# ENERGIS_Rack-PDU_1_0_0.net
KiCad netlist of a schematic drawn in EAGLE
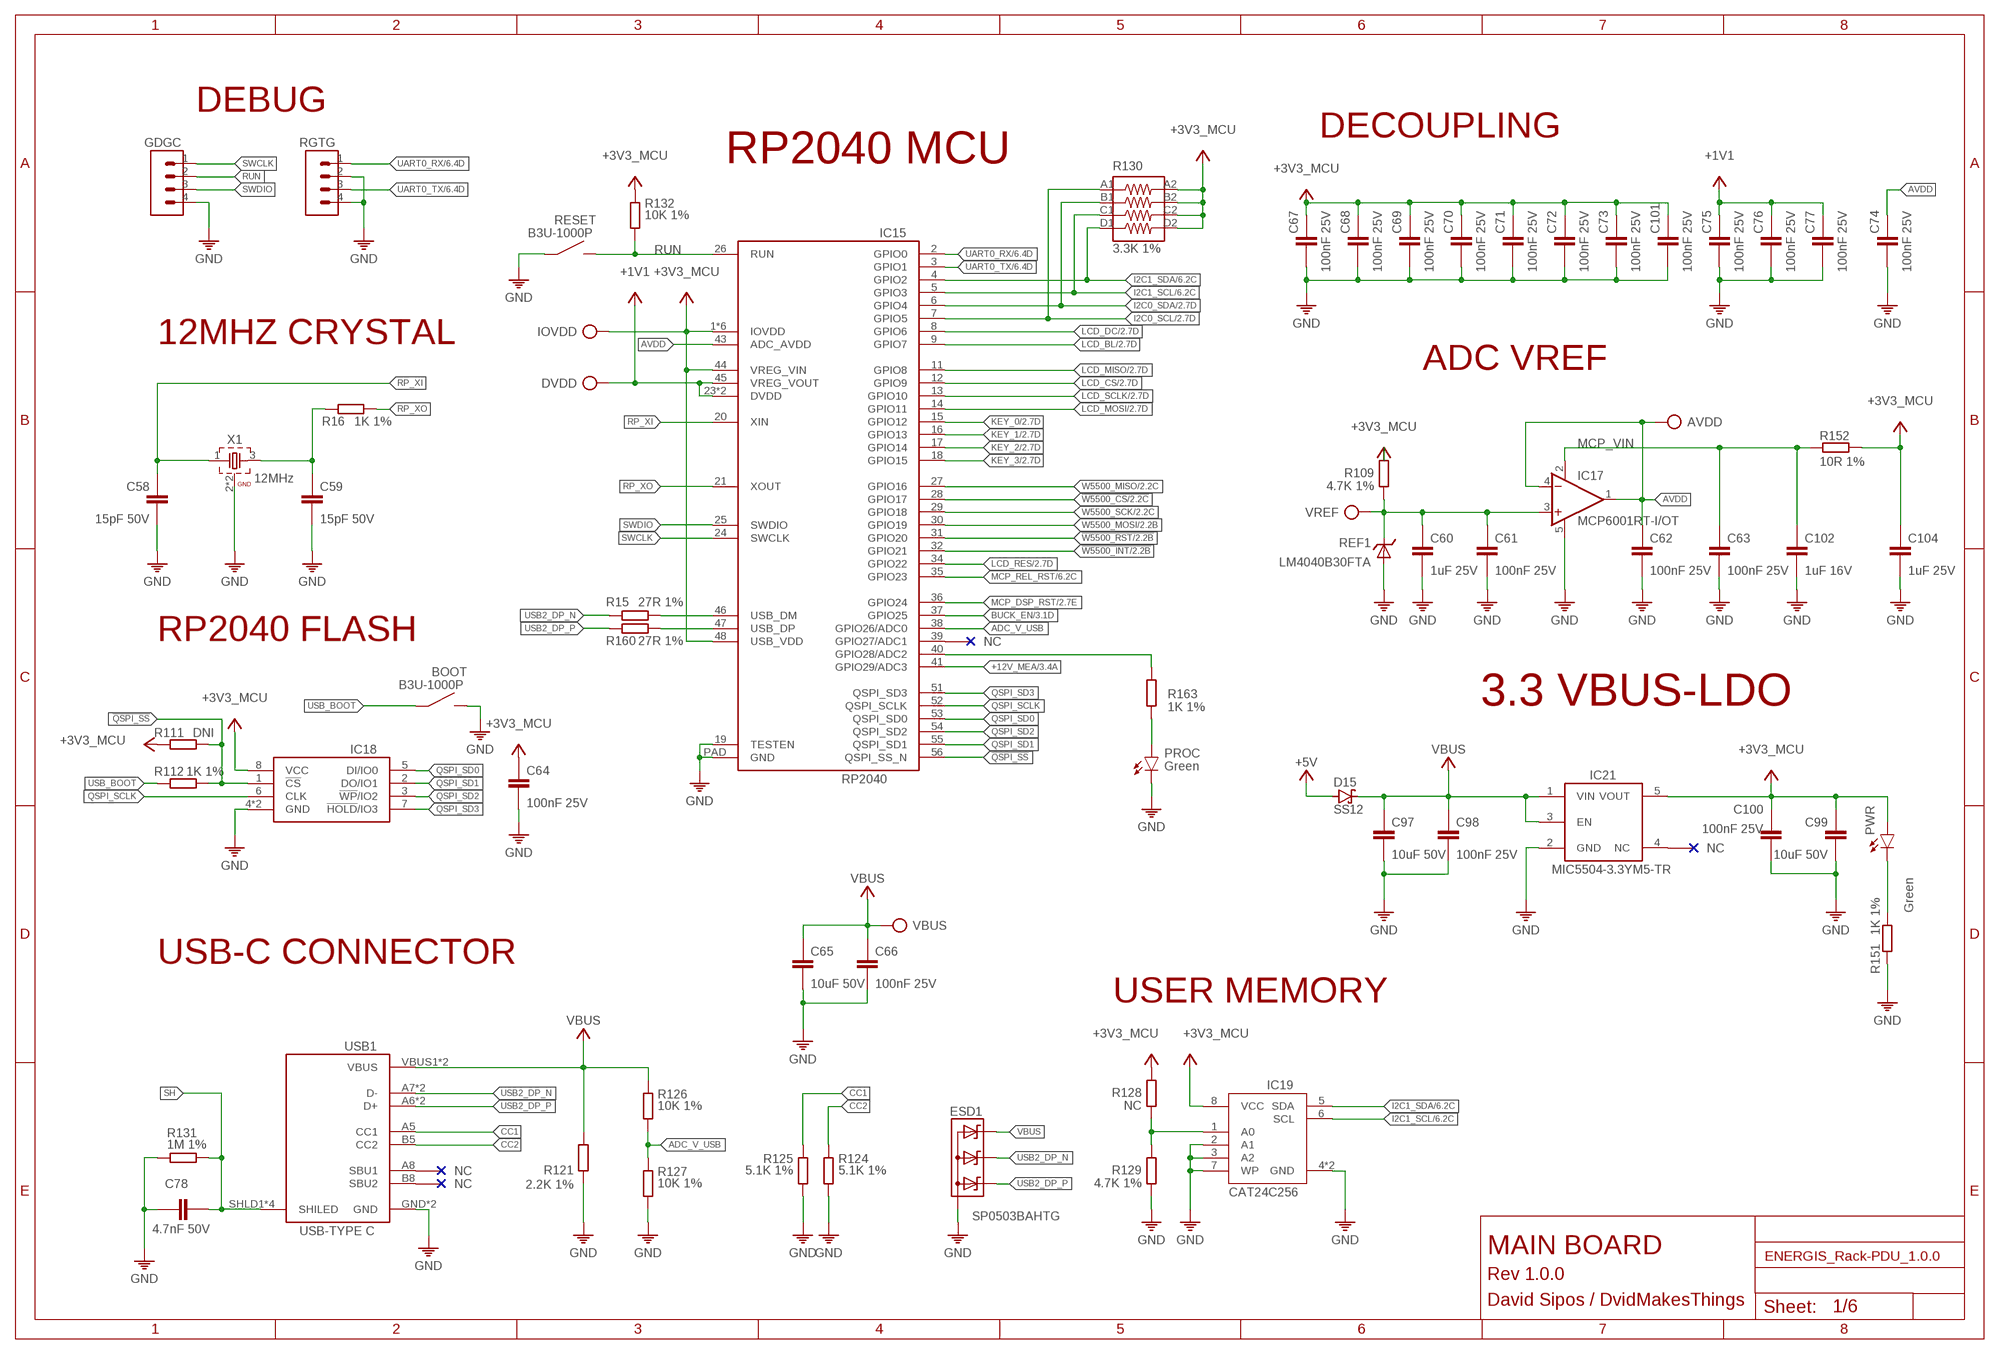
[diagram p0: schematic, sheet 1]
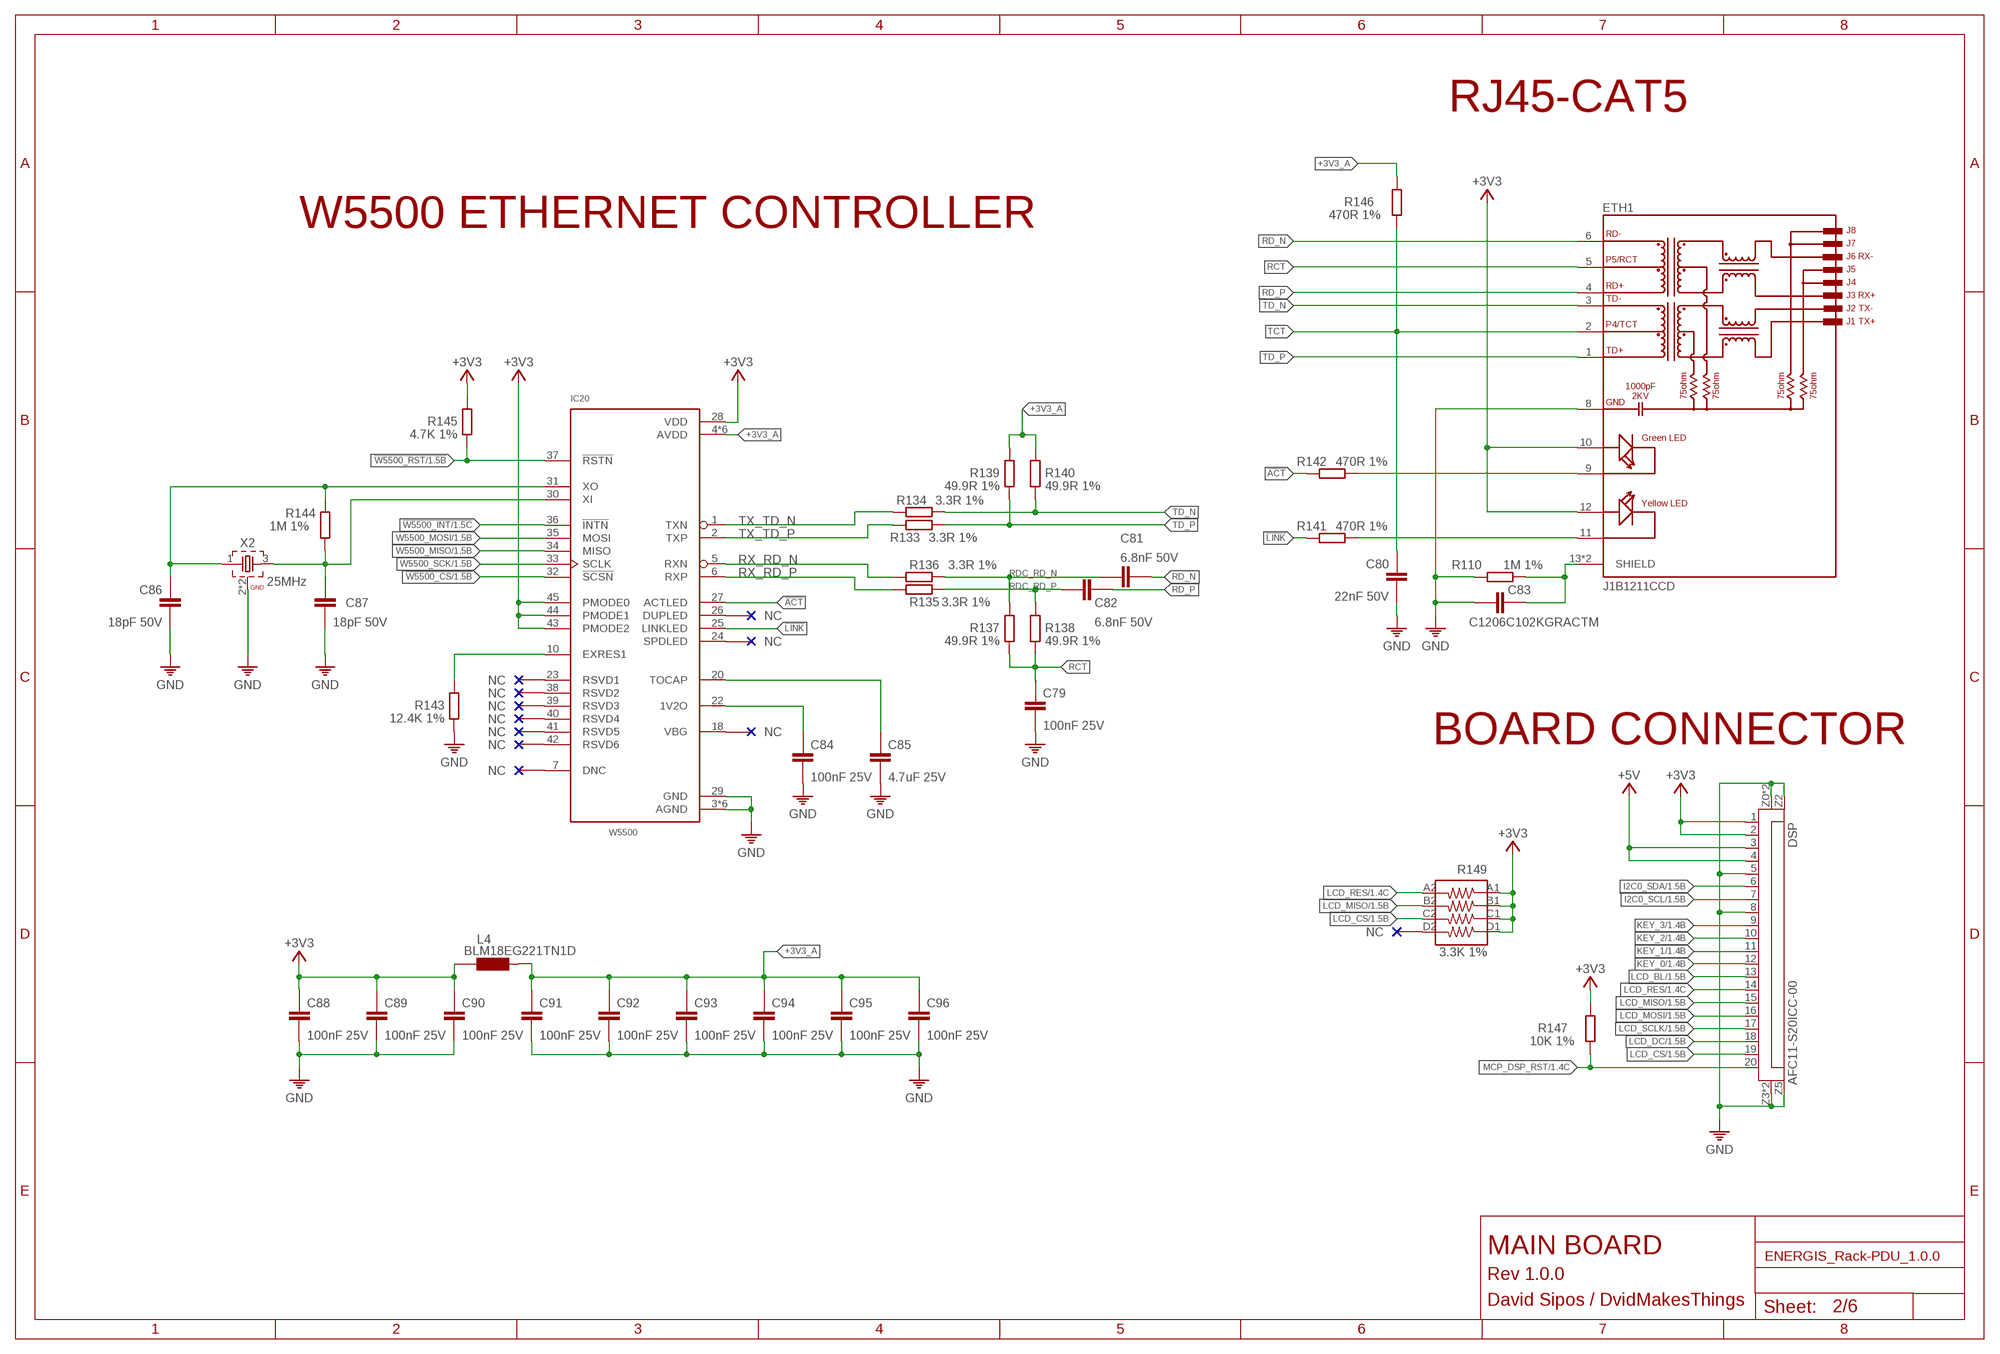
[diagram p1: schematic, sheet 2]
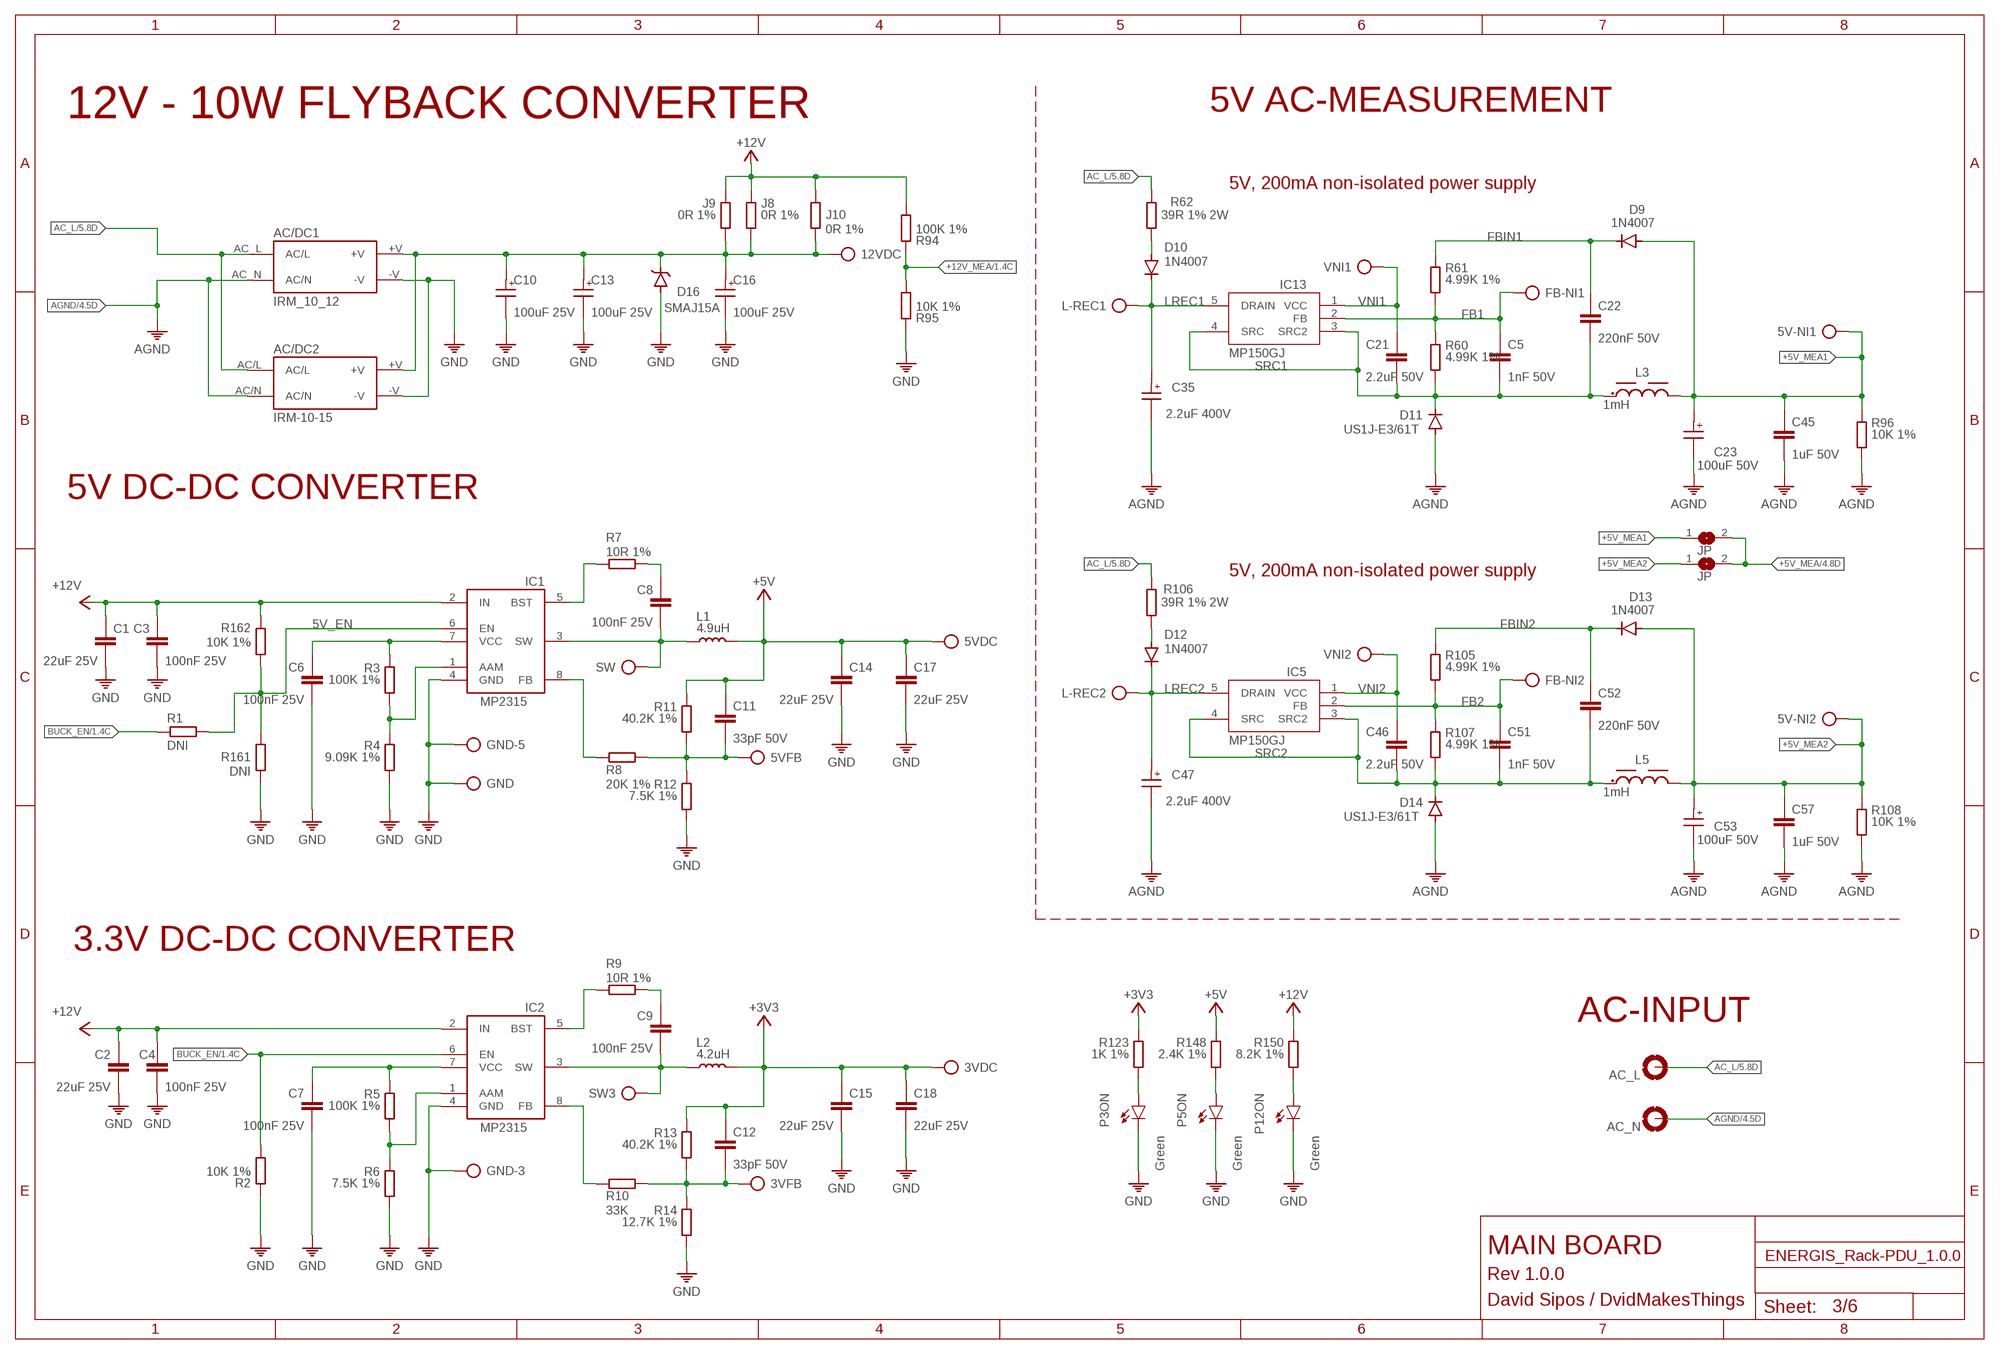
[diagram p2: schematic, sheet 3]
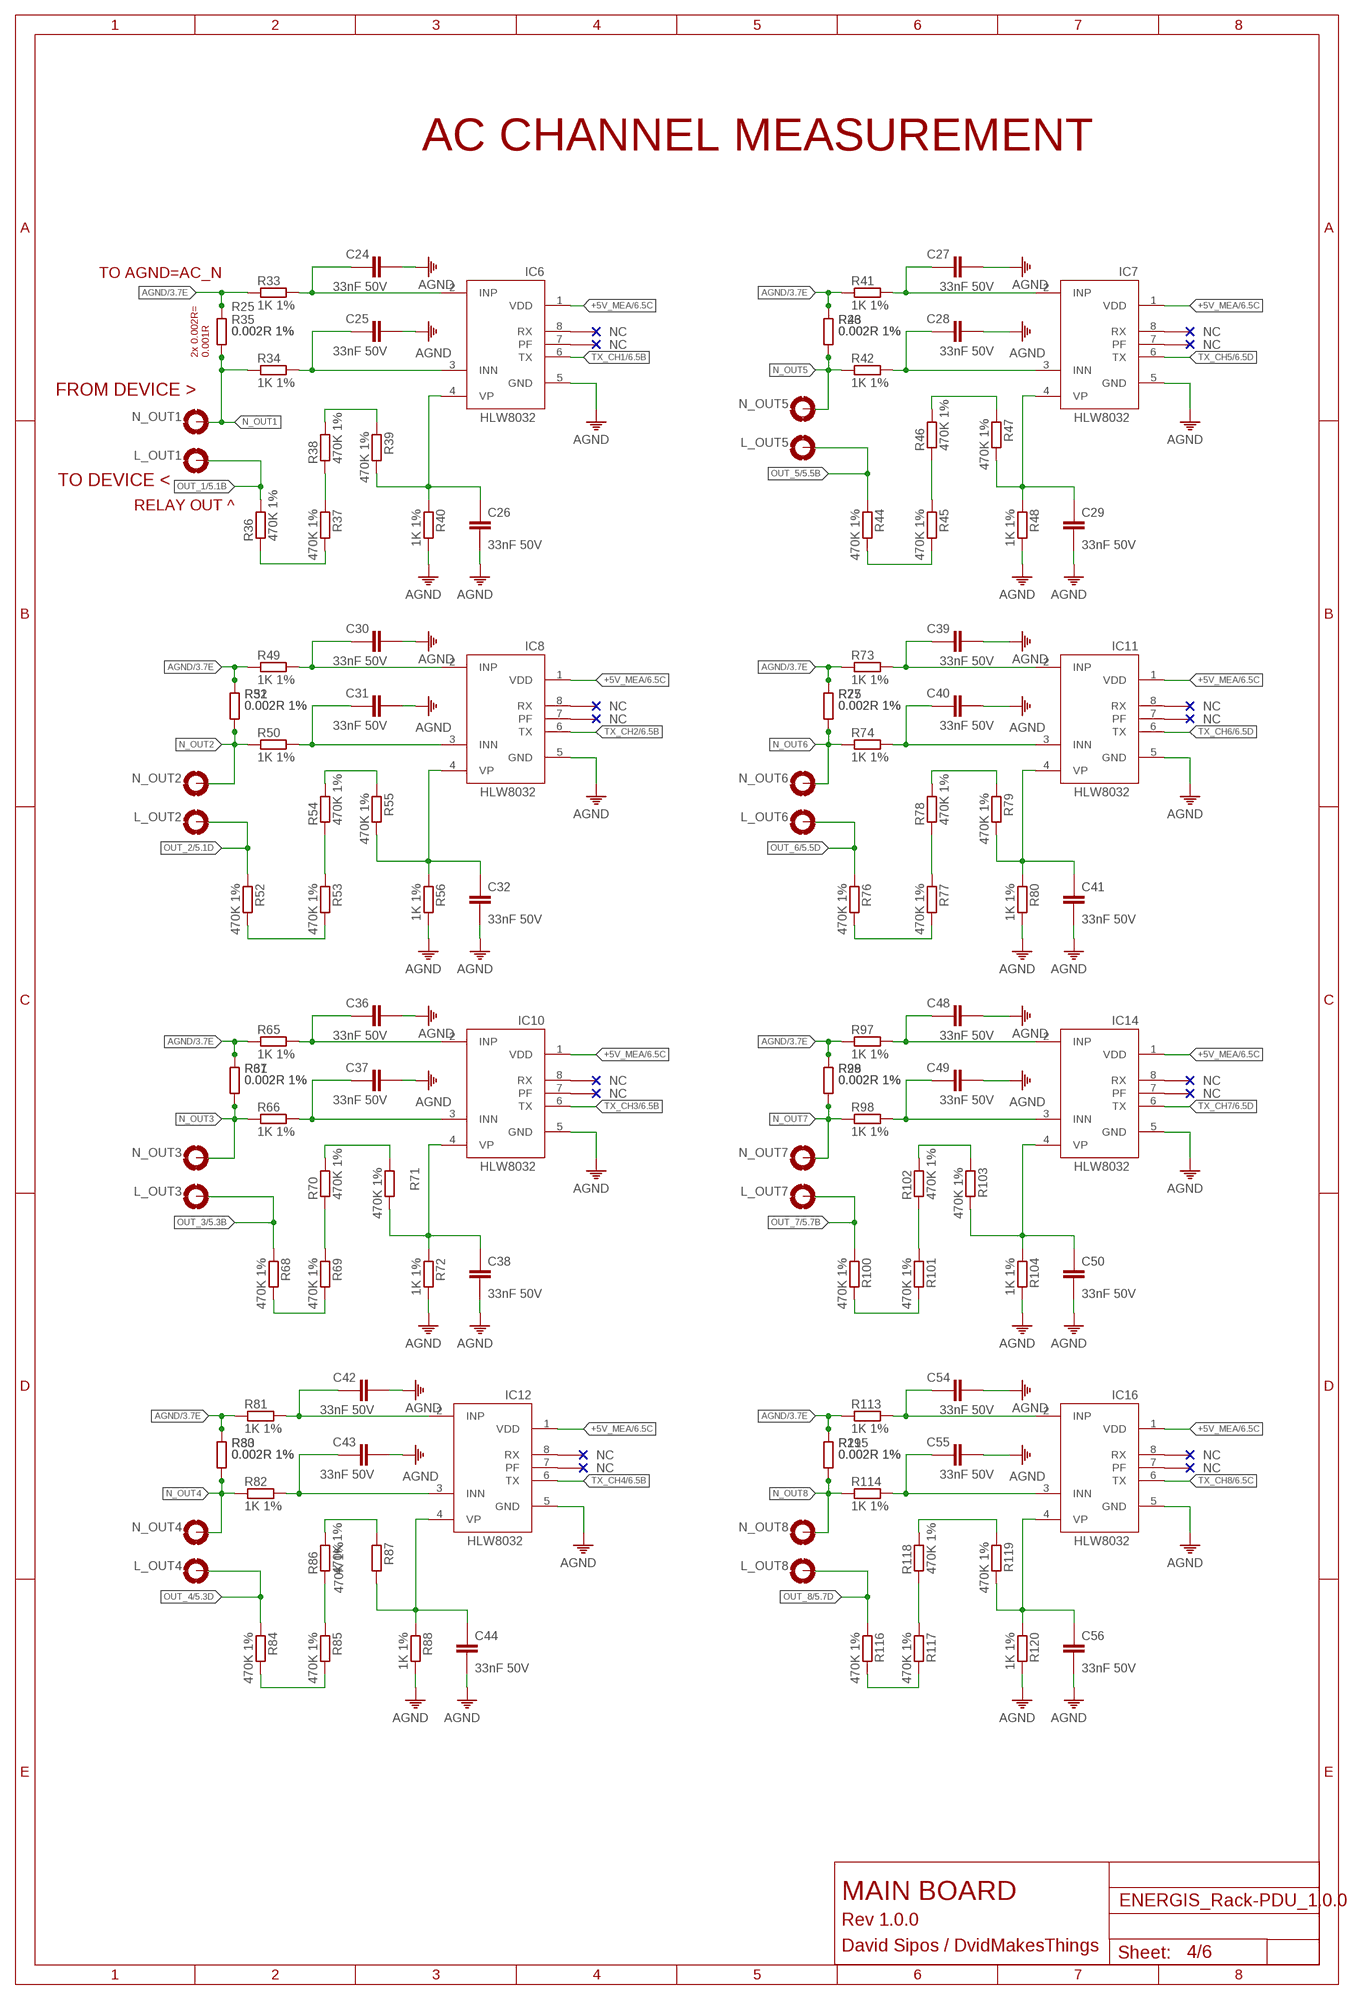
[diagram p3: schematic, sheet 4]
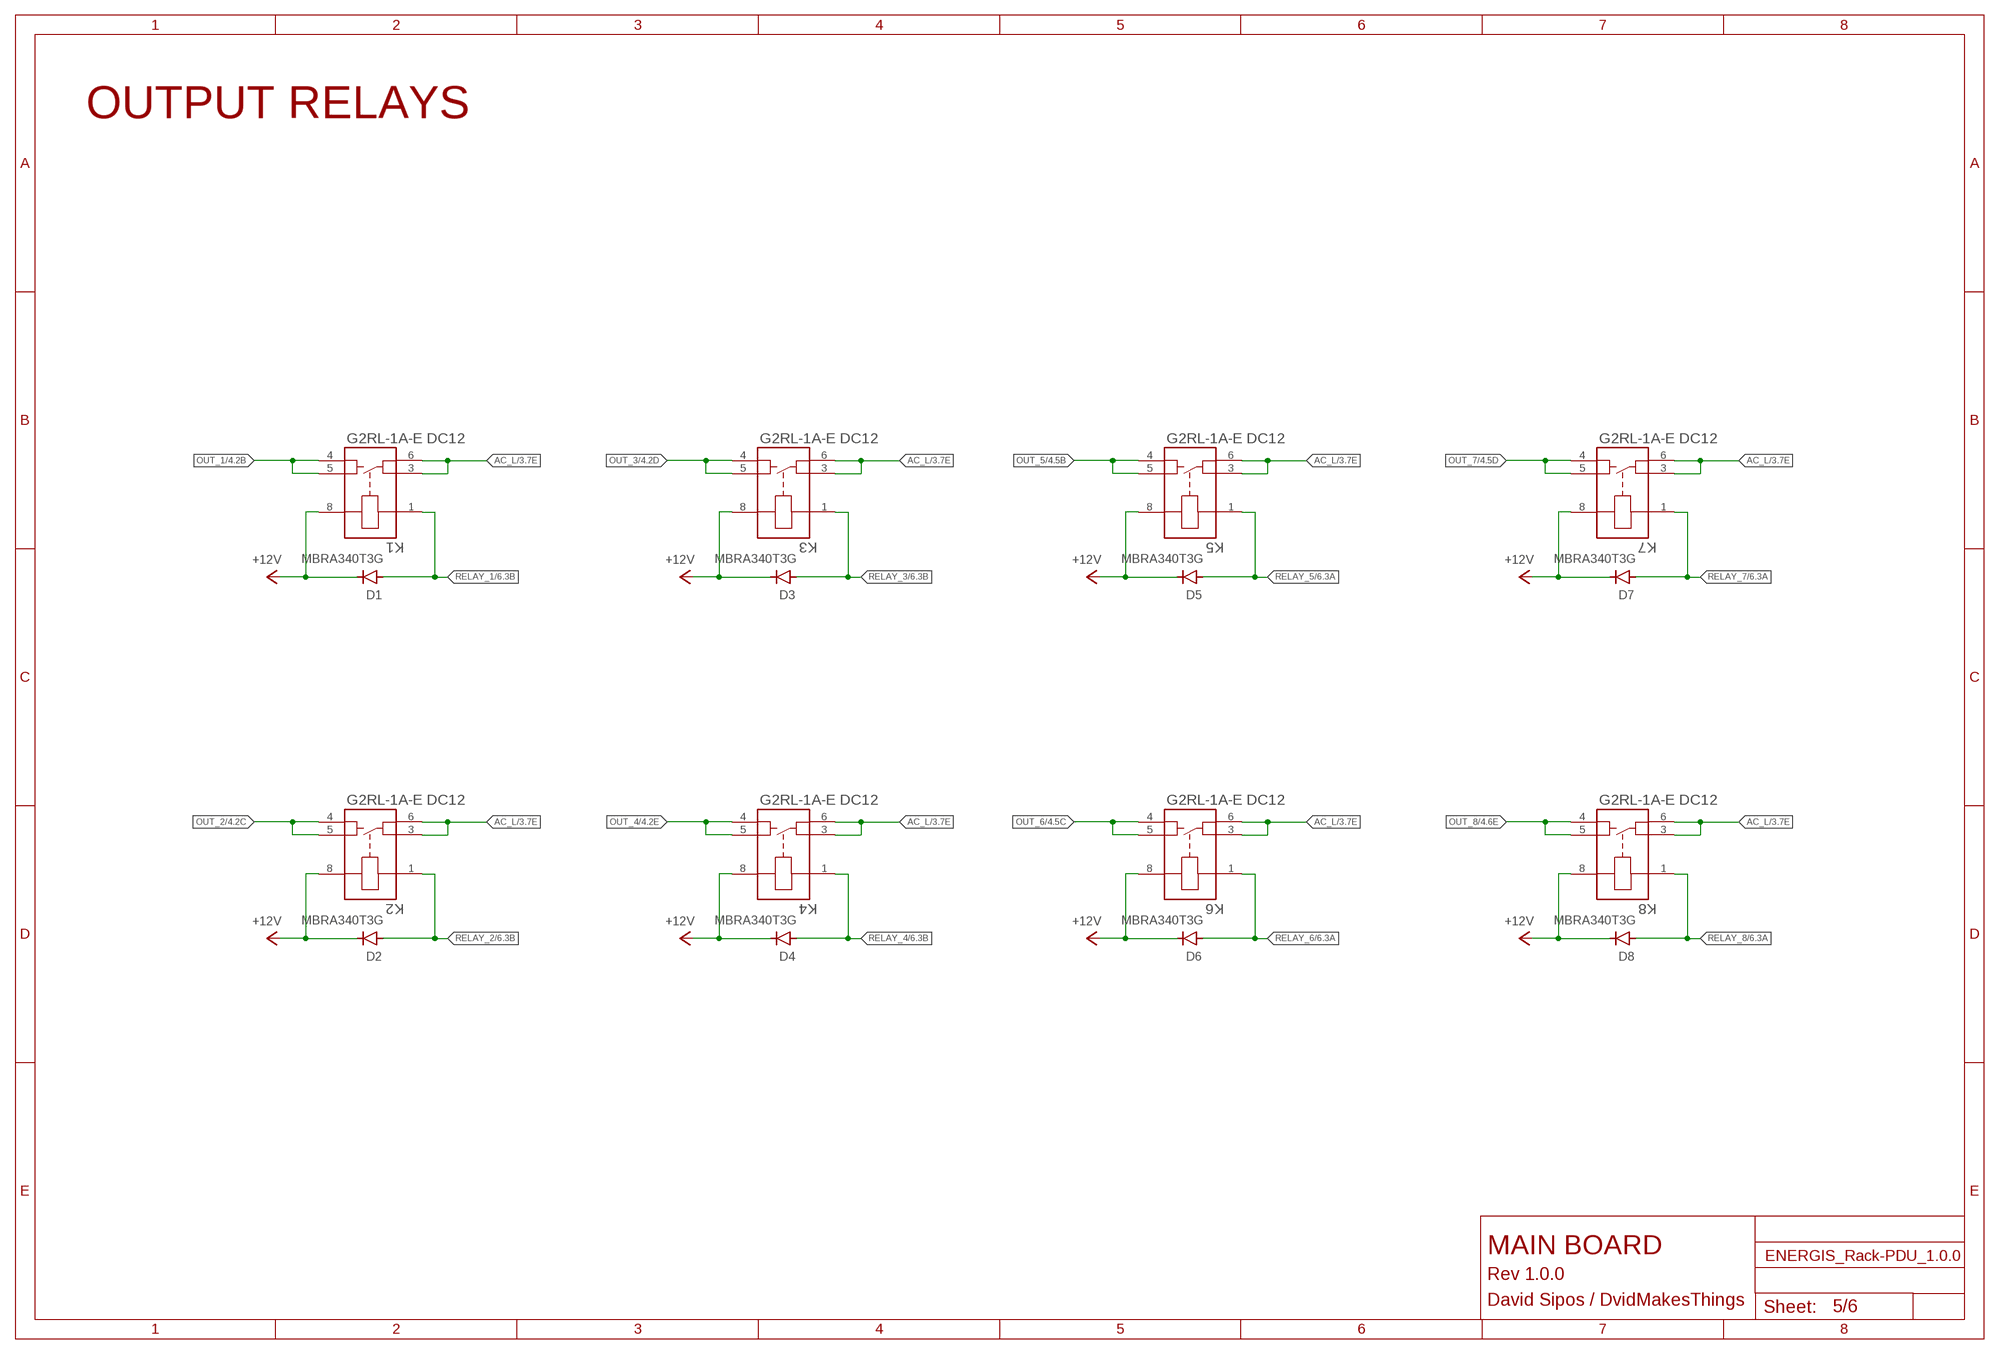
[diagram p4: schematic, sheet 5]
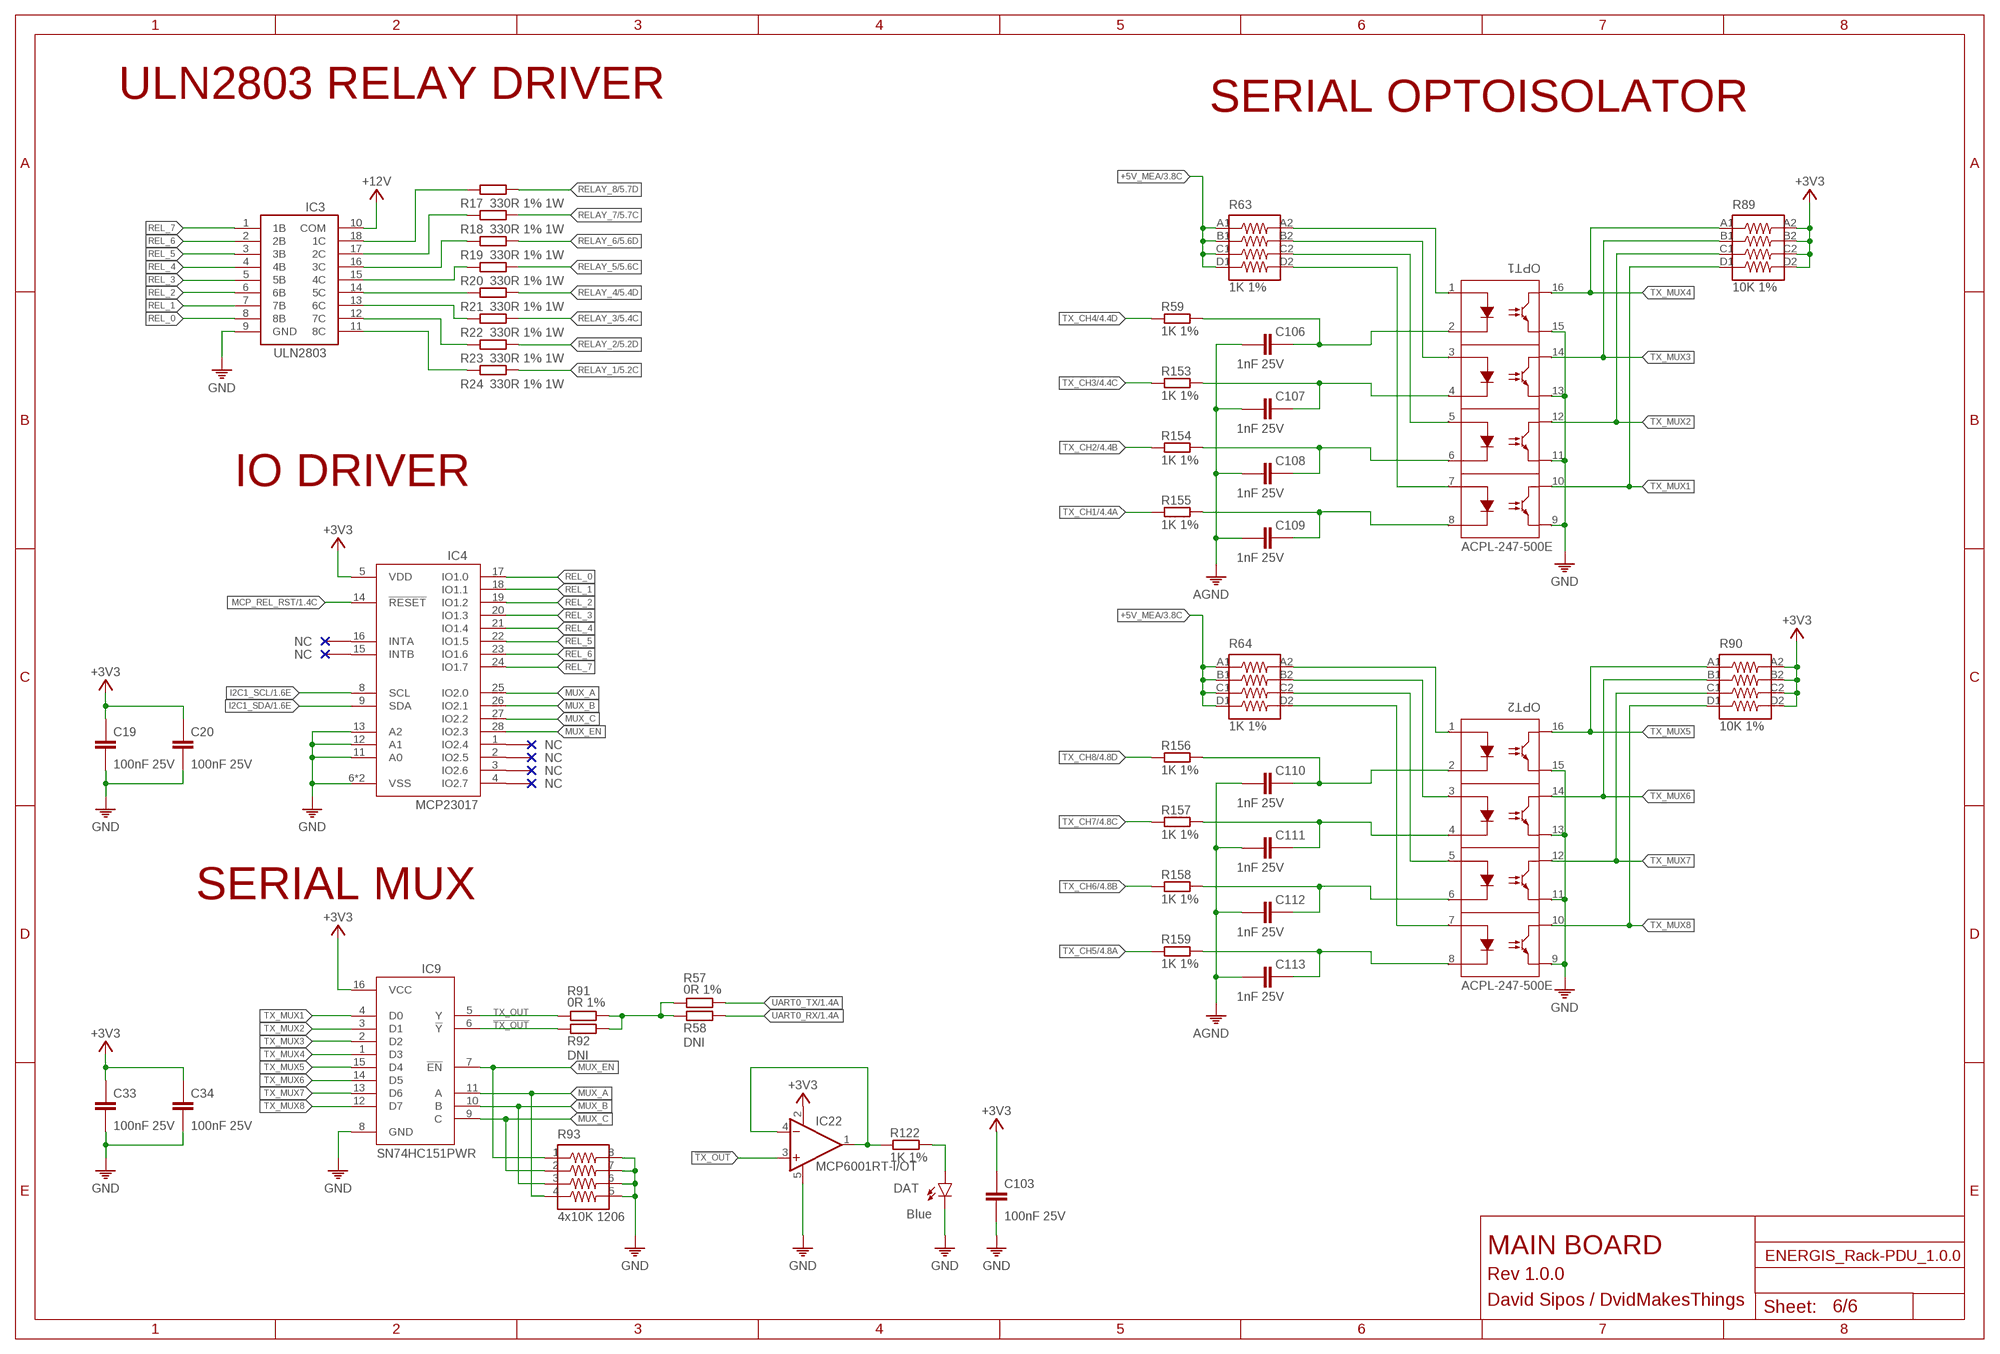
[diagram p5: schematic, sheet 6]

(export (version "E")
  (design (tool "Eeschema 10.0.6"))
  (components
    (comp (ref "D1")
      (value "MBRA340T3G")
      (footprint "eagle-import:SMA_DO-214AC")
      (fields (field (name "LCSC_PART") "C26178"))
      (libsource (lib "eagle-import") (part "MBRA340T3G"))
    )
    (comp (ref "D2")
      (value "MBRA340T3G")
      (footprint "eagle-import:SMA_DO-214AC")
      (fields (field (name "LCSC_PART") "C26178"))
      (libsource (lib "eagle-import") (part "MBRA340T3G"))
    )
    (comp (ref "D3")
      (value "MBRA340T3G")
      (footprint "eagle-import:SMA_DO-214AC")
      (fields (field (name "LCSC_PART") "C26178"))
      (libsource (lib "eagle-import") (part "MBRA340T3G"))
    )
    (comp (ref "D4")
      (value "MBRA340T3G")
      (footprint "eagle-import:SMA_DO-214AC")
      (fields (field (name "LCSC_PART") "C26178"))
      (libsource (lib "eagle-import") (part "MBRA340T3G"))
    )
    (comp (ref "D5")
      (value "MBRA340T3G")
      (footprint "eagle-import:SMA_DO-214AC")
      (fields (field (name "LCSC_PART") "C26178"))
      (libsource (lib "eagle-import") (part "MBRA340T3G"))
    )
    (comp (ref "D6")
      (value "MBRA340T3G")
      (footprint "eagle-import:SMA_DO-214AC")
      (fields (field (name "LCSC_PART") "C26178"))
      (libsource (lib "eagle-import") (part "MBRA340T3G"))
    )
    (comp (ref "D7")
      (value "MBRA340T3G")
      (footprint "eagle-import:SMA_DO-214AC")
      (fields (field (name "LCSC_PART") "C26178"))
      (libsource (lib "eagle-import") (part "MBRA340T3G"))
    )
    (comp (ref "D8")
      (value "MBRA340T3G")
      (footprint "eagle-import:SMA_DO-214AC")
      (fields (field (name "LCSC_PART") "C26178"))
      (libsource (lib "eagle-import") (part "MBRA340T3G"))
    )
    (comp (ref "K1")
      (value "G2RL-1A-E DC12")
      (footprint "eagle-import:RELAY_G2RL-1A-E_DC5_OMR")
      (fields (field (name "LCSC_PART") "C1564126"))
      (libsource (lib "eagle-import") (part "G2RL-1A-E_DC12"))
    )
    (comp (ref "K2")
      (value "G2RL-1A-E DC12")
      (footprint "eagle-import:RELAY_G2RL-1A-E_DC5_OMR")
      (fields (field (name "LCSC_PART") "C1564126"))
      (libsource (lib "eagle-import") (part "G2RL-1A-E_DC12"))
    )
    (comp (ref "K3")
      (value "G2RL-1A-E DC12")
      (footprint "eagle-import:RELAY_G2RL-1A-E_DC5_OMR")
      (fields (field (name "LCSC_PART") "C1564126"))
      (libsource (lib "eagle-import") (part "G2RL-1A-E_DC12"))
    )
    (comp (ref "K4")
      (value "G2RL-1A-E DC12")
      (footprint "eagle-import:RELAY_G2RL-1A-E_DC5_OMR")
      (fields (field (name "LCSC_PART") "C1564126"))
      (libsource (lib "eagle-import") (part "G2RL-1A-E_DC12"))
    )
    (comp (ref "K5")
      (value "G2RL-1A-E DC12")
      (footprint "eagle-import:RELAY_G2RL-1A-E_DC5_OMR")
      (fields (field (name "LCSC_PART") "C1564126"))
      (libsource (lib "eagle-import") (part "G2RL-1A-E_DC12"))
    )
    (comp (ref "K6")
      (value "G2RL-1A-E DC12")
      (footprint "eagle-import:RELAY_G2RL-1A-E_DC5_OMR")
      (fields (field (name "LCSC_PART") "C1564126"))
      (libsource (lib "eagle-import") (part "G2RL-1A-E_DC12"))
    )
    (comp (ref "K7")
      (value "G2RL-1A-E DC12")
      (footprint "eagle-import:RELAY_G2RL-1A-E_DC5_OMR")
      (fields (field (name "LCSC_PART") "C1564126"))
      (libsource (lib "eagle-import") (part "G2RL-1A-E_DC12"))
    )
    (comp (ref "K8")
      (value "G2RL-1A-E DC12")
      (footprint "eagle-import:RELAY_G2RL-1A-E_DC5_OMR")
      (fields (field (name "LCSC_PART") "C1564126"))
      (libsource (lib "eagle-import") (part "G2RL-1A-E_DC12"))
    )
    (comp (ref "AVDD")
      (value "TP")
      (footprint "eagle-import:TP")
      (libsource (lib "eagle-import") (part "TP"))
    )
    (comp (ref "BOOT")
      (value "B3U-1000P")
      (footprint "eagle-import:B3U-1000P")
      (fields (field (name "LCSC_PART") "C231329"))
      (libsource (lib "eagle-import") (part "B3U-1000P"))
    )
    (comp (ref "C58")
      (value "15pF 50V")
      (footprint "eagle-import:0201")
      (fields (field (name "LCSC_PART") "C22374851"))
      (libsource (lib "eagle-import") (part "15PF-50V0201"))
    )
    (comp (ref "C59")
      (value "15pF 50V")
      (footprint "eagle-import:0201")
      (fields (field (name "LCSC_PART") "C22374851"))
      (libsource (lib "eagle-import") (part "15PF-50V0201"))
    )
    (comp (ref "C60")
      (value "1uF 25V")
      (footprint "eagle-import:0402")
      (fields (field (name "LCSC_PART") "C52923"))
      (libsource (lib "eagle-import") (part "1UF-25V0402"))
    )
    (comp (ref "C61")
      (value "100nF 25V")
      (footprint "eagle-import:0201")
      (fields (field (name "LCSC_PART") "C76939"))
      (libsource (lib "eagle-import") (part "100NF-25V-0201"))
    )
    (comp (ref "C62")
      (value "100nF 25V")
      (footprint "eagle-import:0201")
      (fields (field (name "LCSC_PART") "C76939"))
      (libsource (lib "eagle-import") (part "100NF-25V-0201"))
    )
    (comp (ref "C63")
      (value "100nF 25V")
      (footprint "eagle-import:0201")
      (fields (field (name "LCSC_PART") "C76939"))
      (libsource (lib "eagle-import") (part "100NF-25V-0201"))
    )
    (comp (ref "C64")
      (value "100nF 25V")
      (footprint "eagle-import:0201")
      (fields (field (name "LCSC_PART") "C76939"))
      (libsource (lib "eagle-import") (part "100NF-25V-0201"))
    )
    (comp (ref "C65")
      (value "10uF 50V")
      (footprint "eagle-import:0805")
      (fields (field (name "LCSC_PART") "C440198"))
      (libsource (lib "eagle-import") (part "10UF-50V-0805"))
    )
    (comp (ref "C66")
      (value "100nF 25V")
      (footprint "eagle-import:0402")
      (fields (field (name "LCSC_PART") "C56392"))
      (libsource (lib "eagle-import") (part "100NF-25V-0402"))
    )
    (comp (ref "C67")
      (value "100nF 25V")
      (footprint "eagle-import:0201")
      (fields (field (name "LCSC_PART") "C76939"))
      (libsource (lib "eagle-import") (part "100NF-25V-0201"))
    )
    (comp (ref "C68")
      (value "100nF 25V")
      (footprint "eagle-import:0201")
      (fields (field (name "LCSC_PART") "C76939"))
      (libsource (lib "eagle-import") (part "100NF-25V-0201"))
    )
    (comp (ref "C69")
      (value "100nF 25V")
      (footprint "eagle-import:0201")
      (fields (field (name "LCSC_PART") "C76939"))
      (libsource (lib "eagle-import") (part "100NF-25V-0201"))
    )
    (comp (ref "C70")
      (value "100nF 25V")
      (footprint "eagle-import:0201")
      (fields (field (name "LCSC_PART") "C76939"))
      (libsource (lib "eagle-import") (part "100NF-25V-0201"))
    )
    (comp (ref "C71")
      (value "100nF 25V")
      (footprint "eagle-import:0201")
      (fields (field (name "LCSC_PART") "C76939"))
      (libsource (lib "eagle-import") (part "100NF-25V-0201"))
    )
    (comp (ref "C72")
      (value "100nF 25V")
      (footprint "eagle-import:0201")
      (fields (field (name "LCSC_PART") "C76939"))
      (libsource (lib "eagle-import") (part "100NF-25V-0201"))
    )
    (comp (ref "C73")
      (value "100nF 25V")
      (footprint "eagle-import:0201")
      (fields (field (name "LCSC_PART") "C76939"))
      (libsource (lib "eagle-import") (part "100NF-25V-0201"))
    )
    (comp (ref "C74")
      (value "100nF 25V")
      (footprint "eagle-import:0201")
      (fields (field (name "LCSC_PART") "C76939"))
      (libsource (lib "eagle-import") (part "100NF-25V-0201"))
    )
    (comp (ref "C75")
      (value "100nF 25V")
      (footprint "eagle-import:0201")
      (fields (field (name "LCSC_PART") "C76939"))
      (libsource (lib "eagle-import") (part "100NF-25V-0201"))
    )
    (comp (ref "C76")
      (value "100nF 25V")
      (footprint "eagle-import:0201")
      (fields (field (name "LCSC_PART") "C76939"))
      (libsource (lib "eagle-import") (part "100NF-25V-0201"))
    )
    (comp (ref "C77")
      (value "100nF 25V")
      (footprint "eagle-import:0201")
      (fields (field (name "LCSC_PART") "C76939"))
      (libsource (lib "eagle-import") (part "100NF-25V-0201"))
    )
    (comp (ref "C78")
      (value "4.7nF 50V")
      (footprint "eagle-import:0402")
      (fields (field (name "LCSC_PART") "C1538"))
      (libsource (lib "eagle-import") (part "4.7NF-50V0402"))
    )
    (comp (ref "C97")
      (value "10uF 50V")
      (footprint "eagle-import:0805")
      (fields (field (name "LCSC_PART") "C440198"))
      (libsource (lib "eagle-import") (part "10UF-50V-0805"))
    )
    (comp (ref "C98")
      (value "100nF 25V")
      (footprint "eagle-import:0201")
      (fields (field (name "LCSC_PART") "C76939"))
      (libsource (lib "eagle-import") (part "100NF-25V-0201"))
    )
    (comp (ref "C99")
      (value "10uF 50V")
      (footprint "eagle-import:0805")
      (fields (field (name "LCSC_PART") "C440198"))
      (libsource (lib "eagle-import") (part "10UF-50V-0805"))
    )
    (comp (ref "C100")
      (value "100nF 25V")
      (footprint "eagle-import:0201")
      (fields (field (name "LCSC_PART") "C76939"))
      (libsource (lib "eagle-import") (part "100NF-25V-0201"))
    )
    (comp (ref "C101")
      (value "100nF 25V")
      (footprint "eagle-import:0201")
      (fields (field (name "LCSC_PART") "C76939"))
      (libsource (lib "eagle-import") (part "100NF-25V-0201"))
    )
    (comp (ref "C102")
      (value "1uF 16V")
      (footprint "eagle-import:0201")
      (fields (field (name "LCSC_PART") "C307385"))
      (libsource (lib "eagle-import") (part "1UF-16V0201"))
    )
    (comp (ref "C104")
      (value "1uF 25V")
      (footprint "eagle-import:0402")
      (fields (field (name "LCSC_PART") "C52923"))
      (libsource (lib "eagle-import") (part "1UF-25V0402"))
    )
    (comp (ref "D15")
      (value "SS12")
      (footprint "eagle-import:SMA_DO-214AC")
      (fields (field (name "LCSC_PART") "C727049"))
      (libsource (lib "eagle-import") (part "SS12"))
    )
    (comp (ref "DVDD")
      (value "TP")
      (footprint "eagle-import:TP")
      (libsource (lib "eagle-import") (part "TP"))
    )
    (comp (ref "ESD1")
      (value "SP0503BAHTG")
      (footprint "eagle-import:SOT143")
      (fields (field (name "LCSC_PART") "C3040626"))
      (libsource (lib "eagle-import") (part "SP0503BAHT"))
    )
    (comp (ref "GDGC")
      (value "CON-1X4")
      (footprint "eagle-import:1X4")
      (libsource (lib "eagle-import") (part "CON-1X4"))
    )
    (comp (ref "IC15")
      (value "RP2040")
      (footprint "eagle-import:QFN56")
      (fields (field (name "LCSC_PART") "C2040"))
      (libsource (lib "eagle-import") (part "RP2040"))
    )
    (comp (ref "IC17")
      (value "MCP6001RT-I/OT")
      (footprint "eagle-import:SOT23-5")
      (fields (field (name "LCSC_PART") "C154973"))
      (libsource (lib "eagle-import") (part "MCP6001RT"))
    )
    (comp (ref "IC18")
      (value "W25Q128JVPIQ")
      (footprint "eagle-import:SON127P600X500X75-8N")
      (fields (field (name "LCSC_PART") "C190862"))
      (libsource (lib "eagle-import") (part "W25Q128JVP"))
    )
    (comp (ref "IC19")
      (value "CAT24C256HU4IGT3")
      (footprint "eagle-import:SON50P300X200X50-9T130X140N")
      (fields (field (name "LCSC_PART") "C233771"))
      (libsource (lib "eagle-import") (part "CAT24C256-HU4"))
    )
    (comp (ref "IC21")
      (value "MIC5504-3.3YM5")
      (footprint "eagle-import:SOT23-5")
      (fields (field (name "LCSC_PART") "C41348078"))
      (libsource (lib "eagle-import") (part "MIC5504-3.3YM5-TR"))
    )
    (comp (ref "IOVDD")
      (value "TP")
      (footprint "eagle-import:TP")
      (libsource (lib "eagle-import") (part "TP"))
    )
    (comp (ref "PROC")
      (value "Green")
      (footprint "eagle-import:LED-0603")
      (fields (field (name "LCSC_PART") "C965804"))
      (libsource (lib "eagle-import") (part "LED-GREENLED-0603"))
    )
    (comp (ref "PWR")
      (value "Green")
      (footprint "eagle-import:LED-0603")
      (fields (field (name "LCSC_PART") "C965804"))
      (libsource (lib "eagle-import") (part "LED-GREENLED-0603"))
    )
    (comp (ref "R15")
      (value "27R 1%")
      (footprint "eagle-import:0201")
      (fields (field (name "LCSC_PART") "C473051"))
      (libsource (lib "eagle-import") (part "27R-1%0201"))
    )
    (comp (ref "R16")
      (value "1K 1%")
      (footprint "eagle-import:0201")
      (fields (field (name "LCSC_PART") "C270365"))
      (libsource (lib "eagle-import") (part "1K-1%0201"))
    )
    (comp (ref "R109")
      (value "4.7K 1%")
      (footprint "eagle-import:0201")
      (fields (field (name "LCSC_PART") "C270346"))
      (libsource (lib "eagle-import") (part "4.7K-1%0201"))
    )
    (comp (ref "R111")
      (value "DNI")
      (footprint "eagle-import:R0201")
      (libsource (lib "eagle-import") (part "R0201"))
    )
    (comp (ref "R112")
      (value "1K 1%")
      (footprint "eagle-import:0402")
      (fields (field (name "LCSC_PART") "C11702"))
      (libsource (lib "eagle-import") (part "1K-1%0402"))
    )
    (comp (ref "R121")
      (value "2.2K 1%")
      (footprint "eagle-import:0201")
      (fields (field (name "LCSC_PART") "C473508"))
      (libsource (lib "eagle-import") (part "2.2K-1%0201"))
    )
    (comp (ref "R124")
      (value "5.1K 1%")
      (footprint "eagle-import:0201")
      (fields (field (name "LCSC_PART") "C274341"))
      (libsource (lib "eagle-import") (part "5.1K-1%0201"))
    )
    (comp (ref "R125")
      (value "5.1K 1%")
      (footprint "eagle-import:0201")
      (fields (field (name "LCSC_PART") "C274341"))
      (libsource (lib "eagle-import") (part "5.1K-1%0201"))
    )
    (comp (ref "R126")
      (value "10K 1%")
      (footprint "eagle-import:0201")
      (fields (field (name "LCSC_PART") "C473048"))
      (libsource (lib "eagle-import") (part "10K-1%0201"))
    )
    (comp (ref "R127")
      (value "10K 1%")
      (footprint "eagle-import:0201")
      (fields (field (name "LCSC_PART") "C473048"))
      (libsource (lib "eagle-import") (part "10K-1%0201"))
    )
    (comp (ref "R128")
      (value "NC")
      (footprint "eagle-import:R0201")
      (libsource (lib "eagle-import") (part "R0201"))
    )
    (comp (ref "R129")
      (value "4.7K 1%")
      (footprint "eagle-import:0201")
      (fields (field (name "LCSC_PART") "C270346"))
      (libsource (lib "eagle-import") (part "4.7K-1%0201"))
    )
    (comp (ref "R130")
      (value "3.3K 1%")
      (footprint "eagle-import:_0603X4-1206")
      (fields (field (name "LCSC_PART") "C1734380"))
      (libsource (lib "eagle-import") (part "3.3K-1%_ARRAY0603X4-1206"))
    )
    (comp (ref "R131")
      (value "1M 1%")
      (footprint "eagle-import:0402")
      (fields (field (name "LCSC_PART") "C26083"))
      (libsource (lib "eagle-import") (part "1M-1%0402"))
    )
    (comp (ref "R132")
      (value "10K 1%")
      (footprint "eagle-import:0402")
      (fields (field (name "LCSC_PART") "C25744"))
      (libsource (lib "eagle-import") (part "10K-1%0402"))
    )
    (comp (ref "R151")
      (value "1K 1%")
      (footprint "eagle-import:0402")
      (fields (field (name "LCSC_PART") "C11702"))
      (libsource (lib "eagle-import") (part "1K-1%0402"))
    )
    (comp (ref "R152")
      (value "10R 1%")
      (footprint "eagle-import:0201")
      (fields (field (name "LCSC_PART") "C270817"))
      (libsource (lib "eagle-import") (part "10R-1%0201"))
    )
    (comp (ref "R160")
      (value "27R 1%")
      (footprint "eagle-import:0201")
      (fields (field (name "LCSC_PART") "C473051"))
      (libsource (lib "eagle-import") (part "27R-1%0201"))
    )
    (comp (ref "R163")
      (value "1K 1%")
      (footprint "eagle-import:0402")
      (fields (field (name "LCSC_PART") "C11702"))
      (libsource (lib "eagle-import") (part "1K-1%0402"))
    )
    (comp (ref "REF1")
      (value "LM4040B30FTA")
      (footprint "eagle-import:SOT23")
      (fields (field (name "LCSC_PART") "C460604"))
      (libsource (lib "eagle-import") (part "LM4040BXX"))
    )
    (comp (ref "RESET")
      (value "B3U-1000P")
      (footprint "eagle-import:B3U-1000P")
      (fields (field (name "LCSC_PART") "C231329"))
      (libsource (lib "eagle-import") (part "B3U-1000P"))
    )
    (comp (ref "RGTG")
      (value "CON-1X4")
      (footprint "eagle-import:1X4")
      (libsource (lib "eagle-import") (part "CON-1X4"))
    )
    (comp (ref "USB1")
      (value "USB-TYPE-C-018")
      (footprint "eagle-import:USB-C")
      (fields (field (name "LCSC_PART") "C2927038"))
      (libsource (lib "eagle-import") (part "USB_C-THT"))
    )
    (comp (ref "VBUS")
      (value "TP")
      (footprint "eagle-import:TP")
      (libsource (lib "eagle-import") (part "TP"))
    )
    (comp (ref "VREF")
      (value "TP")
      (footprint "eagle-import:TP")
      (libsource (lib "eagle-import") (part "TP"))
    )
    (comp (ref "X1")
      (value "12MHz")
      (footprint "eagle-import:WE-XTAL_CFPX-180")
      (fields (field (name "LCSC_PART") "C9002"))
      (libsource (lib "eagle-import") (part "CRYSTAL-3225X322512MSB4SI"))
    )
    (comp (ref "C79")
      (value "100nF 25V")
      (footprint "eagle-import:0402")
      (fields (field (name "LCSC_PART") "C56392"))
      (libsource (lib "eagle-import") (part "100NF-25V-0402"))
    )
    (comp (ref "C80")
      (value "22nF 50V")
      (footprint "eagle-import:0402")
      (fields (field (name "LCSC_PART") "C1532"))
      (libsource (lib "eagle-import") (part "22NF-50V0402"))
    )
    (comp (ref "C81")
      (value "6.8nF 50V")
      (footprint "eagle-import:0201")
      (fields (field (name "LCSC_PART") "C285015"))
      (libsource (lib "eagle-import") (part "6.8NF-50V0201"))
    )
    (comp (ref "C82")
      (value "6.8nF 50V")
      (footprint "eagle-import:0201")
      (fields (field (name "LCSC_PART") "C285015"))
      (libsource (lib "eagle-import") (part "6.8NF-50V0201"))
    )
    (comp (ref "C83")
      (value "C1206C102KGRACTM")
      (footprint "eagle-import:C1206")
      (libsource (lib "eagle-import") (part "C-1206"))
    )
    (comp (ref "C84")
      (value "100nF 25V")
      (footprint "eagle-import:0201")
      (fields (field (name "LCSC_PART") "C76939"))
      (libsource (lib "eagle-import") (part "100NF-25V-0201"))
    )
    (comp (ref "C85")
      (value "4.7uF 25V")
      (footprint "eagle-import:0402")
      (fields (field (name "LCSC_PART") "C22367824"))
      (libsource (lib "eagle-import") (part "4.7UF-25V0402"))
    )
    (comp (ref "C86")
      (value "18pF 50V")
      (footprint "eagle-import:0201")
      (fields (field (name "LCSC_PART") "C62164"))
      (libsource (lib "eagle-import") (part "18PF-50V-0201"))
    )
    (comp (ref "C87")
      (value "18pF 50V")
      (footprint "eagle-import:0201")
      (fields (field (name "LCSC_PART") "C62164"))
      (libsource (lib "eagle-import") (part "18PF-50V-0201"))
    )
    (comp (ref "C88")
      (value "100nF 25V")
      (footprint "eagle-import:0201")
      (fields (field (name "LCSC_PART") "C76939"))
      (libsource (lib "eagle-import") (part "100NF-25V-0201"))
    )
    (comp (ref "C89")
      (value "100nF 25V")
      (footprint "eagle-import:0201")
      (fields (field (name "LCSC_PART") "C76939"))
      (libsource (lib "eagle-import") (part "100NF-25V-0201"))
    )
    (comp (ref "C90")
      (value "100nF 25V")
      (footprint "eagle-import:0201")
      (fields (field (name "LCSC_PART") "C76939"))
      (libsource (lib "eagle-import") (part "100NF-25V-0201"))
    )
    (comp (ref "C91")
      (value "100nF 25V")
      (footprint "eagle-import:0201")
      (fields (field (name "LCSC_PART") "C76939"))
      (libsource (lib "eagle-import") (part "100NF-25V-0201"))
    )
    (comp (ref "C92")
      (value "100nF 25V")
      (footprint "eagle-import:0201")
      (fields (field (name "LCSC_PART") "C76939"))
      (libsource (lib "eagle-import") (part "100NF-25V-0201"))
    )
    (comp (ref "C93")
      (value "100nF 25V")
      (footprint "eagle-import:0201")
      (fields (field (name "LCSC_PART") "C76939"))
      (libsource (lib "eagle-import") (part "100NF-25V-0201"))
    )
    (comp (ref "C94")
      (value "100nF 25V")
      (footprint "eagle-import:0201")
      (fields (field (name "LCSC_PART") "C76939"))
      (libsource (lib "eagle-import") (part "100NF-25V-0201"))
    )
    (comp (ref "C95")
      (value "100nF 25V")
      (footprint "eagle-import:0201")
      (fields (field (name "LCSC_PART") "C76939"))
      (libsource (lib "eagle-import") (part "100NF-25V-0201"))
    )
    (comp (ref "C96")
      (value "100nF 25V")
      (footprint "eagle-import:0201")
      (fields (field (name "LCSC_PART") "C76939"))
      (libsource (lib "eagle-import") (part "100NF-25V-0201"))
    )
    (comp (ref "DSP")
      (value "AFC11-S20ICC-00")
      (footprint "eagle-import:FPC20")
      (fields (field (name "LCSC_PART") "C11073"))
      (libsource (lib "eagle-import") (part "AFC11-S20ICC-00"))
    )
    (comp (ref "ETH1")
      (value "J1B1211CCD")
      (footprint "eagle-import:J1B1211CCD")
      (fields (field (name "LCSC_PART") "C910371"))
      (libsource (lib "eagle-import") (part "J1B1211CCD"))
    )
    (comp (ref "IC20")
      (value "W5500")
      (footprint "eagle-import:LQFP48")
      (fields (field (name "LCSC_PART") "C32843"))
      (libsource (lib "eagle-import") (part "W5500"))
    )
    (comp (ref "L4")
      (value "BLM18EG221TN1D")
      (footprint "eagle-import:0603")
      (fields (field (name "LCSC_PART") "C113025"))
      (libsource (lib "eagle-import") (part "BLM18EG221TN1D"))
    )
    (comp (ref "R110")
      (value "1M 1%")
      (footprint "eagle-import:1206")
      (fields (field (name "LCSC_PART") "C17927"))
      (libsource (lib "eagle-import") (part "1M-1%1206"))
    )
    (comp (ref "R133")
      (value "3.3R 1%")
      (footprint "eagle-import:0201")
      (fields (field (name "LCSC_PART") "C158547"))
      (libsource (lib "eagle-import") (part "3.3R-1%0201"))
    )
    (comp (ref "R134")
      (value "3.3R 1%")
      (footprint "eagle-import:0201")
      (fields (field (name "LCSC_PART") "C158547"))
      (libsource (lib "eagle-import") (part "3.3R-1%0201"))
    )
    (comp (ref "R135")
      (value "3.3R 1%")
      (footprint "eagle-import:0201")
      (fields (field (name "LCSC_PART") "C158547"))
      (libsource (lib "eagle-import") (part "3.3R-1%0201"))
    )
    (comp (ref "R136")
      (value "3.3R 1%")
      (footprint "eagle-import:0201")
      (fields (field (name "LCSC_PART") "C158547"))
      (libsource (lib "eagle-import") (part "3.3R-1%0201"))
    )
    (comp (ref "R137")
      (value "49.9R 1%")
      (footprint "eagle-import:0201")
      (fields (field (name "LCSC_PART") "C155744"))
      (libsource (lib "eagle-import") (part "49.9R-1%0201"))
    )
    (comp (ref "R138")
      (value "49.9R 1%")
      (footprint "eagle-import:0201")
      (fields (field (name "LCSC_PART") "C155744"))
      (libsource (lib "eagle-import") (part "49.9R-1%0201"))
    )
    (comp (ref "R139")
      (value "49.9R 1%")
      (footprint "eagle-import:0201")
      (fields (field (name "LCSC_PART") "C155744"))
      (libsource (lib "eagle-import") (part "49.9R-1%0201"))
    )
    (comp (ref "R140")
      (value "49.9R 1%")
      (footprint "eagle-import:0201")
      (fields (field (name "LCSC_PART") "C155744"))
      (libsource (lib "eagle-import") (part "49.9R-1%0201"))
    )
    (comp (ref "R141")
      (value "470R 1%")
      (footprint "eagle-import:0402")
      (fields (field (name "LCSC_PART") "C25117"))
      (libsource (lib "eagle-import") (part "470R-1%0402"))
    )
    (comp (ref "R142")
      (value "470R 1%")
      (footprint "eagle-import:0402")
      (fields (field (name "LCSC_PART") "C25117"))
      (libsource (lib "eagle-import") (part "470R-1%0402"))
    )
    (comp (ref "R143")
      (value "12.4K 1%")
      (footprint "eagle-import:R0201")
      (libsource (lib "eagle-import") (part "R0201"))
    )
    (comp (ref "R144")
      (value "1M 1%")
      (footprint "eagle-import:0201")
      (fields (field (name "LCSC_PART") "C295786"))
      (libsource (lib "eagle-import") (part "1M-1%0201"))
    )
    (comp (ref "R145")
      (value "4.7K 1%")
      (footprint "eagle-import:0201")
      (fields (field (name "LCSC_PART") "C270346"))
      (libsource (lib "eagle-import") (part "4.7K-1%0201"))
    )
    (comp (ref "R146")
      (value "470R 1%")
      (footprint "eagle-import:0402")
      (fields (field (name "LCSC_PART") "C25117"))
      (libsource (lib "eagle-import") (part "470R-1%0402"))
    )
    (comp (ref "R147")
      (value "10K 1%")
      (footprint "eagle-import:0402")
      (fields (field (name "LCSC_PART") "C25744"))
      (libsource (lib "eagle-import") (part "10K-1%0402"))
    )
    (comp (ref "R149")
      (value "3.3K 1%")
      (footprint "eagle-import:_0603X4-1206")
      (fields (field (name "LCSC_PART") "C1734380"))
      (libsource (lib "eagle-import") (part "3.3K-1%_ARRAY0603X4-1206"))
    )
    (comp (ref "X2")
      (value "25MHz")
      (footprint "eagle-import:WE-XTAL_CFPX-180")
      (fields (field (name "LCSC_PART") "C9006"))
      (libsource (lib "eagle-import") (part "CRYSTAL-3225X322525MOB4SI"))
    )
    (comp (ref "C19")
      (value "100nF 25V")
      (footprint "eagle-import:0402")
      (fields (field (name "LCSC_PART") "C56392"))
      (libsource (lib "eagle-import") (part "100NF-25V-0402"))
    )
    (comp (ref "C20")
      (value "100nF 25V")
      (footprint "eagle-import:0402")
      (fields (field (name "LCSC_PART") "C56392"))
      (libsource (lib "eagle-import") (part "100NF-25V-0402"))
    )
    (comp (ref "C33")
      (value "100nF 25V")
      (footprint "eagle-import:0402")
      (fields (field (name "LCSC_PART") "C56392"))
      (libsource (lib "eagle-import") (part "100NF-25V-0402"))
    )
    (comp (ref "C34")
      (value "100nF 25V")
      (footprint "eagle-import:0402")
      (fields (field (name "LCSC_PART") "C56392"))
      (libsource (lib "eagle-import") (part "100NF-25V-0402"))
    )
    (comp (ref "C103")
      (value "100nF 25V")
      (footprint "eagle-import:0201")
      (fields (field (name "LCSC_PART") "C76939"))
      (libsource (lib "eagle-import") (part "100NF-25V-0201"))
    )
    (comp (ref "C106")
      (value "1nF 25V")
      (footprint "eagle-import:0201")
      (fields (field (name "LCSC_PART") "C7694325V"))
      (libsource (lib "eagle-import") (part "1NF-25V-0201"))
    )
    (comp (ref "C107")
      (value "1nF 25V")
      (footprint "eagle-import:0201")
      (fields (field (name "LCSC_PART") "C7694325V"))
      (libsource (lib "eagle-import") (part "1NF-25V-0201"))
    )
    (comp (ref "C108")
      (value "1nF 25V")
      (footprint "eagle-import:0201")
      (fields (field (name "LCSC_PART") "C7694325V"))
      (libsource (lib "eagle-import") (part "1NF-25V-0201"))
    )
    (comp (ref "C109")
      (value "1nF 25V")
      (footprint "eagle-import:0201")
      (fields (field (name "LCSC_PART") "C7694325V"))
      (libsource (lib "eagle-import") (part "1NF-25V-0201"))
    )
    (comp (ref "C110")
      (value "1nF 25V")
      (footprint "eagle-import:0201")
      (fields (field (name "LCSC_PART") "C7694325V"))
      (libsource (lib "eagle-import") (part "1NF-25V-0201"))
    )
    (comp (ref "C111")
      (value "1nF 25V")
      (footprint "eagle-import:0201")
      (fields (field (name "LCSC_PART") "C7694325V"))
      (libsource (lib "eagle-import") (part "1NF-25V-0201"))
    )
    (comp (ref "C112")
      (value "1nF 25V")
      (footprint "eagle-import:0201")
      (fields (field (name "LCSC_PART") "C7694325V"))
      (libsource (lib "eagle-import") (part "1NF-25V-0201"))
    )
    (comp (ref "C113")
      (value "1nF 25V")
      (footprint "eagle-import:0201")
      (fields (field (name "LCSC_PART") "C7694325V"))
      (libsource (lib "eagle-import") (part "1NF-25V-0201"))
    )
    (comp (ref "DAT")
      (value "Blue")
      (footprint "eagle-import:LED-0603")
      (fields (field (name "LCSC_PART") "C965807"))
      (libsource (lib "eagle-import") (part "LED-BLUELED-0603"))
    )
    (comp (ref "IC3")
      (value "ULN2803AFWG")
      (footprint "eagle-import:SO18")
      (fields (field (name "LCSC_PART") "C845537"))
      (libsource (lib "eagle-import") (part "ULN2803"))
    )
    (comp (ref "IC4")
      (value "MCP23017T-E/ML")
      (footprint "eagle-import:QFN28[6X6]ML")
      (fields (field (name "LCSC_PART") "C629439"))
      (libsource (lib "eagle-import") (part "MCP23017-E/ML"))
    )
    (comp (ref "IC9")
      (value "SN74HC151PWR")
      (footprint "eagle-import:TSSOP16")
      (fields (field (name "LCSC_PART") "C2653837"))
      (libsource (lib "eagle-import") (part "SN74HC151PWR"))
    )
    (comp (ref "IC22")
      (value "MCP6001RT-I/OT")
      (footprint "eagle-import:SOT23-5")
      (fields (field (name "LCSC_PART") "C154973"))
      (libsource (lib "eagle-import") (part "MCP6001RT"))
    )
    (comp (ref "OPT1")
      (value "ACPL-247-500E")
      (footprint "eagle-import:SO16")
      (fields (field (name "LCSC_PART") "C188681"))
      (libsource (lib "eagle-import") (part "ACPL-2471"))
    )
    (comp (ref "OPT2")
      (value "ACPL-247-500E")
      (footprint "eagle-import:SO16")
      (fields (field (name "LCSC_PART") "C188681"))
      (libsource (lib "eagle-import") (part "ACPL-2471"))
    )
    (comp (ref "R17")
      (value "330R 1% 1W")
      (footprint "eagle-import:2512")
      (fields (field (name "LCSC_PART") "C620880"))
      (libsource (lib "eagle-import") (part "330R-1%-2512"))
    )
    (comp (ref "R18")
      (value "330R 1% 1W")
      (footprint "eagle-import:2512")
      (fields (field (name "LCSC_PART") "C620880"))
      (libsource (lib "eagle-import") (part "330R-1%-2512"))
    )
    (comp (ref "R19")
      (value "330R 1% 1W")
      (footprint "eagle-import:2512")
      (fields (field (name "LCSC_PART") "C620880"))
      (libsource (lib "eagle-import") (part "330R-1%-2512"))
    )
    (comp (ref "R20")
      (value "330R 1% 1W")
      (footprint "eagle-import:2512")
      (fields (field (name "LCSC_PART") "C620880"))
      (libsource (lib "eagle-import") (part "330R-1%-2512"))
    )
    (comp (ref "R21")
      (value "330R 1% 1W")
      (footprint "eagle-import:2512")
      (fields (field (name "LCSC_PART") "C620880"))
      (libsource (lib "eagle-import") (part "330R-1%-2512"))
    )
    (comp (ref "R22")
      (value "330R 1% 1W")
      (footprint "eagle-import:2512")
      (fields (field (name "LCSC_PART") "C620880"))
      (libsource (lib "eagle-import") (part "330R-1%-2512"))
    )
    (comp (ref "R23")
      (value "330R 1% 1W")
      (footprint "eagle-import:2512")
      (fields (field (name "LCSC_PART") "C620880"))
      (libsource (lib "eagle-import") (part "330R-1%-2512"))
    )
    (comp (ref "R24")
      (value "330R 1% 1W")
      (footprint "eagle-import:2512")
      (fields (field (name "LCSC_PART") "C620880"))
      (libsource (lib "eagle-import") (part "330R-1%-2512"))
    )
    (comp (ref "R57")
      (value "0R 1%")
      (footprint "eagle-import:0402")
      (fields (field (name "LCSC_PART") "C17168"))
      (libsource (lib "eagle-import") (part "0R0402"))
    )
    (comp (ref "R58")
      (value "DNI")
      (footprint "eagle-import:0402")
      (libsource (lib "eagle-import") (part "R0402"))
    )
    (comp (ref "R59")
      (value "1K 1%")
      (footprint "eagle-import:0201")
      (fields (field (name "LCSC_PART") "C270365"))
      (libsource (lib "eagle-import") (part "1K-1%0201"))
    )
    (comp (ref "R63")
      (value "1K 1%")
      (footprint "eagle-import:_0603X4-1206")
      (fields (field (name "LCSC_PART") "C110021"))
      (libsource (lib "eagle-import") (part "1K-1%_ARRAY0603X4-1206"))
    )
    (comp (ref "R64")
      (value "1K 1%")
      (footprint "eagle-import:_0603X4-1206")
      (fields (field (name "LCSC_PART") "C110021"))
      (libsource (lib "eagle-import") (part "1K-1%_ARRAY0603X4-1206"))
    )
    (comp (ref "R89")
      (value "10K 1%")
      (footprint "eagle-import:_0603X4-1206")
      (fields (field (name "LCSC_PART") "C110924"))
      (libsource (lib "eagle-import") (part "10K-1%_ARRAY0603X4-1206"))
    )
    (comp (ref "R90")
      (value "10K 1%")
      (footprint "eagle-import:_0603X4-1206")
      (fields (field (name "LCSC_PART") "C110924"))
      (libsource (lib "eagle-import") (part "10K-1%_ARRAY0603X4-1206"))
    )
    (comp (ref "R91")
      (value "0R 1%")
      (footprint "eagle-import:0402")
      (fields (field (name "LCSC_PART") "C17168"))
      (libsource (lib "eagle-import") (part "0R0402"))
    )
    (comp (ref "R92")
      (value "DNI")
      (footprint "eagle-import:0402")
      (libsource (lib "eagle-import") (part "R0402"))
    )
    (comp (ref "R93")
      (value "4x10K 1206")
      (footprint "eagle-import:742C083103JP")
      (fields
        (field (name "MANUFACTURER") "CTS Resistor Products")
        (field (name "MPN") "742C083103JP")
        (field (name "CREATED_BY") "PCBLayout.com")
      )
      (libsource (lib "eagle-import") (part "742C083103JP"))
    )
    (comp (ref "R122")
      (value "1K 1%")
      (footprint "eagle-import:0402")
      (fields (field (name "LCSC_PART") "C11702"))
      (libsource (lib "eagle-import") (part "1K-1%0402"))
    )
    (comp (ref "R153")
      (value "1K 1%")
      (footprint "eagle-import:0201")
      (fields (field (name "LCSC_PART") "C270365"))
      (libsource (lib "eagle-import") (part "1K-1%0201"))
    )
    (comp (ref "R154")
      (value "1K 1%")
      (footprint "eagle-import:0201")
      (fields (field (name "LCSC_PART") "C270365"))
      (libsource (lib "eagle-import") (part "1K-1%0201"))
    )
    (comp (ref "R155")
      (value "1K 1%")
      (footprint "eagle-import:0201")
      (fields (field (name "LCSC_PART") "C270365"))
      (libsource (lib "eagle-import") (part "1K-1%0201"))
    )
    (comp (ref "R156")
      (value "1K 1%")
      (footprint "eagle-import:0201")
      (fields (field (name "LCSC_PART") "C270365"))
      (libsource (lib "eagle-import") (part "1K-1%0201"))
    )
    (comp (ref "R157")
      (value "1K 1%")
      (footprint "eagle-import:0201")
      (fields (field (name "LCSC_PART") "C270365"))
      (libsource (lib "eagle-import") (part "1K-1%0201"))
    )
    (comp (ref "R158")
      (value "1K 1%")
      (footprint "eagle-import:0201")
      (fields (field (name "LCSC_PART") "C270365"))
      (libsource (lib "eagle-import") (part "1K-1%0201"))
    )
    (comp (ref "R159")
      (value "1K 1%")
      (footprint "eagle-import:0201")
      (fields (field (name "LCSC_PART") "C270365"))
      (libsource (lib "eagle-import") (part "1K-1%0201"))
    )
    (comp (ref "3VDC")
      (value "TP")
      (footprint "eagle-import:TP")
      (libsource (lib "eagle-import") (part "TP"))
    )
    (comp (ref "3VFB")
      (value "TP")
      (footprint "eagle-import:TP")
      (libsource (lib "eagle-import") (part "TP"))
    )
    (comp (ref "5V-NI1")
      (value "TP")
      (footprint "eagle-import:TP")
      (libsource (lib "eagle-import") (part "TP"))
    )
    (comp (ref "5V-NI2")
      (value "TP")
      (footprint "eagle-import:TP")
      (libsource (lib "eagle-import") (part "TP"))
    )
    (comp (ref "5VDC")
      (value "TP")
      (footprint "eagle-import:TP")
      (libsource (lib "eagle-import") (part "TP"))
    )
    (comp (ref "5VFB")
      (value "TP")
      (footprint "eagle-import:TP")
      (libsource (lib "eagle-import") (part "TP"))
    )
    (comp (ref "12VDC")
      (value "TP")
      (footprint "eagle-import:TP")
      (libsource (lib "eagle-import") (part "TP"))
    )
    (comp (ref "AC/DC1")
      (value "IRM_10_12")
      (footprint "eagle-import:IRM_10_12")
      (fields (field (name "LCSC_PART") "C20618065"))
      (libsource (lib "eagle-import") (part "IRM_10_12"))
    )
    (comp (ref "AC/DC2")
      (value "IRM-10-15")
      (footprint "eagle-import:IRM_15_12")
      (fields (field (name "LCSC_PART") "C5439799"))
      (libsource (lib "eagle-import") (part "IRM_10_12-2"))
    )
    (comp (ref "AC_L")
      (value "MOUNT-PAD-ROUND3.0")
      (footprint "eagle-import:3,0-PAD")
      (libsource (lib "eagle-import") (part "MOUNT-PAD-ROUND3.0"))
    )
    (comp (ref "AC_N")
      (value "MOUNT-PAD-ROUND3.0")
      (footprint "eagle-import:3,0-PAD")
      (libsource (lib "eagle-import") (part "MOUNT-PAD-ROUND3.0"))
    )
    (comp (ref "C1")
      (value "22uF 25V")
      (footprint "eagle-import:1206")
      (fields (field (name "LCSC_PART") "C12891"))
      (libsource (lib "eagle-import") (part "22UF-25V-1206"))
    )
    (comp (ref "C2")
      (value "22uF 25V")
      (footprint "eagle-import:1206")
      (fields (field (name "LCSC_PART") "C12891"))
      (libsource (lib "eagle-import") (part "22UF-25V-1206"))
    )
    (comp (ref "C3")
      (value "100nF 25V")
      (footprint "eagle-import:0402")
      (fields (field (name "LCSC_PART") "C56392"))
      (libsource (lib "eagle-import") (part "100NF-25V-0402"))
    )
    (comp (ref "C4")
      (value "100nF 25V")
      (footprint "eagle-import:0402")
      (fields (field (name "LCSC_PART") "C56392"))
      (libsource (lib "eagle-import") (part "100NF-25V-0402"))
    )
    (comp (ref "C5")
      (value "1nF 50V")
      (footprint "eagle-import:0603")
      (fields (field (name "LCSC_PART") "C1588"))
      (libsource (lib "eagle-import") (part "1NF-50V-0603"))
    )
    (comp (ref "C6")
      (value "100nF 25V")
      (footprint "eagle-import:0402")
      (fields (field (name "LCSC_PART") "C56392"))
      (libsource (lib "eagle-import") (part "100NF-25V-0402"))
    )
    (comp (ref "C7")
      (value "100nF 25V")
      (footprint "eagle-import:0402")
      (fields (field (name "LCSC_PART") "C56392"))
      (libsource (lib "eagle-import") (part "100NF-25V-0402"))
    )
    (comp (ref "C8")
      (value "100nF 25V")
      (footprint "eagle-import:0402")
      (fields (field (name "LCSC_PART") "C56392"))
      (libsource (lib "eagle-import") (part "100NF-25V-0402"))
    )
    (comp (ref "C9")
      (value "100nF 25V")
      (footprint "eagle-import:0402")
      (fields (field (name "LCSC_PART") "C56392"))
      (libsource (lib "eagle-import") (part "100NF-25V-0402"))
    )
    (comp (ref "C10")
      (value "100uF 25V")
      (footprint "eagle-import:6.3X7.7(DXL)")
      (fields (field (name "LCSC_PART") "C267469"))
      (libsource (lib "eagle-import") (part "100UF-25V6.3X7.7(DXL)"))
    )
    (comp (ref "C11")
      (value "33pF 50V")
      (footprint "eagle-import:0402")
      (fields (field (name "LCSC_PART") "C107005"))
      (libsource (lib "eagle-import") (part "33PF-50V0402"))
    )
    (comp (ref "C12")
      (value "33pF 50V")
      (footprint "eagle-import:0402")
      (fields (field (name "LCSC_PART") "C107005"))
      (libsource (lib "eagle-import") (part "33PF-50V0402"))
    )
    (comp (ref "C13")
      (value "100uF 25V")
      (footprint "eagle-import:6.3X7.7(DXL)")
      (fields (field (name "LCSC_PART") "C267469"))
      (libsource (lib "eagle-import") (part "100UF-25V6.3X7.7(DXL)"))
    )
    (comp (ref "C14")
      (value "22uF 25V")
      (footprint "eagle-import:1206")
      (fields (field (name "LCSC_PART") "C12891"))
      (libsource (lib "eagle-import") (part "22UF-25V-1206"))
    )
    (comp (ref "C15")
      (value "22uF 25V")
      (footprint "eagle-import:1206")
      (fields (field (name "LCSC_PART") "C12891"))
      (libsource (lib "eagle-import") (part "22UF-25V-1206"))
    )
    (comp (ref "C16")
      (value "100uF 25V")
      (footprint "eagle-import:6.3X7.7(DXL)")
      (fields (field (name "LCSC_PART") "C267469"))
      (libsource (lib "eagle-import") (part "100UF-25V6.3X7.7(DXL)"))
    )
    (comp (ref "C17")
      (value "22uF 25V")
      (footprint "eagle-import:1206")
      (fields (field (name "LCSC_PART") "C12891"))
      (libsource (lib "eagle-import") (part "22UF-25V-1206"))
    )
    (comp (ref "C18")
      (value "22uF 25V")
      (footprint "eagle-import:1206")
      (fields (field (name "LCSC_PART") "C12891"))
      (libsource (lib "eagle-import") (part "22UF-25V-1206"))
    )
    (comp (ref "C21")
      (value "2.2uF 50V")
      (footprint "eagle-import:0603")
      (fields (field (name "LCSC_PART") "C913904"))
      (libsource (lib "eagle-import") (part "2.2UF-50V0603"))
    )
    (comp (ref "C22")
      (value "220nF 50V")
      (footprint "eagle-import:0805")
      (fields (field (name "LCSC_PART") "C5378"))
      (libsource (lib "eagle-import") (part "220NF-50V0805"))
    )
    (comp (ref "C23")
      (value "100uF 50V")
      (footprint "eagle-import:6.3X7.7(DXL)")
      (fields (field (name "LCSC_PART") "C3151829"))
      (libsource (lib "eagle-import") (part "100UF-50V6.3X7.7(DXL)"))
    )
    (comp (ref "C35")
      (value "2.2uF 400V")
      (footprint "eagle-import:6.3X7.7(DXL)")
      (fields (field (name "LCSC_PART") "C3345109"))
      (libsource (lib "eagle-import") (part "2.2UF-400V6.3X7.7(DXL)"))
    )
    (comp (ref "C45")
      (value "1uF 50V")
      (footprint "eagle-import:0805")
      (fields (field (name "LCSC_PART") "C28323"))
      (libsource (lib "eagle-import") (part "1UF-50V0805"))
    )
    (comp (ref "C46")
      (value "2.2uF 50V")
      (footprint "eagle-import:0603")
      (fields (field (name "LCSC_PART") "C913904"))
      (libsource (lib "eagle-import") (part "2.2UF-50V0603"))
    )
    (comp (ref "C47")
      (value "2.2uF 400V")
      (footprint "eagle-import:6.3X7.7(DXL)")
      (fields (field (name "LCSC_PART") "C3345109"))
      (libsource (lib "eagle-import") (part "2.2UF-400V6.3X7.7(DXL)"))
    )
    (comp (ref "C51")
      (value "1nF 50V")
      (footprint "eagle-import:0603")
      (fields (field (name "LCSC_PART") "C1588"))
      (libsource (lib "eagle-import") (part "1NF-50V-0603"))
    )
    (comp (ref "C52")
      (value "220nF 50V")
      (footprint "eagle-import:0805")
      (fields (field (name "LCSC_PART") "C5378"))
      (libsource (lib "eagle-import") (part "220NF-50V0805"))
    )
    (comp (ref "C53")
      (value "100uF 50V")
      (footprint "eagle-import:6.3X7.7(DXL)")
      (fields (field (name "LCSC_PART") "C3151829"))
      (libsource (lib "eagle-import") (part "100UF-50V6.3X7.7(DXL)"))
    )
    (comp (ref "C57")
      (value "1uF 50V")
      (footprint "eagle-import:0805")
      (fields (field (name "LCSC_PART") "C28323"))
      (libsource (lib "eagle-import") (part "1UF-50V0805"))
    )
    (comp (ref "D9")
      (value "1N4007")
      (footprint "eagle-import:SMA_DO-214AC")
      (fields (field (name "LCSC_PART") "C727081"))
      (libsource (lib "eagle-import") (part "1N4007"))
    )
    (comp (ref "D10")
      (value "1N4007")
      (footprint "eagle-import:SMA_DO-214AC")
      (fields (field (name "LCSC_PART") "C727081"))
      (libsource (lib "eagle-import") (part "1N4007"))
    )
    (comp (ref "D11")
      (value "US1J-E3/61T")
      (footprint "eagle-import:SMA_DO-214AC")
      (fields (field (name "LCSC_PART") "C44763"))
      (libsource (lib "eagle-import") (part "US1J-E3/61T"))
    )
    (comp (ref "D12")
      (value "1N4007")
      (footprint "eagle-import:SMA_DO-214AC")
      (fields (field (name "LCSC_PART") "C727081"))
      (libsource (lib "eagle-import") (part "1N4007"))
    )
    (comp (ref "D13")
      (value "1N4007")
      (footprint "eagle-import:SMA_DO-214AC")
      (fields (field (name "LCSC_PART") "C727081"))
      (libsource (lib "eagle-import") (part "1N4007"))
    )
    (comp (ref "D14")
      (value "US1J-E3/61T")
      (footprint "eagle-import:SMA_DO-214AC")
      (fields (field (name "LCSC_PART") "C44763"))
      (libsource (lib "eagle-import") (part "US1J-E3/61T"))
    )
    (comp (ref "D16")
      (value "SMAJ15A")
      (footprint "eagle-import:SMA_DO-214AC")
      (fields (field (name "LCSC_PART") "C23424"))
      (libsource (lib "eagle-import") (part "SMAJ15A"))
    )
    (comp (ref "FB-NI1")
      (value "TP")
      (footprint "eagle-import:TP")
      (libsource (lib "eagle-import") (part "TP"))
    )
    (comp (ref "FB-NI2")
      (value "TP")
      (footprint "eagle-import:TP")
      (libsource (lib "eagle-import") (part "TP"))
    )
    (comp (ref "GND") (value "TP") (footprint "eagle-import:TP") (libsource (lib "eagle-import") (part "TP")))
    (comp (ref "GND-3")
      (value "TP")
      (footprint "eagle-import:TP")
      (libsource (lib "eagle-import") (part "TP"))
    )
    (comp (ref "GND-5")
      (value "TP")
      (footprint "eagle-import:TP")
      (libsource (lib "eagle-import") (part "TP"))
    )
    (comp (ref "IC1")
      (value "MP2315GJ-Z")
      (footprint "eagle-import:SOT65P280X110-8N")
      (fields (field (name "LCSC_PART") "C45889"))
      (libsource (lib "eagle-import") (part "MP2315TSOT23-8"))
    )
    (comp (ref "IC2")
      (value "MP2315GJ-Z")
      (footprint "eagle-import:SOT65P280X110-8N")
      (fields (field (name "LCSC_PART") "C45889"))
      (libsource (lib "eagle-import") (part "MP2315TSOT23-8"))
    )
    (comp (ref "IC5")
      (value "MP150GJ")
      (footprint "eagle-import:SOT23-5")
      (libsource (lib "eagle-import") (part "MP150GJ"))
    )
    (comp (ref "IC13")
      (value "MP150GJ")
      (footprint "eagle-import:SOT23-5")
      (libsource (lib "eagle-import") (part "MP150GJ"))
    )
    (comp (ref "J2") (value "JP") (footprint "eagle-import:SJ") (libsource (lib "eagle-import") (part "SJ")))
    (comp (ref "J7") (value "JP") (footprint "eagle-import:SJ") (libsource (lib "eagle-import") (part "SJ")))
    (comp (ref "J8")
      (value "0R 1%")
      (footprint "eagle-import:0805")
      (fields (field (name "LCSC_PART") "C17477"))
      (libsource (lib "eagle-import") (part "0R0805"))
    )
    (comp (ref "J9")
      (value "0R 1%")
      (footprint "eagle-import:0805")
      (fields (field (name "LCSC_PART") "C17477"))
      (libsource (lib "eagle-import") (part "0R0805"))
    )
    (comp (ref "J10")
      (value "0R 1%")
      (footprint "eagle-import:0805")
      (fields (field (name "LCSC_PART") "C17477"))
      (libsource (lib "eagle-import") (part "0R0805"))
    )
    (comp (ref "L-REC1")
      (value "TP")
      (footprint "eagle-import:TP")
      (libsource (lib "eagle-import") (part "TP"))
    )
    (comp (ref "L-REC2")
      (value "TP")
      (footprint "eagle-import:TP")
      (libsource (lib "eagle-import") (part "TP"))
    )
    (comp (ref "L1")
      (value "4.9uH")
      (footprint "eagle-import:SRR5228A")
      (libsource (lib "eagle-import") (part "L"))
    )
    (comp (ref "L2")
      (value "4.2uH")
      (footprint "eagle-import:SRR5228A")
      (libsource (lib "eagle-import") (part "L"))
    )
    (comp (ref "L3")
      (value "1mH")
      (footprint "eagle-import:L-6.6X6.6")
      (fields (field (name "LCSC_PART") "C168049"))
      (libsource (lib "eagle-import") (part "1MHL-6.6X6.6"))
    )
    (comp (ref "L5")
      (value "1mH")
      (footprint "eagle-import:L-6.6X6.6")
      (fields (field (name "LCSC_PART") "C168049"))
      (libsource (lib "eagle-import") (part "1MHL-6.6X6.6"))
    )
    (comp (ref "P3ON")
      (value "Green")
      (footprint "eagle-import:LED-0603")
      (fields (field (name "LCSC_PART") "C965804"))
      (libsource (lib "eagle-import") (part "LED-GREENLED-0603"))
    )
    (comp (ref "P5ON")
      (value "Green")
      (footprint "eagle-import:LED-0603")
      (fields (field (name "LCSC_PART") "C965804"))
      (libsource (lib "eagle-import") (part "LED-GREENLED-0603"))
    )
    (comp (ref "P12ON")
      (value "Green")
      (footprint "eagle-import:LED-0603")
      (fields (field (name "LCSC_PART") "C965804"))
      (libsource (lib "eagle-import") (part "LED-GREENLED-0603"))
    )
    (comp (ref "R1")
      (value "DNI")
      (footprint "eagle-import:0402")
      (libsource (lib "eagle-import") (part "R0402"))
    )
    (comp (ref "R2")
      (value "10K 1%")
      (footprint "eagle-import:0402")
      (fields (field (name "LCSC_PART") "C25744"))
      (libsource (lib "eagle-import") (part "10K-1%0402"))
    )
    (comp (ref "R3")
      (value "100K 1%")
      (footprint "eagle-import:0402")
      (fields (field (name "LCSC_PART") "C25741"))
      (libsource (lib "eagle-import") (part "100K-1%0402"))
    )
    (comp (ref "R4")
      (value "9.09K 1%")
      (footprint "eagle-import:0402")
      (fields (field (name "LCSC_PART") "C11549"))
      (libsource (lib "eagle-import") (part "9.09K-1%0402"))
    )
    (comp (ref "R5")
      (value "100K 1%")
      (footprint "eagle-import:0402")
      (fields (field (name "LCSC_PART") "C25741"))
      (libsource (lib "eagle-import") (part "100K-1%0402"))
    )
    (comp (ref "R6")
      (value "7.5K 1%")
      (footprint "eagle-import:0402")
      (fields (field (name "LCSC_PART") "C25918"))
      (libsource (lib "eagle-import") (part "7.5K-1%0402"))
    )
    (comp (ref "R7")
      (value "10R 1%")
      (footprint "eagle-import:0402")
      (fields (field (name "LCSC_PART") "C25077"))
      (libsource (lib "eagle-import") (part "10R-1%0402"))
    )
    (comp (ref "R8")
      (value "20K 1%")
      (footprint "eagle-import:0402")
      (fields (field (name "LCSC_PART") "C25765"))
      (libsource (lib "eagle-import") (part "20K-1%0402"))
    )
    (comp (ref "R9")
      (value "10R 1%")
      (footprint "eagle-import:0402")
      (fields (field (name "LCSC_PART") "C25077"))
      (libsource (lib "eagle-import") (part "10R-1%0402"))
    )
    (comp (ref "R10")
      (value "33K")
      (footprint "eagle-import:0402")
      (libsource (lib "eagle-import") (part "R0402"))
    )
    (comp (ref "R11")
      (value "40.2K 1%")
      (footprint "eagle-import:0402")
      (fields (field (name "LCSC_PART") "C25893"))
      (libsource (lib "eagle-import") (part "40.2K-1%0402"))
    )
    (comp (ref "R12")
      (value "7.5K 1%")
      (footprint "eagle-import:0402")
      (fields (field (name "LCSC_PART") "C25918"))
      (libsource (lib "eagle-import") (part "7.5K-1%0402"))
    )
    (comp (ref "R13")
      (value "40.2K 1%")
      (footprint "eagle-import:0402")
      (fields (field (name "LCSC_PART") "C25893"))
      (libsource (lib "eagle-import") (part "40.2K-1%0402"))
    )
    (comp (ref "R14")
      (value "12.7K 1%")
      (footprint "eagle-import:0402")
      (fields (field (name "LCSC_PART") "C25853"))
      (libsource (lib "eagle-import") (part "12.7K-1%0402"))
    )
    (comp (ref "R60")
      (value "4.99K 1%")
      (footprint "eagle-import:0603")
      (fields (field (name "LCSC_PART") "C23046"))
      (libsource (lib "eagle-import") (part "4.99K-1%0603"))
    )
    (comp (ref "R61")
      (value "4.99K 1%")
      (footprint "eagle-import:0603")
      (fields (field (name "LCSC_PART") "C23046"))
      (libsource (lib "eagle-import") (part "4.99K-1%0603"))
    )
    (comp (ref "R62")
      (value "39R 1% 2W")
      (footprint "eagle-import:2512")
      (fields (field (name "LCSC_PART") "C175263"))
      (libsource (lib "eagle-import") (part "39R-1%2512"))
    )
    (comp (ref "R94")
      (value "100K 1%")
      (footprint "eagle-import:0402")
      (fields (field (name "LCSC_PART") "C25741"))
      (libsource (lib "eagle-import") (part "100K-1%0402"))
    )
    (comp (ref "R95")
      (value "10K 1%")
      (footprint "eagle-import:0402")
      (fields (field (name "LCSC_PART") "C25744"))
      (libsource (lib "eagle-import") (part "10K-1%0402"))
    )
    (comp (ref "R96")
      (value "10K 1%")
      (footprint "eagle-import:0805")
      (fields (field (name "LCSC_PART") "C17414"))
      (libsource (lib "eagle-import") (part "10K-1%0805"))
    )
    (comp (ref "R105")
      (value "4.99K 1%")
      (footprint "eagle-import:0603")
      (fields (field (name "LCSC_PART") "C23046"))
      (libsource (lib "eagle-import") (part "4.99K-1%0603"))
    )
    (comp (ref "R106")
      (value "39R 1% 2W")
      (footprint "eagle-import:2512")
      (fields (field (name "LCSC_PART") "C175263"))
      (libsource (lib "eagle-import") (part "39R-1%2512"))
    )
    (comp (ref "R107")
      (value "4.99K 1%")
      (footprint "eagle-import:0603")
      (fields (field (name "LCSC_PART") "C23046"))
      (libsource (lib "eagle-import") (part "4.99K-1%0603"))
    )
    (comp (ref "R108")
      (value "10K 1%")
      (footprint "eagle-import:0805")
      (fields (field (name "LCSC_PART") "C17414"))
      (libsource (lib "eagle-import") (part "10K-1%0805"))
    )
    (comp (ref "R123")
      (value "1K 1%")
      (footprint "eagle-import:0402")
      (fields (field (name "LCSC_PART") "C11702"))
      (libsource (lib "eagle-import") (part "1K-1%0402"))
    )
    (comp (ref "R148")
      (value "2.4K 1%")
      (footprint "eagle-import:0402")
      (fields (field (name "LCSC_PART") "C25882"))
      (libsource (lib "eagle-import") (part "2.4K-1%0402"))
    )
    (comp (ref "R150")
      (value "8.2K 1%")
      (footprint "eagle-import:0402")
      (fields (field (name "LCSC_PART") "C25924"))
      (libsource (lib "eagle-import") (part "8.2K-1%0402"))
    )
    (comp (ref "R161")
      (value "DNI")
      (footprint "eagle-import:0402")
      (libsource (lib "eagle-import") (part "R0402"))
    )
    (comp (ref "R162")
      (value "10K 1%")
      (footprint "eagle-import:0402")
      (fields (field (name "LCSC_PART") "C25744"))
      (libsource (lib "eagle-import") (part "10K-1%0402"))
    )
    (comp (ref "SW") (value "TP") (footprint "eagle-import:TP") (libsource (lib "eagle-import") (part "TP")))
    (comp (ref "SW3") (value "TP") (footprint "eagle-import:TP") (libsource (lib "eagle-import") (part "TP")))
    (comp (ref "VNI1")
      (value "TP")
      (footprint "eagle-import:TP")
      (libsource (lib "eagle-import") (part "TP"))
    )
    (comp (ref "VNI2")
      (value "TP")
      (footprint "eagle-import:TP")
      (libsource (lib "eagle-import") (part "TP"))
    )
    (comp (ref "C24")
      (value "33nF 50V")
      (footprint "eagle-import:0805")
      (fields (field (name "LCSC_PART") "C107150"))
      (libsource (lib "eagle-import") (part "33NF-50V0805"))
    )
    (comp (ref "C25")
      (value "33nF 50V")
      (footprint "eagle-import:0805")
      (fields (field (name "LCSC_PART") "C107150"))
      (libsource (lib "eagle-import") (part "33NF-50V0805"))
    )
    (comp (ref "C26")
      (value "33nF 50V")
      (footprint "eagle-import:0805")
      (fields (field (name "LCSC_PART") "C107150"))
      (libsource (lib "eagle-import") (part "33NF-50V0805"))
    )
    (comp (ref "C27")
      (value "33nF 50V")
      (footprint "eagle-import:0805")
      (fields (field (name "LCSC_PART") "C107150"))
      (libsource (lib "eagle-import") (part "33NF-50V0805"))
    )
    (comp (ref "C28")
      (value "33nF 50V")
      (footprint "eagle-import:0805")
      (fields (field (name "LCSC_PART") "C107150"))
      (libsource (lib "eagle-import") (part "33NF-50V0805"))
    )
    (comp (ref "C29")
      (value "33nF 50V")
      (footprint "eagle-import:0805")
      (fields (field (name "LCSC_PART") "C107150"))
      (libsource (lib "eagle-import") (part "33NF-50V0805"))
    )
    (comp (ref "C30")
      (value "33nF 50V")
      (footprint "eagle-import:0805")
      (fields (field (name "LCSC_PART") "C107150"))
      (libsource (lib "eagle-import") (part "33NF-50V0805"))
    )
    (comp (ref "C31")
      (value "33nF 50V")
      (footprint "eagle-import:0805")
      (fields (field (name "LCSC_PART") "C107150"))
      (libsource (lib "eagle-import") (part "33NF-50V0805"))
    )
    (comp (ref "C32")
      (value "33nF 50V")
      (footprint "eagle-import:0805")
      (fields (field (name "LCSC_PART") "C107150"))
      (libsource (lib "eagle-import") (part "33NF-50V0805"))
    )
    (comp (ref "C36")
      (value "33nF 50V")
      (footprint "eagle-import:0805")
      (fields (field (name "LCSC_PART") "C107150"))
      (libsource (lib "eagle-import") (part "33NF-50V0805"))
    )
    (comp (ref "C37")
      (value "33nF 50V")
      (footprint "eagle-import:0805")
      (fields (field (name "LCSC_PART") "C107150"))
      (libsource (lib "eagle-import") (part "33NF-50V0805"))
    )
    (comp (ref "C38")
      (value "33nF 50V")
      (footprint "eagle-import:0805")
      (fields (field (name "LCSC_PART") "C107150"))
      (libsource (lib "eagle-import") (part "33NF-50V0805"))
    )
    (comp (ref "C39")
      (value "33nF 50V")
      (footprint "eagle-import:0805")
      (fields (field (name "LCSC_PART") "C107150"))
      (libsource (lib "eagle-import") (part "33NF-50V0805"))
    )
    (comp (ref "C40")
      (value "33nF 50V")
      (footprint "eagle-import:0805")
      (fields (field (name "LCSC_PART") "C107150"))
      (libsource (lib "eagle-import") (part "33NF-50V0805"))
    )
    (comp (ref "C41")
      (value "33nF 50V")
      (footprint "eagle-import:0805")
      (fields (field (name "LCSC_PART") "C107150"))
      (libsource (lib "eagle-import") (part "33NF-50V0805"))
    )
    (comp (ref "C42")
      (value "33nF 50V")
      (footprint "eagle-import:0805")
      (fields (field (name "LCSC_PART") "C107150"))
      (libsource (lib "eagle-import") (part "33NF-50V0805"))
    )
    (comp (ref "C43")
      (value "33nF 50V")
      (footprint "eagle-import:0805")
      (fields (field (name "LCSC_PART") "C107150"))
      (libsource (lib "eagle-import") (part "33NF-50V0805"))
    )
    (comp (ref "C44")
      (value "33nF 50V")
      (footprint "eagle-import:0805")
      (fields (field (name "LCSC_PART") "C107150"))
      (libsource (lib "eagle-import") (part "33NF-50V0805"))
    )
    (comp (ref "C48")
      (value "33nF 50V")
      (footprint "eagle-import:0805")
      (fields (field (name "LCSC_PART") "C107150"))
      (libsource (lib "eagle-import") (part "33NF-50V0805"))
    )
    (comp (ref "C49")
      (value "33nF 50V")
      (footprint "eagle-import:0805")
      (fields (field (name "LCSC_PART") "C107150"))
      (libsource (lib "eagle-import") (part "33NF-50V0805"))
    )
    (comp (ref "C50")
      (value "33nF 50V")
      (footprint "eagle-import:0805")
      (fields (field (name "LCSC_PART") "C107150"))
      (libsource (lib "eagle-import") (part "33NF-50V0805"))
    )
    (comp (ref "C54")
      (value "33nF 50V")
      (footprint "eagle-import:0805")
      (fields (field (name "LCSC_PART") "C107150"))
      (libsource (lib "eagle-import") (part "33NF-50V0805"))
    )
    (comp (ref "C55")
      (value "33nF 50V")
      (footprint "eagle-import:0805")
      (fields (field (name "LCSC_PART") "C107150"))
      (libsource (lib "eagle-import") (part "33NF-50V0805"))
    )
    (comp (ref "C56")
      (value "33nF 50V")
      (footprint "eagle-import:0805")
      (fields (field (name "LCSC_PART") "C107150"))
      (libsource (lib "eagle-import") (part "33NF-50V0805"))
    )
    (comp (ref "IC6")
      (value "HLW8032")
      (footprint "eagle-import:SO8")
      (fields (field (name "LCSC_PART") "C128023"))
      (libsource (lib "eagle-import") (part "HLW8032"))
    )
    (comp (ref "IC7")
      (value "HLW8032")
      (footprint "eagle-import:SO8")
      (fields (field (name "LCSC_PART") "C128023"))
      (libsource (lib "eagle-import") (part "HLW8032"))
    )
    (comp (ref "IC8")
      (value "HLW8032")
      (footprint "eagle-import:SO8")
      (fields (field (name "LCSC_PART") "C128023"))
      (libsource (lib "eagle-import") (part "HLW8032"))
    )
    (comp (ref "IC10")
      (value "HLW8032")
      (footprint "eagle-import:SO8")
      (fields (field (name "LCSC_PART") "C128023"))
      (libsource (lib "eagle-import") (part "HLW8032"))
    )
    (comp (ref "IC11")
      (value "HLW8032")
      (footprint "eagle-import:SO8")
      (fields (field (name "LCSC_PART") "C128023"))
      (libsource (lib "eagle-import") (part "HLW8032"))
    )
    (comp (ref "IC12")
      (value "HLW8032")
      (footprint "eagle-import:SO8")
      (fields (field (name "LCSC_PART") "C128023"))
      (libsource (lib "eagle-import") (part "HLW8032"))
    )
    (comp (ref "IC14")
      (value "HLW8032")
      (footprint "eagle-import:SO8")
      (fields (field (name "LCSC_PART") "C128023"))
      (libsource (lib "eagle-import") (part "HLW8032"))
    )
    (comp (ref "IC16")
      (value "HLW8032")
      (footprint "eagle-import:SO8")
      (fields (field (name "LCSC_PART") "C128023"))
      (libsource (lib "eagle-import") (part "HLW8032"))
    )
    (comp (ref "L_OUT1")
      (value "MOUNT-PAD-ROUND2.8")
      (footprint "eagle-import:2,8-PAD")
      (libsource (lib "eagle-import") (part "MOUNT-PAD-ROUND2.8"))
    )
    (comp (ref "L_OUT2")
      (value "MOUNT-PAD-ROUND2.8")
      (footprint "eagle-import:2,8-PAD")
      (libsource (lib "eagle-import") (part "MOUNT-PAD-ROUND2.8"))
    )
    (comp (ref "L_OUT3")
      (value "MOUNT-PAD-ROUND2.8")
      (footprint "eagle-import:2,8-PAD")
      (libsource (lib "eagle-import") (part "MOUNT-PAD-ROUND2.8"))
    )
    (comp (ref "L_OUT4")
      (value "MOUNT-PAD-ROUND2.8")
      (footprint "eagle-import:2,8-PAD")
      (libsource (lib "eagle-import") (part "MOUNT-PAD-ROUND2.8"))
    )
    (comp (ref "L_OUT5")
      (value "MOUNT-PAD-ROUND2.8")
      (footprint "eagle-import:2,8-PAD")
      (libsource (lib "eagle-import") (part "MOUNT-PAD-ROUND2.8"))
    )
    (comp (ref "L_OUT6")
      (value "MOUNT-PAD-ROUND2.8")
      (footprint "eagle-import:2,8-PAD")
      (libsource (lib "eagle-import") (part "MOUNT-PAD-ROUND2.8"))
    )
    (comp (ref "L_OUT7")
      (value "MOUNT-PAD-ROUND2.8")
      (footprint "eagle-import:2,8-PAD")
      (libsource (lib "eagle-import") (part "MOUNT-PAD-ROUND2.8"))
    )
    (comp (ref "L_OUT8")
      (value "MOUNT-PAD-ROUND2.8")
      (footprint "eagle-import:2,8-PAD")
      (libsource (lib "eagle-import") (part "MOUNT-PAD-ROUND2.8"))
    )
    (comp (ref "N_OUT1")
      (value "MOUNT-PAD-ROUND2.8")
      (footprint "eagle-import:2,8-PAD")
      (libsource (lib "eagle-import") (part "MOUNT-PAD-ROUND2.8"))
    )
    (comp (ref "N_OUT2")
      (value "MOUNT-PAD-ROUND2.8")
      (footprint "eagle-import:2,8-PAD")
      (libsource (lib "eagle-import") (part "MOUNT-PAD-ROUND2.8"))
    )
    (comp (ref "N_OUT3")
      (value "MOUNT-PAD-ROUND2.8")
      (footprint "eagle-import:2,8-PAD")
      (libsource (lib "eagle-import") (part "MOUNT-PAD-ROUND2.8"))
    )
    (comp (ref "N_OUT4")
      (value "MOUNT-PAD-ROUND2.8")
      (footprint "eagle-import:2,8-PAD")
      (libsource (lib "eagle-import") (part "MOUNT-PAD-ROUND2.8"))
    )
    (comp (ref "N_OUT5")
      (value "MOUNT-PAD-ROUND2.8")
      (footprint "eagle-import:2,8-PAD")
      (libsource (lib "eagle-import") (part "MOUNT-PAD-ROUND2.8"))
    )
    (comp (ref "N_OUT6")
      (value "MOUNT-PAD-ROUND2.8")
      (footprint "eagle-import:2,8-PAD")
      (libsource (lib "eagle-import") (part "MOUNT-PAD-ROUND2.8"))
    )
    (comp (ref "N_OUT7")
      (value "MOUNT-PAD-ROUND2.8")
      (footprint "eagle-import:2,8-PAD")
      (libsource (lib "eagle-import") (part "MOUNT-PAD-ROUND2.8"))
    )
    (comp (ref "N_OUT8")
      (value "MOUNT-PAD-ROUND2.8")
      (footprint "eagle-import:2,8-PAD")
      (libsource (lib "eagle-import") (part "MOUNT-PAD-ROUND2.8"))
    )
    (comp (ref "R25")
      (value "0.002R 1%")
      (footprint "eagle-import:2512")
      (fields (field (name "LCSC_PART") "C728320"))
      (libsource (lib "eagle-import") (part "0.002R-1%2512"))
    )
    (comp (ref "R26")
      (value "0.002R 1%")
      (footprint "eagle-import:2512")
      (fields (field (name "LCSC_PART") "C728320"))
      (libsource (lib "eagle-import") (part "0.002R-1%2512"))
    )
    (comp (ref "R27")
      (value "0.002R 1%")
      (footprint "eagle-import:2512")
      (fields (field (name "LCSC_PART") "C728320"))
      (libsource (lib "eagle-import") (part "0.002R-1%2512"))
    )
    (comp (ref "R28")
      (value "0.002R 1%")
      (footprint "eagle-import:2512")
      (fields (field (name "LCSC_PART") "C728320"))
      (libsource (lib "eagle-import") (part "0.002R-1%2512"))
    )
    (comp (ref "R29")
      (value "0.002R 1%")
      (footprint "eagle-import:2512")
      (fields (field (name "LCSC_PART") "C728320"))
      (libsource (lib "eagle-import") (part "0.002R-1%2512"))
    )
    (comp (ref "R30")
      (value "0.002R 1%")
      (footprint "eagle-import:2512")
      (fields (field (name "LCSC_PART") "C728320"))
      (libsource (lib "eagle-import") (part "0.002R-1%2512"))
    )
    (comp (ref "R31")
      (value "0.002R 1%")
      (footprint "eagle-import:2512")
      (fields (field (name "LCSC_PART") "C728320"))
      (libsource (lib "eagle-import") (part "0.002R-1%2512"))
    )
    (comp (ref "R32")
      (value "0.002R 1%")
      (footprint "eagle-import:2512")
      (fields (field (name "LCSC_PART") "C728320"))
      (libsource (lib "eagle-import") (part "0.002R-1%2512"))
    )
    (comp (ref "R33")
      (value "1K 1%")
      (footprint "eagle-import:0805")
      (fields (field (name "LCSC_PART") "C17513"))
      (libsource (lib "eagle-import") (part "1K-1%0805"))
    )
    (comp (ref "R34")
      (value "1K 1%")
      (footprint "eagle-import:0805")
      (fields (field (name "LCSC_PART") "C17513"))
      (libsource (lib "eagle-import") (part "1K-1%0805"))
    )
    (comp (ref "R35")
      (value "0.002R 1%")
      (footprint "eagle-import:2512")
      (fields (field (name "LCSC_PART") "C728320"))
      (libsource (lib "eagle-import") (part "0.002R-1%2512"))
    )
    (comp (ref "R36")
      (value "470K 1%")
      (footprint "eagle-import:0805")
      (fields (field (name "LCSC_PART") "C17709"))
      (libsource (lib "eagle-import") (part "470K-1%0805"))
    )
    (comp (ref "R37")
      (value "470K 1%")
      (footprint "eagle-import:0805")
      (fields (field (name "LCSC_PART") "C17709"))
      (libsource (lib "eagle-import") (part "470K-1%0805"))
    )
    (comp (ref "R38")
      (value "470K 1%")
      (footprint "eagle-import:0805")
      (fields (field (name "LCSC_PART") "C17709"))
      (libsource (lib "eagle-import") (part "470K-1%0805"))
    )
    (comp (ref "R39")
      (value "470K 1%")
      (footprint "eagle-import:0805")
      (fields (field (name "LCSC_PART") "C17709"))
      (libsource (lib "eagle-import") (part "470K-1%0805"))
    )
    (comp (ref "R40")
      (value "1K 1%")
      (footprint "eagle-import:0805")
      (fields (field (name "LCSC_PART") "C17513"))
      (libsource (lib "eagle-import") (part "1K-1%0805"))
    )
    (comp (ref "R41")
      (value "1K 1%")
      (footprint "eagle-import:0805")
      (fields (field (name "LCSC_PART") "C17513"))
      (libsource (lib "eagle-import") (part "1K-1%0805"))
    )
    (comp (ref "R42")
      (value "1K 1%")
      (footprint "eagle-import:0805")
      (fields (field (name "LCSC_PART") "C17513"))
      (libsource (lib "eagle-import") (part "1K-1%0805"))
    )
    (comp (ref "R43")
      (value "0.002R 1%")
      (footprint "eagle-import:2512")
      (fields (field (name "LCSC_PART") "C728320"))
      (libsource (lib "eagle-import") (part "0.002R-1%2512"))
    )
    (comp (ref "R44")
      (value "470K 1%")
      (footprint "eagle-import:0805")
      (fields (field (name "LCSC_PART") "C17709"))
      (libsource (lib "eagle-import") (part "470K-1%0805"))
    )
    (comp (ref "R45")
      (value "470K 1%")
      (footprint "eagle-import:0805")
      (fields (field (name "LCSC_PART") "C17709"))
      (libsource (lib "eagle-import") (part "470K-1%0805"))
    )
    (comp (ref "R46")
      (value "470K 1%")
      (footprint "eagle-import:0805")
      (fields (field (name "LCSC_PART") "C17709"))
      (libsource (lib "eagle-import") (part "470K-1%0805"))
    )
    (comp (ref "R47")
      (value "470K 1%")
      (footprint "eagle-import:0805")
      (fields (field (name "LCSC_PART") "C17709"))
      (libsource (lib "eagle-import") (part "470K-1%0805"))
    )
    (comp (ref "R48")
      (value "1K 1%")
      (footprint "eagle-import:0805")
      (fields (field (name "LCSC_PART") "C17513"))
      (libsource (lib "eagle-import") (part "1K-1%0805"))
    )
    (comp (ref "R49")
      (value "1K 1%")
      (footprint "eagle-import:0805")
      (fields (field (name "LCSC_PART") "C17513"))
      (libsource (lib "eagle-import") (part "1K-1%0805"))
    )
    (comp (ref "R50")
      (value "1K 1%")
      (footprint "eagle-import:0805")
      (fields (field (name "LCSC_PART") "C17513"))
      (libsource (lib "eagle-import") (part "1K-1%0805"))
    )
    (comp (ref "R51")
      (value "0.002R 1%")
      (footprint "eagle-import:2512")
      (fields (field (name "LCSC_PART") "C728320"))
      (libsource (lib "eagle-import") (part "0.002R-1%2512"))
    )
    (comp (ref "R52")
      (value "470K 1%")
      (footprint "eagle-import:0805")
      (fields (field (name "LCSC_PART") "C17709"))
      (libsource (lib "eagle-import") (part "470K-1%0805"))
    )
    (comp (ref "R53")
      (value "470K 1%")
      (footprint "eagle-import:0805")
      (fields (field (name "LCSC_PART") "C17709"))
      (libsource (lib "eagle-import") (part "470K-1%0805"))
    )
    (comp (ref "R54")
      (value "470K 1%")
      (footprint "eagle-import:0805")
      (fields (field (name "LCSC_PART") "C17709"))
      (libsource (lib "eagle-import") (part "470K-1%0805"))
    )
    (comp (ref "R55")
      (value "470K 1%")
      (footprint "eagle-import:0805")
      (fields (field (name "LCSC_PART") "C17709"))
      (libsource (lib "eagle-import") (part "470K-1%0805"))
    )
    (comp (ref "R56")
      (value "1K 1%")
      (footprint "eagle-import:0805")
      (fields (field (name "LCSC_PART") "C17513"))
      (libsource (lib "eagle-import") (part "1K-1%0805"))
    )
    (comp (ref "R65")
      (value "1K 1%")
      (footprint "eagle-import:0805")
      (fields (field (name "LCSC_PART") "C17513"))
      (libsource (lib "eagle-import") (part "1K-1%0805"))
    )
    (comp (ref "R66")
      (value "1K 1%")
      (footprint "eagle-import:0805")
      (fields (field (name "LCSC_PART") "C17513"))
      (libsource (lib "eagle-import") (part "1K-1%0805"))
    )
    (comp (ref "R67")
      (value "0.002R 1%")
      (footprint "eagle-import:2512")
      (fields (field (name "LCSC_PART") "C728320"))
      (libsource (lib "eagle-import") (part "0.002R-1%2512"))
    )
    (comp (ref "R68")
      (value "470K 1%")
      (footprint "eagle-import:0805")
      (fields (field (name "LCSC_PART") "C17709"))
      (libsource (lib "eagle-import") (part "470K-1%0805"))
    )
    (comp (ref "R69")
      (value "470K 1%")
      (footprint "eagle-import:0805")
      (fields (field (name "LCSC_PART") "C17709"))
      (libsource (lib "eagle-import") (part "470K-1%0805"))
    )
    (comp (ref "R70")
      (value "470K 1%")
      (footprint "eagle-import:0805")
      (fields (field (name "LCSC_PART") "C17709"))
      (libsource (lib "eagle-import") (part "470K-1%0805"))
    )
    (comp (ref "R71")
      (value "470K 1%")
      (footprint "eagle-import:0805")
      (fields (field (name "LCSC_PART") "C17709"))
      (libsource (lib "eagle-import") (part "470K-1%0805"))
    )
    (comp (ref "R72")
      (value "1K 1%")
      (footprint "eagle-import:0805")
      (fields (field (name "LCSC_PART") "C17513"))
      (libsource (lib "eagle-import") (part "1K-1%0805"))
    )
    (comp (ref "R73")
      (value "1K 1%")
      (footprint "eagle-import:0805")
      (fields (field (name "LCSC_PART") "C17513"))
      (libsource (lib "eagle-import") (part "1K-1%0805"))
    )
    (comp (ref "R74")
      (value "1K 1%")
      (footprint "eagle-import:0805")
      (fields (field (name "LCSC_PART") "C17513"))
      (libsource (lib "eagle-import") (part "1K-1%0805"))
    )
    (comp (ref "R75")
      (value "0.002R 1%")
      (footprint "eagle-import:2512")
      (fields (field (name "LCSC_PART") "C728320"))
      (libsource (lib "eagle-import") (part "0.002R-1%2512"))
    )
    (comp (ref "R76")
      (value "470K 1%")
      (footprint "eagle-import:0805")
      (fields (field (name "LCSC_PART") "C17709"))
      (libsource (lib "eagle-import") (part "470K-1%0805"))
    )
    (comp (ref "R77")
      (value "470K 1%")
      (footprint "eagle-import:0805")
      (fields (field (name "LCSC_PART") "C17709"))
      (libsource (lib "eagle-import") (part "470K-1%0805"))
    )
    (comp (ref "R78")
      (value "470K 1%")
      (footprint "eagle-import:0805")
      (fields (field (name "LCSC_PART") "C17709"))
      (libsource (lib "eagle-import") (part "470K-1%0805"))
    )
    (comp (ref "R79")
      (value "470K 1%")
      (footprint "eagle-import:0805")
      (fields (field (name "LCSC_PART") "C17709"))
      (libsource (lib "eagle-import") (part "470K-1%0805"))
    )
    (comp (ref "R80")
      (value "1K 1%")
      (footprint "eagle-import:0805")
      (fields (field (name "LCSC_PART") "C17513"))
      (libsource (lib "eagle-import") (part "1K-1%0805"))
    )
    (comp (ref "R81")
      (value "1K 1%")
      (footprint "eagle-import:0805")
      (fields (field (name "LCSC_PART") "C17513"))
      (libsource (lib "eagle-import") (part "1K-1%0805"))
    )
    (comp (ref "R82")
      (value "1K 1%")
      (footprint "eagle-import:0805")
      (fields (field (name "LCSC_PART") "C17513"))
      (libsource (lib "eagle-import") (part "1K-1%0805"))
    )
    (comp (ref "R83")
      (value "0.002R 1%")
      (footprint "eagle-import:2512")
      (fields (field (name "LCSC_PART") "C728320"))
      (libsource (lib "eagle-import") (part "0.002R-1%2512"))
    )
    (comp (ref "R84")
      (value "470K 1%")
      (footprint "eagle-import:0805")
      (fields (field (name "LCSC_PART") "C17709"))
      (libsource (lib "eagle-import") (part "470K-1%0805"))
    )
    (comp (ref "R85")
      (value "470K 1%")
      (footprint "eagle-import:0805")
      (fields (field (name "LCSC_PART") "C17709"))
      (libsource (lib "eagle-import") (part "470K-1%0805"))
    )
    (comp (ref "R86")
      (value "470K 1%")
      (footprint "eagle-import:0805")
      (fields (field (name "LCSC_PART") "C17709"))
      (libsource (lib "eagle-import") (part "470K-1%0805"))
    )
    (comp (ref "R87")
      (value "470K 1%")
      (footprint "eagle-import:0805")
      (fields (field (name "LCSC_PART") "C17709"))
      (libsource (lib "eagle-import") (part "470K-1%0805"))
    )
    (comp (ref "R88")
      (value "1K 1%")
      (footprint "eagle-import:0805")
      (fields (field (name "LCSC_PART") "C17513"))
      (libsource (lib "eagle-import") (part "1K-1%0805"))
    )
    (comp (ref "R97")
      (value "1K 1%")
      (footprint "eagle-import:0805")
      (fields (field (name "LCSC_PART") "C17513"))
      (libsource (lib "eagle-import") (part "1K-1%0805"))
    )
    (comp (ref "R98")
      (value "1K 1%")
      (footprint "eagle-import:0805")
      (fields (field (name "LCSC_PART") "C17513"))
      (libsource (lib "eagle-import") (part "1K-1%0805"))
    )
    (comp (ref "R99")
      (value "0.002R 1%")
      (footprint "eagle-import:2512")
      (fields (field (name "LCSC_PART") "C728320"))
      (libsource (lib "eagle-import") (part "0.002R-1%2512"))
    )
    (comp (ref "R100")
      (value "470K 1%")
      (footprint "eagle-import:0805")
      (fields (field (name "LCSC_PART") "C17709"))
      (libsource (lib "eagle-import") (part "470K-1%0805"))
    )
    (comp (ref "R101")
      (value "470K 1%")
      (footprint "eagle-import:0805")
      (fields (field (name "LCSC_PART") "C17709"))
      (libsource (lib "eagle-import") (part "470K-1%0805"))
    )
    (comp (ref "R102")
      (value "470K 1%")
      (footprint "eagle-import:0805")
      (fields (field (name "LCSC_PART") "C17709"))
      (libsource (lib "eagle-import") (part "470K-1%0805"))
    )
    (comp (ref "R103")
      (value "470K 1%")
      (footprint "eagle-import:0805")
      (fields (field (name "LCSC_PART") "C17709"))
      (libsource (lib "eagle-import") (part "470K-1%0805"))
    )
    (comp (ref "R104")
      (value "1K 1%")
      (footprint "eagle-import:0805")
      (fields (field (name "LCSC_PART") "C17513"))
      (libsource (lib "eagle-import") (part "1K-1%0805"))
    )
    (comp (ref "R113")
      (value "1K 1%")
      (footprint "eagle-import:0805")
      (fields (field (name "LCSC_PART") "C17513"))
      (libsource (lib "eagle-import") (part "1K-1%0805"))
    )
    (comp (ref "R114")
      (value "1K 1%")
      (footprint "eagle-import:0805")
      (fields (field (name "LCSC_PART") "C17513"))
      (libsource (lib "eagle-import") (part "1K-1%0805"))
    )
    (comp (ref "R115")
      (value "0.002R 1%")
      (footprint "eagle-import:2512")
      (fields (field (name "LCSC_PART") "C728320"))
      (libsource (lib "eagle-import") (part "0.002R-1%2512"))
    )
    (comp (ref "R116")
      (value "470K 1%")
      (footprint "eagle-import:0805")
      (fields (field (name "LCSC_PART") "C17709"))
      (libsource (lib "eagle-import") (part "470K-1%0805"))
    )
    (comp (ref "R117")
      (value "470K 1%")
      (footprint "eagle-import:0805")
      (fields (field (name "LCSC_PART") "C17709"))
      (libsource (lib "eagle-import") (part "470K-1%0805"))
    )
    (comp (ref "R118")
      (value "470K 1%")
      (footprint "eagle-import:0805")
      (fields (field (name "LCSC_PART") "C17709"))
      (libsource (lib "eagle-import") (part "470K-1%0805"))
    )
    (comp (ref "R119")
      (value "470K 1%")
      (footprint "eagle-import:0805")
      (fields (field (name "LCSC_PART") "C17709"))
      (libsource (lib "eagle-import") (part "470K-1%0805"))
    )
    (comp (ref "R120")
      (value "1K 1%")
      (footprint "eagle-import:0805")
      (fields (field (name "LCSC_PART") "C17513"))
      (libsource (lib "eagle-import") (part "1K-1%0805"))
    )
  )
  (nets
    (net (code "1") (name "+1V1") (class "Default")
      (node (ref "C75") (pin "1") (pinfunction "1_1") (pintype "passive"))
      (node (ref "C76") (pin "1") (pinfunction "1_1") (pintype "passive"))
      (node (ref "C77") (pin "1") (pinfunction "1_1") (pintype "passive"))
      (node (ref "DVDD") (pin "TP") (pinfunction "P$1_TP") (pintype "bidirectional"))
      (node (ref "IC15") (pin "23") (pinfunction "DVDD_23") (pintype "bidirectional"))
      (node (ref "IC15") (pin "45") (pinfunction "VREG_VOUT_45") (pintype "bidirectional"))
      (node (ref "IC15") (pin "50") (pinfunction "DVDD_50") (pintype "bidirectional"))
    )
    (net (code "2") (name "+3V3") (class "Default")
      (node (ref "3VDC") (pin "TP") (pinfunction "P$1_TP") (pintype "bidirectional"))
      (node (ref "C103") (pin "1") (pinfunction "1_1") (pintype "passive"))
      (node (ref "C12") (pin "1") (pinfunction "1_1") (pintype "passive"))
      (node (ref "C15") (pin "1") (pinfunction "1_1") (pintype "passive"))
      (node (ref "C18") (pin "1") (pinfunction "1_1") (pintype "passive"))
      (node (ref "C19") (pin "1") (pinfunction "1_1") (pintype "passive"))
      (node (ref "C20") (pin "1") (pinfunction "1_1") (pintype "passive"))
      (node (ref "C33") (pin "1") (pinfunction "1_1") (pintype "passive"))
      (node (ref "C34") (pin "1") (pinfunction "1_1") (pintype "passive"))
      (node (ref "C88") (pin "1") (pinfunction "1_1") (pintype "passive"))
      (node (ref "C89") (pin "1") (pinfunction "1_1") (pintype "passive"))
      (node (ref "C90") (pin "1") (pinfunction "1_1") (pintype "passive"))
      (node (ref "DSP") (pin "1") (pinfunction "1_1") (pintype "bidirectional"))
      (node (ref "DSP") (pin "2") (pinfunction "2_2") (pintype "bidirectional"))
      (node (ref "ETH1") (pin "10") (pinfunction "GREEN+_10") (pintype "passive"))
      (node (ref "ETH1") (pin "12") (pinfunction "YELLOW+_12") (pintype "passive"))
      (node (ref "IC20") (pin "28") (pinfunction "VDD_28") (pintype "power_in"))
      (node (ref "IC20") (pin "43") (pinfunction "PMODE2_43") (pintype "input"))
      (node (ref "IC20") (pin "44") (pinfunction "PMODE1_44") (pintype "input"))
      (node (ref "IC20") (pin "45") (pinfunction "PMODE0_45") (pintype "input"))
      (node (ref "IC22") (pin "2") (pinfunction "V+_2") (pintype "power_in"))
      (node (ref "IC4") (pin "5") (pinfunction "VDD_5") (pintype "bidirectional"))
      (node (ref "IC9") (pin "16") (pinfunction "VCC_16") (pintype "power_in"))
      (node (ref "L2") (pin "2") (pinfunction "2_2") (pintype "passive"))
      (node (ref "L4") (pin "1") (pinfunction "1_1") (pintype "passive"))
      (node (ref "R123") (pin "1") (pinfunction "1_1") (pintype "passive"))
      (node (ref "R13") (pin "1") (pinfunction "1_1") (pintype "passive"))
      (node (ref "R145") (pin "2") (pinfunction "2_2") (pintype "passive"))
      (node (ref "R147") (pin "2") (pinfunction "2_2") (pintype "passive"))
      (node (ref "R149") (pin "A1") (pinfunction "1_A1") (pintype "passive"))
      (node (ref "R149") (pin "B1") (pinfunction "2_B1") (pintype "passive"))
      (node (ref "R149") (pin "C1") (pinfunction "3_C1") (pintype "passive"))
      (node (ref "R149") (pin "D1") (pinfunction "4_D1") (pintype "passive"))
      (node (ref "R89") (pin "A2") (pinfunction "8_A2") (pintype "passive"))
      (node (ref "R89") (pin "B2") (pinfunction "7_B2") (pintype "passive"))
      (node (ref "R89") (pin "C2") (pinfunction "6_C2") (pintype "passive"))
      (node (ref "R89") (pin "D2") (pinfunction "5_D2") (pintype "passive"))
      (node (ref "R90") (pin "A2") (pinfunction "8_A2") (pintype "passive"))
      (node (ref "R90") (pin "B2") (pinfunction "7_B2") (pintype "passive"))
      (node (ref "R90") (pin "C2") (pinfunction "6_C2") (pintype "passive"))
      (node (ref "R90") (pin "D2") (pinfunction "5_D2") (pintype "passive"))
    )
    (net (code "3") (name "+3V3_A") (class "Default")
      (node (ref "C91") (pin "1") (pinfunction "1_1") (pintype "passive"))
      (node (ref "C92") (pin "1") (pinfunction "1_1") (pintype "passive"))
      (node (ref "C93") (pin "1") (pinfunction "1_1") (pintype "passive"))
      (node (ref "C94") (pin "1") (pinfunction "1_1") (pintype "passive"))
      (node (ref "C95") (pin "1") (pinfunction "1_1") (pintype "passive"))
      (node (ref "C96") (pin "1") (pinfunction "1_1") (pintype "passive"))
      (node (ref "IC20") (pin "11") (pinfunction "AVDD_11") (pintype "power_in"))
      (node (ref "IC20") (pin "15") (pinfunction "AVDD_15") (pintype "power_in"))
      (node (ref "IC20") (pin "17") (pinfunction "AVDD_17") (pintype "power_in"))
      (node (ref "IC20") (pin "21") (pinfunction "AVDD_21") (pintype "power_in"))
      (node (ref "IC20") (pin "4") (pinfunction "AVDD_4") (pintype "power_in"))
      (node (ref "IC20") (pin "8") (pinfunction "AVDD_8") (pintype "power_in"))
      (node (ref "L4") (pin "2") (pinfunction "2_2") (pintype "passive"))
      (node (ref "R139") (pin "2") (pinfunction "2_2") (pintype "passive"))
      (node (ref "R140") (pin "2") (pinfunction "2_2") (pintype "passive"))
      (node (ref "R146") (pin "2") (pinfunction "2_2") (pintype "passive"))
    )
    (net (code "4") (name "+3V3_MCU") (class "Default")
      (node (ref "C100") (pin "1") (pinfunction "1_1") (pintype "passive"))
      (node (ref "C101") (pin "1") (pinfunction "1_1") (pintype "passive"))
      (node (ref "C104") (pin "1") (pinfunction "1_1") (pintype "passive"))
      (node (ref "C64") (pin "1") (pinfunction "1_1") (pintype "passive"))
      (node (ref "C67") (pin "1") (pinfunction "1_1") (pintype "passive"))
      (node (ref "C68") (pin "1") (pinfunction "1_1") (pintype "passive"))
      (node (ref "C69") (pin "1") (pinfunction "1_1") (pintype "passive"))
      (node (ref "C70") (pin "1") (pinfunction "1_1") (pintype "passive"))
      (node (ref "C71") (pin "1") (pinfunction "1_1") (pintype "passive"))
      (node (ref "C72") (pin "1") (pinfunction "1_1") (pintype "passive"))
      (node (ref "C73") (pin "1") (pinfunction "1_1") (pintype "passive"))
      (node (ref "C99") (pin "1") (pinfunction "1_1") (pintype "passive"))
      (node (ref "IC15") (pin "1") (pinfunction "IOVDD_1") (pintype "bidirectional"))
      (node (ref "IC15") (pin "10") (pinfunction "IOVDD_10") (pintype "bidirectional"))
      (node (ref "IC15") (pin "22") (pinfunction "IOVDD_22") (pintype "bidirectional"))
      (node (ref "IC15") (pin "33") (pinfunction "IOVDD_33") (pintype "bidirectional"))
      (node (ref "IC15") (pin "42") (pinfunction "IOVDD_42") (pintype "bidirectional"))
      (node (ref "IC15") (pin "44") (pinfunction "VREG_VIN_44") (pintype "bidirectional"))
      (node (ref "IC15") (pin "48") (pinfunction "USB_VDD_48") (pintype "bidirectional"))
      (node (ref "IC15") (pin "49") (pinfunction "IOVDD_49") (pintype "bidirectional"))
      (node (ref "IC18") (pin "8") (pinfunction "VCC_8") (pintype "power_in"))
      (node (ref "IC19") (pin "8") (pinfunction "VCC_8") (pintype "power_in"))
      (node (ref "IC21") (pin "5") (pinfunction "VOUT_5") (pintype "bidirectional"))
      (node (ref "IOVDD") (pin "TP") (pinfunction "P$1_TP") (pintype "bidirectional"))
      (node (ref "PWR") (pin "A") (pinfunction "A_A") (pintype "passive"))
      (node (ref "R109") (pin "2") (pinfunction "2_2") (pintype "passive"))
      (node (ref "R111") (pin "2") (pinfunction "2_2") (pintype "passive"))
      (node (ref "R128") (pin "2") (pinfunction "2_2") (pintype "passive"))
      (node (ref "R130") (pin "A2") (pinfunction "8_A2") (pintype "passive"))
      (node (ref "R130") (pin "B2") (pinfunction "7_B2") (pintype "passive"))
      (node (ref "R130") (pin "C2") (pinfunction "6_C2") (pintype "passive"))
      (node (ref "R130") (pin "D2") (pinfunction "5_D2") (pintype "passive"))
      (node (ref "R132") (pin "1") (pinfunction "1_1") (pintype "passive"))
      (node (ref "R152") (pin "1") (pinfunction "1_1") (pintype "passive"))
    )
    (net (code "5") (name "+5V") (class "Default")
      (node (ref "5VDC") (pin "TP") (pinfunction "P$1_TP") (pintype "bidirectional"))
      (node (ref "C11") (pin "1") (pinfunction "1_1") (pintype "passive"))
      (node (ref "C14") (pin "1") (pinfunction "1_1") (pintype "passive"))
      (node (ref "C17") (pin "1") (pinfunction "1_1") (pintype "passive"))
      (node (ref "D15") (pin "A") (pinfunction "A_A") (pintype "passive"))
      (node (ref "DSP") (pin "3") (pinfunction "3_3") (pintype "bidirectional"))
      (node (ref "DSP") (pin "4") (pinfunction "4_4") (pintype "bidirectional"))
      (node (ref "L1") (pin "2") (pinfunction "2_2") (pintype "passive"))
      (node (ref "R11") (pin "1") (pinfunction "1_1") (pintype "passive"))
      (node (ref "R148") (pin "1") (pinfunction "1_1") (pintype "passive"))
    )
    (net (code "6") (name "+5V_MEA") (class "Default")
      (node (ref "IC10") (pin "1") (pinfunction "VDD_1") (pintype "power_in"))
      (node (ref "IC11") (pin "1") (pinfunction "VDD_1") (pintype "power_in"))
      (node (ref "IC12") (pin "1") (pinfunction "VDD_1") (pintype "power_in"))
      (node (ref "IC14") (pin "1") (pinfunction "VDD_1") (pintype "power_in"))
      (node (ref "IC16") (pin "1") (pinfunction "VDD_1") (pintype "power_in"))
      (node (ref "IC6") (pin "1") (pinfunction "VDD_1") (pintype "power_in"))
      (node (ref "IC7") (pin "1") (pinfunction "VDD_1") (pintype "power_in"))
      (node (ref "IC8") (pin "1") (pinfunction "VDD_1") (pintype "power_in"))
      (node (ref "J2") (pin "2") (pinfunction "2_2") (pintype "passive"))
      (node (ref "J7") (pin "2") (pinfunction "2_2") (pintype "passive"))
      (node (ref "R63") (pin "A1") (pinfunction "1_A1") (pintype "passive"))
      (node (ref "R63") (pin "B1") (pinfunction "2_B1") (pintype "passive"))
      (node (ref "R63") (pin "C1") (pinfunction "3_C1") (pintype "passive"))
      (node (ref "R63") (pin "D1") (pinfunction "4_D1") (pintype "passive"))
      (node (ref "R64") (pin "A1") (pinfunction "1_A1") (pintype "passive"))
      (node (ref "R64") (pin "B1") (pinfunction "2_B1") (pintype "passive"))
      (node (ref "R64") (pin "C1") (pinfunction "3_C1") (pintype "passive"))
      (node (ref "R64") (pin "D1") (pinfunction "4_D1") (pintype "passive"))
    )
    (net (code "7") (name "+5V_MEA1") (class "Default")
      (node (ref "5V-NI1") (pin "TP") (pinfunction "P$1_TP") (pintype "bidirectional"))
      (node (ref "C23") (pin "1") (pinfunction "+_1") (pintype "passive"))
      (node (ref "C45") (pin "2") (pinfunction "2_2") (pintype "passive"))
      (node (ref "D9") (pin "A") (pinfunction "A_A") (pintype "passive"))
      (node (ref "J2") (pin "1") (pinfunction "1_1") (pintype "passive"))
      (node (ref "L3") (pin "2") (pinfunction "2_2") (pintype "passive"))
      (node (ref "R96") (pin "1") (pinfunction "1_1") (pintype "passive"))
    )
    (net (code "8") (name "+5V_MEA2") (class "Default")
      (node (ref "5V-NI2") (pin "TP") (pinfunction "P$1_TP") (pintype "bidirectional"))
      (node (ref "C53") (pin "1") (pinfunction "+_1") (pintype "passive"))
      (node (ref "C57") (pin "2") (pinfunction "2_2") (pintype "passive"))
      (node (ref "D13") (pin "A") (pinfunction "A_A") (pintype "passive"))
      (node (ref "J7") (pin "1") (pinfunction "1_1") (pintype "passive"))
      (node (ref "L5") (pin "2") (pinfunction "2_2") (pintype "passive"))
      (node (ref "R108") (pin "1") (pinfunction "1_1") (pintype "passive"))
    )
    (net (code "9") (name "+12V") (class "Default")
      (node (ref "C1") (pin "1") (pinfunction "1_1") (pintype "passive"))
      (node (ref "C2") (pin "1") (pinfunction "1_1") (pintype "passive"))
      (node (ref "C3") (pin "1") (pinfunction "1_1") (pintype "passive"))
      (node (ref "C4") (pin "1") (pinfunction "1_1") (pintype "passive"))
      (node (ref "D1") (pin "C") (pinfunction "C_C") (pintype "passive"))
      (node (ref "D2") (pin "C") (pinfunction "C_C") (pintype "passive"))
      (node (ref "D3") (pin "C") (pinfunction "C_C") (pintype "passive"))
      (node (ref "D4") (pin "C") (pinfunction "C_C") (pintype "passive"))
      (node (ref "D5") (pin "C") (pinfunction "C_C") (pintype "passive"))
      (node (ref "D6") (pin "C") (pinfunction "C_C") (pintype "passive"))
      (node (ref "D7") (pin "C") (pinfunction "C_C") (pintype "passive"))
      (node (ref "D8") (pin "C") (pinfunction "C_C") (pintype "passive"))
      (node (ref "IC1") (pin "2") (pinfunction "IN_2") (pintype "bidirectional"))
      (node (ref "IC2") (pin "2") (pinfunction "IN_2") (pintype "bidirectional"))
      (node (ref "IC3") (pin "10") (pinfunction "COM_10") (pintype "bidirectional"))
      (node (ref "J10") (pin "1") (pinfunction "1_1") (pintype "passive"))
      (node (ref "J8") (pin "1") (pinfunction "1_1") (pintype "passive"))
      (node (ref "J9") (pin "1") (pinfunction "1_1") (pintype "passive"))
      (node (ref "K1") (pin "8") (pinfunction "8_8") (pintype "passive"))
      (node (ref "K2") (pin "8") (pinfunction "8_8") (pintype "passive"))
      (node (ref "K3") (pin "8") (pinfunction "8_8") (pintype "passive"))
      (node (ref "K4") (pin "8") (pinfunction "8_8") (pintype "passive"))
      (node (ref "K5") (pin "8") (pinfunction "8_8") (pintype "passive"))
      (node (ref "K6") (pin "8") (pinfunction "8_8") (pintype "passive"))
      (node (ref "K7") (pin "8") (pinfunction "8_8") (pintype "passive"))
      (node (ref "K8") (pin "8") (pinfunction "8_8") (pintype "passive"))
      (node (ref "R150") (pin "1") (pinfunction "1_1") (pintype "passive"))
      (node (ref "R162") (pin "2") (pinfunction "2_2") (pintype "passive"))
      (node (ref "R94") (pin "2") (pinfunction "2_2") (pintype "passive"))
    )
    (net (code "10") (name "+12V_MEA") (class "Default")
      (node (ref "IC15") (pin "41") (pinfunction "GPIO29/ADC3_41") (pintype "bidirectional"))
      (node (ref "R94") (pin "1") (pinfunction "1_1") (pintype "passive"))
      (node (ref "R95") (pin "2") (pinfunction "2_2") (pintype "passive"))
    )
    (net (code "11") (name "5V_EN") (class "Default")
      (node (ref "IC1") (pin "6") (pinfunction "EN_6") (pintype "bidirectional"))
      (node (ref "R1") (pin "1") (pinfunction "1_1") (pintype "passive"))
      (node (ref "R161") (pin "2") (pinfunction "2_2") (pintype "passive"))
      (node (ref "R162") (pin "1") (pinfunction "1_1") (pintype "passive"))
    )
    (net (code "12") (name "AC_L") (class "Default")
      (node (ref "AC/DC1") (pin "AC_L") (pinfunction "AC/L_AC_L") (pintype "input"))
      (node (ref "AC/DC2") (pin "AC/L") (pinfunction "AC/L_AC/L") (pintype "input"))
      (node (ref "AC_L") (pin "B3,0") (pinfunction "MOUNT_B3,0") (pintype "passive"))
      (node (ref "K1") (pin "3") (pinfunction "3_3") (pintype "passive"))
      (node (ref "K1") (pin "6") (pinfunction "6_6") (pintype "passive"))
      (node (ref "K2") (pin "3") (pinfunction "3_3") (pintype "passive"))
      (node (ref "K2") (pin "6") (pinfunction "6_6") (pintype "passive"))
      (node (ref "K3") (pin "3") (pinfunction "3_3") (pintype "passive"))
      (node (ref "K3") (pin "6") (pinfunction "6_6") (pintype "passive"))
      (node (ref "K4") (pin "3") (pinfunction "3_3") (pintype "passive"))
      (node (ref "K4") (pin "6") (pinfunction "6_6") (pintype "passive"))
      (node (ref "K5") (pin "3") (pinfunction "3_3") (pintype "passive"))
      (node (ref "K5") (pin "6") (pinfunction "6_6") (pintype "passive"))
      (node (ref "K6") (pin "3") (pinfunction "3_3") (pintype "passive"))
      (node (ref "K6") (pin "6") (pinfunction "6_6") (pintype "passive"))
      (node (ref "K7") (pin "3") (pinfunction "3_3") (pintype "passive"))
      (node (ref "K7") (pin "6") (pinfunction "6_6") (pintype "passive"))
      (node (ref "K8") (pin "3") (pinfunction "3_3") (pintype "passive"))
      (node (ref "K8") (pin "6") (pinfunction "6_6") (pintype "passive"))
      (node (ref "R106") (pin "1") (pinfunction "1_1") (pintype "passive"))
      (node (ref "R62") (pin "1") (pinfunction "1_1") (pintype "passive"))
    )
    (net (code "13") (name "ADC_V_USB") (class "Default")
      (node (ref "IC15") (pin "38") (pinfunction "GPIO26/ADC0_38") (pintype "bidirectional"))
      (node (ref "R126") (pin "2") (pinfunction "2_2") (pintype "passive"))
      (node (ref "R127") (pin "1") (pinfunction "1_1") (pintype "passive"))
    )
    (net (code "14") (name "AGND") (class "Default")
      (node (ref "AC/DC1") (pin "AC_N") (pinfunction "AC/N_AC_N") (pintype "input"))
      (node (ref "AC/DC2") (pin "AC/N") (pinfunction "AC/N_AC/N") (pintype "input"))
      (node (ref "AC_N") (pin "B3,0") (pinfunction "MOUNT_B3,0") (pintype "passive"))
      (node (ref "C106") (pin "2") (pinfunction "2_2") (pintype "passive"))
      (node (ref "C107") (pin "2") (pinfunction "2_2") (pintype "passive"))
      (node (ref "C108") (pin "2") (pinfunction "2_2") (pintype "passive"))
      (node (ref "C109") (pin "2") (pinfunction "2_2") (pintype "passive"))
      (node (ref "C110") (pin "2") (pinfunction "2_2") (pintype "passive"))
      (node (ref "C111") (pin "2") (pinfunction "2_2") (pintype "passive"))
      (node (ref "C112") (pin "2") (pinfunction "2_2") (pintype "passive"))
      (node (ref "C113") (pin "2") (pinfunction "2_2") (pintype "passive"))
      (node (ref "C23") (pin "2") (pinfunction "-_2") (pintype "passive"))
      (node (ref "C24") (pin "2") (pinfunction "2_2") (pintype "passive"))
      (node (ref "C25") (pin "2") (pinfunction "2_2") (pintype "passive"))
      (node (ref "C26") (pin "2") (pinfunction "2_2") (pintype "passive"))
      (node (ref "C27") (pin "2") (pinfunction "2_2") (pintype "passive"))
      (node (ref "C28") (pin "2") (pinfunction "2_2") (pintype "passive"))
      (node (ref "C29") (pin "2") (pinfunction "2_2") (pintype "passive"))
      (node (ref "C30") (pin "2") (pinfunction "2_2") (pintype "passive"))
      (node (ref "C31") (pin "2") (pinfunction "2_2") (pintype "passive"))
      (node (ref "C32") (pin "2") (pinfunction "2_2") (pintype "passive"))
      (node (ref "C35") (pin "2") (pinfunction "-_2") (pintype "passive"))
      (node (ref "C36") (pin "2") (pinfunction "2_2") (pintype "passive"))
      (node (ref "C37") (pin "2") (pinfunction "2_2") (pintype "passive"))
      (node (ref "C38") (pin "2") (pinfunction "2_2") (pintype "passive"))
      (node (ref "C39") (pin "2") (pinfunction "2_2") (pintype "passive"))
      (node (ref "C40") (pin "2") (pinfunction "2_2") (pintype "passive"))
      (node (ref "C41") (pin "2") (pinfunction "2_2") (pintype "passive"))
      (node (ref "C42") (pin "2") (pinfunction "2_2") (pintype "passive"))
      (node (ref "C43") (pin "2") (pinfunction "2_2") (pintype "passive"))
      (node (ref "C44") (pin "2") (pinfunction "2_2") (pintype "passive"))
      (node (ref "C45") (pin "1") (pinfunction "1_1") (pintype "passive"))
      (node (ref "C47") (pin "2") (pinfunction "-_2") (pintype "passive"))
      (node (ref "C48") (pin "2") (pinfunction "2_2") (pintype "passive"))
      (node (ref "C49") (pin "2") (pinfunction "2_2") (pintype "passive"))
      (node (ref "C50") (pin "2") (pinfunction "2_2") (pintype "passive"))
      (node (ref "C53") (pin "2") (pinfunction "-_2") (pintype "passive"))
      (node (ref "C54") (pin "2") (pinfunction "2_2") (pintype "passive"))
      (node (ref "C55") (pin "2") (pinfunction "2_2") (pintype "passive"))
      (node (ref "C56") (pin "2") (pinfunction "2_2") (pintype "passive"))
      (node (ref "C57") (pin "1") (pinfunction "1_1") (pintype "passive"))
      (node (ref "D11") (pin "A") (pinfunction "A_A") (pintype "passive"))
      (node (ref "D14") (pin "A") (pinfunction "A_A") (pintype "passive"))
      (node (ref "IC10") (pin "5") (pinfunction "GND_5") (pintype "power_in"))
      (node (ref "IC11") (pin "5") (pinfunction "GND_5") (pintype "power_in"))
      (node (ref "IC12") (pin "5") (pinfunction "GND_5") (pintype "power_in"))
      (node (ref "IC14") (pin "5") (pinfunction "GND_5") (pintype "power_in"))
      (node (ref "IC16") (pin "5") (pinfunction "GND_5") (pintype "power_in"))
      (node (ref "IC6") (pin "5") (pinfunction "GND_5") (pintype "power_in"))
      (node (ref "IC7") (pin "5") (pinfunction "GND_5") (pintype "power_in"))
      (node (ref "IC8") (pin "5") (pinfunction "GND_5") (pintype "power_in"))
      (node (ref "R104") (pin "2") (pinfunction "2_2") (pintype "passive"))
      (node (ref "R108") (pin "2") (pinfunction "2_2") (pintype "passive"))
      (node (ref "R113") (pin "1") (pinfunction "1_1") (pintype "passive"))
      (node (ref "R115") (pin "2") (pinfunction "2_2") (pintype "passive"))
      (node (ref "R120") (pin "2") (pinfunction "2_2") (pintype "passive"))
      (node (ref "R25") (pin "2") (pinfunction "2_2") (pintype "passive"))
      (node (ref "R26") (pin "2") (pinfunction "2_2") (pintype "passive"))
      (node (ref "R27") (pin "2") (pinfunction "2_2") (pintype "passive"))
      (node (ref "R28") (pin "2") (pinfunction "2_2") (pintype "passive"))
      (node (ref "R29") (pin "2") (pinfunction "2_2") (pintype "passive"))
      (node (ref "R30") (pin "2") (pinfunction "2_2") (pintype "passive"))
      (node (ref "R31") (pin "2") (pinfunction "2_2") (pintype "passive"))
      (node (ref "R32") (pin "2") (pinfunction "2_2") (pintype "passive"))
      (node (ref "R33") (pin "1") (pinfunction "1_1") (pintype "passive"))
      (node (ref "R35") (pin "2") (pinfunction "2_2") (pintype "passive"))
      (node (ref "R40") (pin "2") (pinfunction "2_2") (pintype "passive"))
      (node (ref "R41") (pin "1") (pinfunction "1_1") (pintype "passive"))
      (node (ref "R43") (pin "2") (pinfunction "2_2") (pintype "passive"))
      (node (ref "R48") (pin "2") (pinfunction "2_2") (pintype "passive"))
      (node (ref "R49") (pin "1") (pinfunction "1_1") (pintype "passive"))
      (node (ref "R51") (pin "2") (pinfunction "2_2") (pintype "passive"))
      (node (ref "R56") (pin "2") (pinfunction "2_2") (pintype "passive"))
      (node (ref "R65") (pin "1") (pinfunction "1_1") (pintype "passive"))
      (node (ref "R67") (pin "2") (pinfunction "2_2") (pintype "passive"))
      (node (ref "R72") (pin "2") (pinfunction "2_2") (pintype "passive"))
      (node (ref "R73") (pin "1") (pinfunction "1_1") (pintype "passive"))
      (node (ref "R75") (pin "2") (pinfunction "2_2") (pintype "passive"))
      (node (ref "R80") (pin "2") (pinfunction "2_2") (pintype "passive"))
      (node (ref "R81") (pin "1") (pinfunction "1_1") (pintype "passive"))
      (node (ref "R83") (pin "2") (pinfunction "2_2") (pintype "passive"))
      (node (ref "R88") (pin "2") (pinfunction "2_2") (pintype "passive"))
      (node (ref "R96") (pin "2") (pinfunction "2_2") (pintype "passive"))
      (node (ref "R97") (pin "1") (pinfunction "1_1") (pintype "passive"))
      (node (ref "R99") (pin "2") (pinfunction "2_2") (pintype "passive"))
    )
    (net (code "15") (name "AVDD") (class "Default")
      (node (ref "AVDD") (pin "TP") (pinfunction "P$1_TP") (pintype "bidirectional"))
      (node (ref "C62") (pin "1") (pinfunction "1_1") (pintype "passive"))
      (node (ref "C74") (pin "1") (pinfunction "1_1") (pintype "passive"))
      (node (ref "IC15") (pin "43") (pinfunction "ADC_AVDD_43") (pintype "bidirectional"))
      (node (ref "IC17") (pin "1") (pinfunction "OUT_1") (pintype "output"))
      (node (ref "IC17") (pin "4") (pinfunction "-IN_4") (pintype "input"))
    )
    (net (code "16") (name "BUCK_EN") (class "Default")
      (node (ref "IC15") (pin "37") (pinfunction "GPIO25_37") (pintype "bidirectional"))
      (node (ref "IC2") (pin "6") (pinfunction "EN_6") (pintype "bidirectional"))
      (node (ref "R1") (pin "2") (pinfunction "2_2") (pintype "passive"))
      (node (ref "R2") (pin "2") (pinfunction "2_2") (pintype "passive"))
    )
    (net (code "17") (name "CC1") (class "Default")
      (node (ref "R125") (pin "1") (pinfunction "1_1") (pintype "passive"))
      (node (ref "USB1") (pin "A5") (pinfunction "CC1_A5") (pintype "bidirectional"))
    )
    (net (code "18") (name "CC2") (class "Default")
      (node (ref "R124") (pin "1") (pinfunction "1_1") (pintype "passive"))
      (node (ref "USB1") (pin "B5") (pinfunction "CC2_B5") (pintype "bidirectional"))
    )
    (net (code "19") (name "FB1") (class "Default")
      (node (ref "C5") (pin "2") (pinfunction "2_2") (pintype "passive"))
      (node (ref "FB-NI1") (pin "TP") (pinfunction "P$1_TP") (pintype "bidirectional"))
      (node (ref "IC13") (pin "2") (pinfunction "FB_2") (pintype "input"))
      (node (ref "R60") (pin "1") (pinfunction "1_1") (pintype "passive"))
      (node (ref "R61") (pin "2") (pinfunction "2_2") (pintype "passive"))
    )
    (net (code "20") (name "FB2") (class "Default")
      (node (ref "C51") (pin "2") (pinfunction "2_2") (pintype "passive"))
      (node (ref "FB-NI2") (pin "TP") (pinfunction "P$1_TP") (pintype "bidirectional"))
      (node (ref "IC5") (pin "2") (pinfunction "FB_2") (pintype "input"))
      (node (ref "R105") (pin "2") (pinfunction "2_2") (pintype "passive"))
      (node (ref "R107") (pin "1") (pinfunction "1_1") (pintype "passive"))
    )
    (net (code "21") (name "FBIN1") (class "Default")
      (node (ref "C22") (pin "2") (pinfunction "2_2") (pintype "passive"))
      (node (ref "D9") (pin "C") (pinfunction "C_C") (pintype "passive"))
      (node (ref "R61") (pin "1") (pinfunction "1_1") (pintype "passive"))
    )
    (net (code "22") (name "FBIN2") (class "Default")
      (node (ref "C52") (pin "2") (pinfunction "2_2") (pintype "passive"))
      (node (ref "D13") (pin "C") (pinfunction "C_C") (pintype "passive"))
      (node (ref "R105") (pin "1") (pinfunction "1_1") (pintype "passive"))
    )
    (net (code "23") (name "GND") (class "Default")
      (node (ref "AC/DC1") (pin "-V") (pinfunction "-V_-V") (pintype "output"))
      (node (ref "AC/DC2") (pin "-V") (pinfunction "-V_-V") (pintype "output"))
      (node (ref "BOOT") (pin "2") (pinfunction "P$2_2") (pintype "bidirectional"))
      (node (ref "C1") (pin "2") (pinfunction "2_2") (pintype "passive"))
      (node (ref "C10") (pin "2") (pinfunction "-_2") (pintype "passive"))
      (node (ref "C100") (pin "2") (pinfunction "2_2") (pintype "passive"))
      (node (ref "C101") (pin "2") (pinfunction "2_2") (pintype "passive"))
      (node (ref "C102") (pin "2") (pinfunction "2_2") (pintype "passive"))
      (node (ref "C103") (pin "2") (pinfunction "2_2") (pintype "passive"))
      (node (ref "C104") (pin "2") (pinfunction "2_2") (pintype "passive"))
      (node (ref "C13") (pin "2") (pinfunction "-_2") (pintype "passive"))
      (node (ref "C14") (pin "2") (pinfunction "2_2") (pintype "passive"))
      (node (ref "C15") (pin "2") (pinfunction "2_2") (pintype "passive"))
      (node (ref "C16") (pin "2") (pinfunction "-_2") (pintype "passive"))
      (node (ref "C17") (pin "2") (pinfunction "2_2") (pintype "passive"))
      (node (ref "C18") (pin "2") (pinfunction "2_2") (pintype "passive"))
      (node (ref "C19") (pin "2") (pinfunction "2_2") (pintype "passive"))
      (node (ref "C2") (pin "2") (pinfunction "2_2") (pintype "passive"))
      (node (ref "C20") (pin "2") (pinfunction "2_2") (pintype "passive"))
      (node (ref "C3") (pin "2") (pinfunction "2_2") (pintype "passive"))
      (node (ref "C33") (pin "2") (pinfunction "2_2") (pintype "passive"))
      (node (ref "C34") (pin "2") (pinfunction "2_2") (pintype "passive"))
      (node (ref "C4") (pin "2") (pinfunction "2_2") (pintype "passive"))
      (node (ref "C58") (pin "2") (pinfunction "2_2") (pintype "passive"))
      (node (ref "C59") (pin "2") (pinfunction "2_2") (pintype "passive"))
      (node (ref "C6") (pin "2") (pinfunction "2_2") (pintype "passive"))
      (node (ref "C60") (pin "2") (pinfunction "2_2") (pintype "passive"))
      (node (ref "C61") (pin "2") (pinfunction "2_2") (pintype "passive"))
      (node (ref "C62") (pin "2") (pinfunction "2_2") (pintype "passive"))
      (node (ref "C63") (pin "2") (pinfunction "2_2") (pintype "passive"))
      (node (ref "C64") (pin "2") (pinfunction "2_2") (pintype "passive"))
      (node (ref "C65") (pin "2") (pinfunction "2_2") (pintype "passive"))
      (node (ref "C66") (pin "2") (pinfunction "2_2") (pintype "passive"))
      (node (ref "C67") (pin "2") (pinfunction "2_2") (pintype "passive"))
      (node (ref "C68") (pin "2") (pinfunction "2_2") (pintype "passive"))
      (node (ref "C69") (pin "2") (pinfunction "2_2") (pintype "passive"))
      (node (ref "C7") (pin "2") (pinfunction "2_2") (pintype "passive"))
      (node (ref "C70") (pin "2") (pinfunction "2_2") (pintype "passive"))
      (node (ref "C71") (pin "2") (pinfunction "2_2") (pintype "passive"))
      (node (ref "C72") (pin "2") (pinfunction "2_2") (pintype "passive"))
      (node (ref "C73") (pin "2") (pinfunction "2_2") (pintype "passive"))
      (node (ref "C74") (pin "2") (pinfunction "2_2") (pintype "passive"))
      (node (ref "C75") (pin "2") (pinfunction "2_2") (pintype "passive"))
      (node (ref "C76") (pin "2") (pinfunction "2_2") (pintype "passive"))
      (node (ref "C77") (pin "2") (pinfunction "2_2") (pintype "passive"))
      (node (ref "C78") (pin "2") (pinfunction "2_2") (pintype "passive"))
      (node (ref "C79") (pin "2") (pinfunction "2_2") (pintype "passive"))
      (node (ref "C80") (pin "2") (pinfunction "2_2") (pintype "passive"))
      (node (ref "C83") (pin "1") (pinfunction "1_1") (pintype "passive"))
      (node (ref "C84") (pin "2") (pinfunction "2_2") (pintype "passive"))
      (node (ref "C85") (pin "2") (pinfunction "2_2") (pintype "passive"))
      (node (ref "C86") (pin "2") (pinfunction "2_2") (pintype "passive"))
      (node (ref "C87") (pin "2") (pinfunction "2_2") (pintype "passive"))
      (node (ref "C88") (pin "2") (pinfunction "2_2") (pintype "passive"))
      (node (ref "C89") (pin "2") (pinfunction "2_2") (pintype "passive"))
      (node (ref "C90") (pin "2") (pinfunction "2_2") (pintype "passive"))
      (node (ref "C91") (pin "2") (pinfunction "2_2") (pintype "passive"))
      (node (ref "C92") (pin "2") (pinfunction "2_2") (pintype "passive"))
      (node (ref "C93") (pin "2") (pinfunction "2_2") (pintype "passive"))
      (node (ref "C94") (pin "2") (pinfunction "2_2") (pintype "passive"))
      (node (ref "C95") (pin "2") (pinfunction "2_2") (pintype "passive"))
      (node (ref "C96") (pin "2") (pinfunction "2_2") (pintype "passive"))
      (node (ref "C97") (pin "2") (pinfunction "2_2") (pintype "passive"))
      (node (ref "C98") (pin "2") (pinfunction "2_2") (pintype "passive"))
      (node (ref "C99") (pin "2") (pinfunction "2_2") (pintype "passive"))
      (node (ref "D16") (pin "A") (pinfunction "A_A") (pintype "passive"))
      (node (ref "DAT") (pin "C") (pinfunction "C_C") (pintype "passive"))
      (node (ref "DSP") (pin "5") (pinfunction "5_5") (pintype "bidirectional"))
      (node (ref "DSP") (pin "8") (pinfunction "8_8") (pintype "bidirectional"))
      (node (ref "DSP") (pin "Z0") (pinfunction "Z1_Z0") (pintype "bidirectional"))
      (node (ref "DSP") (pin "Z1") (pinfunction "Z1_Z1") (pintype "bidirectional"))
      (node (ref "DSP") (pin "Z2") (pinfunction "Z2_Z2") (pintype "bidirectional"))
      (node (ref "DSP") (pin "Z3") (pinfunction "Z3_Z3") (pintype "bidirectional"))
      (node (ref "DSP") (pin "Z4") (pinfunction "Z3_Z4") (pintype "bidirectional"))
      (node (ref "DSP") (pin "Z5") (pinfunction "Z4_Z5") (pintype "bidirectional"))
      (node (ref "ESD1") (pin "1") (pinfunction "A_1") (pintype "bidirectional"))
      (node (ref "ETH1") (pin "8") (pinfunction "GND_8") (pintype "power_in"))
      (node (ref "GDGC") (pin "4") (pinfunction "P$4_4") (pintype "bidirectional"))
      (node (ref "GND") (pin "TP") (pinfunction "P$1_TP") (pintype "bidirectional"))
      (node (ref "GND-3") (pin "TP") (pinfunction "P$1_TP") (pintype "bidirectional"))
      (node (ref "GND-5") (pin "TP") (pinfunction "P$1_TP") (pintype "bidirectional"))
      (node (ref "IC1") (pin "4") (pinfunction "GND_4") (pintype "bidirectional"))
      (node (ref "IC15") (pin "19") (pinfunction "TESTEN_19") (pintype "bidirectional"))
      (node (ref "IC15") (pin "PAD") (pinfunction "GND_PAD") (pintype "bidirectional"))
      (node (ref "IC17") (pin "5") (pinfunction "V-_5") (pintype "power_in"))
      (node (ref "IC18") (pin "4") (pinfunction "GND_4") (pintype "power_in"))
      (node (ref "IC18") (pin "PAD") (pinfunction "GND_PAD") (pintype "power_in"))
      (node (ref "IC19") (pin "2") (pinfunction "A1_2") (pintype "bidirectional"))
      (node (ref "IC19") (pin "3") (pinfunction "A2_3") (pintype "bidirectional"))
      (node (ref "IC19") (pin "4") (pinfunction "GND_4") (pintype "power_in"))
      (node (ref "IC19") (pin "7") (pinfunction "WP_7") (pintype "bidirectional"))
      (node (ref "IC19") (pin "9") (pinfunction "GND_9") (pintype "power_in"))
      (node (ref "IC2") (pin "4") (pinfunction "GND_4") (pintype "bidirectional"))
      (node (ref "IC20") (pin "14") (pinfunction "AGND_14") (pintype "power_in"))
      (node (ref "IC20") (pin "16") (pinfunction "AGND_16") (pintype "power_in"))
      (node (ref "IC20") (pin "19") (pinfunction "AGND_19") (pintype "power_in"))
      (node (ref "IC20") (pin "29") (pinfunction "GND_29") (pintype "passive"))
      (node (ref "IC20") (pin "3") (pinfunction "AGND_3") (pintype "power_in"))
      (node (ref "IC20") (pin "48") (pinfunction "AGND_48") (pintype "power_in"))
      (node (ref "IC20") (pin "9") (pinfunction "AGND_9") (pintype "power_in"))
      (node (ref "IC21") (pin "2") (pinfunction "GND_2") (pintype "bidirectional"))
      (node (ref "IC22") (pin "5") (pinfunction "V-_5") (pintype "power_in"))
      (node (ref "IC3") (pin "9") (pinfunction "GND_9") (pintype "bidirectional"))
      (node (ref "IC4") (pin "11") (pinfunction "A0_11") (pintype "bidirectional"))
      (node (ref "IC4") (pin "12") (pinfunction "A1_12") (pintype "bidirectional"))
      (node (ref "IC4") (pin "13") (pinfunction "A2_13") (pintype "bidirectional"))
      (node (ref "IC4") (pin "6") (pinfunction "VSS_6") (pintype "bidirectional"))
      (node (ref "IC4") (pin "PAD") (pinfunction "VSS_PAD") (pintype "bidirectional"))
      (node (ref "IC9") (pin "8") (pinfunction "GND_8") (pintype "power_in"))
      (node (ref "OPT1") (pin "11") (pinfunction "11_11") (pintype "passive"))
      (node (ref "OPT1") (pin "13") (pinfunction "13_13") (pintype "passive"))
      (node (ref "OPT1") (pin "15") (pinfunction "15_15") (pintype "passive"))
      (node (ref "OPT1") (pin "9") (pinfunction "9_9") (pintype "passive"))
      (node (ref "OPT2") (pin "11") (pinfunction "11_11") (pintype "passive"))
      (node (ref "OPT2") (pin "13") (pinfunction "13_13") (pintype "passive"))
      (node (ref "OPT2") (pin "15") (pinfunction "15_15") (pintype "passive"))
      (node (ref "OPT2") (pin "9") (pinfunction "9_9") (pintype "passive"))
      (node (ref "P12ON") (pin "C") (pinfunction "C_C") (pintype "passive"))
      (node (ref "P3ON") (pin "C") (pinfunction "C_C") (pintype "passive"))
      (node (ref "P5ON") (pin "C") (pinfunction "C_C") (pintype "passive"))
      (node (ref "PROC") (pin "C") (pinfunction "C_C") (pintype "passive"))
      (node (ref "R110") (pin "1") (pinfunction "1_1") (pintype "passive"))
      (node (ref "R12") (pin "2") (pinfunction "2_2") (pintype "passive"))
      (node (ref "R121") (pin "2") (pinfunction "2_2") (pintype "passive"))
      (node (ref "R124") (pin "2") (pinfunction "2_2") (pintype "passive"))
      (node (ref "R125") (pin "2") (pinfunction "2_2") (pintype "passive"))
      (node (ref "R127") (pin "2") (pinfunction "2_2") (pintype "passive"))
      (node (ref "R129") (pin "1") (pinfunction "1_1") (pintype "passive"))
      (node (ref "R131") (pin "2") (pinfunction "2_2") (pintype "passive"))
      (node (ref "R14") (pin "2") (pinfunction "2_2") (pintype "passive"))
      (node (ref "R143") (pin "1") (pinfunction "1_1") (pintype "passive"))
      (node (ref "R151") (pin "1") (pinfunction "1_1") (pintype "passive"))
      (node (ref "R161") (pin "1") (pinfunction "1_1") (pintype "passive"))
      (node (ref "R2") (pin "1") (pinfunction "1_1") (pintype "passive"))
      (node (ref "R4") (pin "2") (pinfunction "2_2") (pintype "passive"))
      (node (ref "R6") (pin "2") (pinfunction "2_2") (pintype "passive"))
      (node (ref "R93") (pin "5") (pinfunction "5_5") (pintype "passive"))
      (node (ref "R93") (pin "6") (pinfunction "6_6") (pintype "passive"))
      (node (ref "R93") (pin "7") (pinfunction "7_7") (pintype "passive"))
      (node (ref "R93") (pin "8") (pinfunction "8_8") (pintype "passive"))
      (node (ref "R95") (pin "1") (pinfunction "1_1") (pintype "passive"))
      (node (ref "REF1") (pin "2") (pinfunction "A_2") (pintype "passive"))
      (node (ref "REF1") (pin "3") (pinfunction "A_3") (pintype "passive"))
      (node (ref "RESET") (pin "1") (pinfunction "P$1_1") (pintype "bidirectional"))
      (node (ref "RGTG") (pin "2") (pinfunction "P$2_2") (pintype "bidirectional"))
      (node (ref "RGTG") (pin "4") (pinfunction "P$4_4") (pintype "bidirectional"))
      (node (ref "USB1") (pin "GND") (pinfunction "GND_GND") (pintype "power_in"))
      (node (ref "USB1") (pin "GND2") (pinfunction "GND_GND2") (pintype "power_in"))
      (node (ref "X1") (pin "2") (pinfunction "GND_2") (pintype "passive"))
      (node (ref "X1") (pin "4") (pinfunction "GND_4") (pintype "passive"))
      (node (ref "X2") (pin "2") (pinfunction "GND_2") (pintype "passive"))
      (node (ref "X2") (pin "4") (pinfunction "GND_4") (pintype "passive"))
    )
    (net (code "24") (name "I2C0_SCL") (class "Default")
      (node (ref "DSP") (pin "7") (pinfunction "7_7") (pintype "bidirectional"))
      (node (ref "IC15") (pin "7") (pinfunction "GPIO5_7") (pintype "bidirectional"))
      (node (ref "R130") (pin "A1") (pinfunction "1_A1") (pintype "passive"))
    )
    (net (code "25") (name "I2C0_SDA") (class "Default")
      (node (ref "DSP") (pin "6") (pinfunction "6_6") (pintype "bidirectional"))
      (node (ref "IC15") (pin "6") (pinfunction "GPIO4_6") (pintype "bidirectional"))
      (node (ref "R130") (pin "B1") (pinfunction "2_B1") (pintype "passive"))
    )
    (net (code "26") (name "I2C1_SCL") (class "Default")
      (node (ref "IC15") (pin "5") (pinfunction "GPIO3_5") (pintype "bidirectional"))
      (node (ref "IC19") (pin "6") (pinfunction "SCL_6") (pintype "bidirectional"))
      (node (ref "IC4") (pin "8") (pinfunction "SCL_8") (pintype "bidirectional"))
      (node (ref "R130") (pin "C1") (pinfunction "3_C1") (pintype "passive"))
    )
    (net (code "27") (name "I2C1_SDA") (class "Default")
      (node (ref "IC15") (pin "4") (pinfunction "GPIO2_4") (pintype "bidirectional"))
      (node (ref "IC19") (pin "5") (pinfunction "SDA_5") (pintype "bidirectional"))
      (node (ref "IC4") (pin "9") (pinfunction "SDA_9") (pintype "bidirectional"))
      (node (ref "R130") (pin "D1") (pinfunction "4_D1") (pintype "passive"))
    )
    (net (code "28") (name "KEY_0") (class "Default")
      (node (ref "DSP") (pin "12") (pinfunction "12_12") (pintype "bidirectional"))
      (node (ref "IC15") (pin "15") (pinfunction "GPIO12_15") (pintype "bidirectional"))
    )
    (net (code "29") (name "KEY_1") (class "Default")
      (node (ref "DSP") (pin "11") (pinfunction "11_11") (pintype "bidirectional"))
      (node (ref "IC15") (pin "16") (pinfunction "GPIO13_16") (pintype "bidirectional"))
    )
    (net (code "30") (name "KEY_2") (class "Default")
      (node (ref "DSP") (pin "10") (pinfunction "10_10") (pintype "bidirectional"))
      (node (ref "IC15") (pin "17") (pinfunction "GPIO14_17") (pintype "bidirectional"))
    )
    (net (code "31") (name "KEY_3") (class "Default")
      (node (ref "DSP") (pin "9") (pinfunction "9_9") (pintype "bidirectional"))
      (node (ref "IC15") (pin "18") (pinfunction "GPIO15_18") (pintype "bidirectional"))
    )
    (net (code "32") (name "LCD_BL") (class "Default")
      (node (ref "DSP") (pin "13") (pinfunction "13_13") (pintype "bidirectional"))
      (node (ref "IC15") (pin "9") (pinfunction "GPIO7_9") (pintype "bidirectional"))
    )
    (net (code "33") (name "LCD_CS") (class "Default")
      (node (ref "DSP") (pin "19") (pinfunction "19_19") (pintype "bidirectional"))
      (node (ref "IC15") (pin "12") (pinfunction "GPIO9_12") (pintype "bidirectional"))
      (node (ref "R149") (pin "C2") (pinfunction "6_C2") (pintype "passive"))
    )
    (net (code "34") (name "LCD_DC") (class "Default")
      (node (ref "DSP") (pin "18") (pinfunction "18_18") (pintype "bidirectional"))
      (node (ref "IC15") (pin "8") (pinfunction "GPIO6_8") (pintype "bidirectional"))
    )
    (net (code "35") (name "LCD_MISO") (class "Default")
      (node (ref "DSP") (pin "15") (pinfunction "15_15") (pintype "bidirectional"))
      (node (ref "IC15") (pin "11") (pinfunction "GPIO8_11") (pintype "bidirectional"))
      (node (ref "R149") (pin "B2") (pinfunction "7_B2") (pintype "passive"))
    )
    (net (code "36") (name "LCD_MOSI") (class "Default")
      (node (ref "DSP") (pin "16") (pinfunction "16_16") (pintype "bidirectional"))
      (node (ref "IC15") (pin "14") (pinfunction "GPIO11_14") (pintype "bidirectional"))
    )
    (net (code "37") (name "LCD_RES") (class "Default")
      (node (ref "DSP") (pin "14") (pinfunction "14_14") (pintype "bidirectional"))
      (node (ref "IC15") (pin "34") (pinfunction "GPIO22_34") (pintype "bidirectional"))
      (node (ref "R149") (pin "A2") (pinfunction "8_A2") (pintype "passive"))
    )
    (net (code "38") (name "LCD_SCLK") (class "Default")
      (node (ref "DSP") (pin "17") (pinfunction "17_17") (pintype "bidirectional"))
      (node (ref "IC15") (pin "13") (pinfunction "GPIO10_13") (pintype "bidirectional"))
    )
    (net (code "39") (name "LREC1") (class "Default")
      (node (ref "C35") (pin "1") (pinfunction "+_1") (pintype "passive"))
      (node (ref "D10") (pin "C") (pinfunction "C_C") (pintype "passive"))
      (node (ref "IC13") (pin "5") (pinfunction "DRAIN_5") (pintype "input"))
      (node (ref "L-REC1") (pin "TP") (pinfunction "P$1_TP") (pintype "bidirectional"))
    )
    (net (code "40") (name "LREC2") (class "Default")
      (node (ref "C47") (pin "1") (pinfunction "+_1") (pintype "passive"))
      (node (ref "D12") (pin "C") (pinfunction "C_C") (pintype "passive"))
      (node (ref "IC5") (pin "5") (pinfunction "DRAIN_5") (pintype "input"))
      (node (ref "L-REC2") (pin "TP") (pinfunction "P$1_TP") (pintype "bidirectional"))
    )
    (net (code "41") (name "MCP_DSP_RST") (class "Default")
      (node (ref "DSP") (pin "20") (pinfunction "20_20") (pintype "bidirectional"))
      (node (ref "IC15") (pin "36") (pinfunction "GPIO24_36") (pintype "bidirectional"))
      (node (ref "R147") (pin "1") (pinfunction "1_1") (pintype "passive"))
    )
    (net (code "42") (name "MCP_REL_RST") (class "Default")
      (node (ref "IC15") (pin "35") (pinfunction "GPIO23_35") (pintype "bidirectional"))
      (node (ref "IC4") (pin "14") (pinfunction "~{RESET}_14") (pintype "bidirectional"))
    )
    (net (code "43") (name "MCP_VIN") (class "Default")
      (node (ref "C102") (pin "1") (pinfunction "1_1") (pintype "passive"))
      (node (ref "C63") (pin "1") (pinfunction "1_1") (pintype "passive"))
      (node (ref "IC17") (pin "2") (pinfunction "V+_2") (pintype "power_in"))
      (node (ref "R152") (pin "2") (pinfunction "2_2") (pintype "passive"))
    )
    (net (code "44") (name "MUX_A") (class "Default")
      (node (ref "IC4") (pin "25") (pinfunction "IO2.0_25") (pintype "bidirectional"))
      (node (ref "IC9") (pin "11") (pinfunction "A_11") (pintype "input"))
      (node (ref "R93") (pin "4") (pinfunction "4_4") (pintype "passive"))
    )
    (net (code "45") (name "MUX_B") (class "Default")
      (node (ref "IC4") (pin "26") (pinfunction "IO2.1_26") (pintype "bidirectional"))
      (node (ref "IC9") (pin "10") (pinfunction "B_10") (pintype "input"))
      (node (ref "R93") (pin "3") (pinfunction "3_3") (pintype "passive"))
    )
    (net (code "46") (name "MUX_C") (class "Default")
      (node (ref "IC4") (pin "27") (pinfunction "IO2.2_27") (pintype "bidirectional"))
      (node (ref "IC9") (pin "9") (pinfunction "C_9") (pintype "input"))
      (node (ref "R93") (pin "2") (pinfunction "2_2") (pintype "passive"))
    )
    (net (code "47") (name "MUX_EN") (class "Default")
      (node (ref "IC4") (pin "28") (pinfunction "IO2.3_28") (pintype "bidirectional"))
      (node (ref "IC9") (pin "7") (pinfunction "~{EN}_7") (pintype "input"))
      (node (ref "R93") (pin "1") (pinfunction "1_1") (pintype "passive"))
    )
    (net (code "48") (name "N_OUT1") (class "Default")
      (node (ref "N_OUT1") (pin "B2,8") (pinfunction "MOUNT_B2,8") (pintype "passive"))
      (node (ref "R25") (pin "1") (pinfunction "1_1") (pintype "passive"))
      (node (ref "R34") (pin "1") (pinfunction "1_1") (pintype "passive"))
      (node (ref "R35") (pin "1") (pinfunction "1_1") (pintype "passive"))
    )
    (net (code "49") (name "N_OUT2") (class "Default")
      (node (ref "N_OUT2") (pin "B2,8") (pinfunction "MOUNT_B2,8") (pintype "passive"))
      (node (ref "R32") (pin "1") (pinfunction "1_1") (pintype "passive"))
      (node (ref "R50") (pin "1") (pinfunction "1_1") (pintype "passive"))
      (node (ref "R51") (pin "1") (pinfunction "1_1") (pintype "passive"))
    )
    (net (code "50") (name "N_OUT3") (class "Default")
      (node (ref "N_OUT3") (pin "B2,8") (pinfunction "MOUNT_B2,8") (pintype "passive"))
      (node (ref "R31") (pin "1") (pinfunction "1_1") (pintype "passive"))
      (node (ref "R66") (pin "1") (pinfunction "1_1") (pintype "passive"))
      (node (ref "R67") (pin "1") (pinfunction "1_1") (pintype "passive"))
    )
    (net (code "51") (name "N_OUT4") (class "Default")
      (node (ref "N_OUT4") (pin "B2,8") (pinfunction "MOUNT_B2,8") (pintype "passive"))
      (node (ref "R30") (pin "1") (pinfunction "1_1") (pintype "passive"))
      (node (ref "R82") (pin "1") (pinfunction "1_1") (pintype "passive"))
      (node (ref "R83") (pin "1") (pinfunction "1_1") (pintype "passive"))
    )
    (net (code "52") (name "N_OUT5") (class "Default")
      (node (ref "N_OUT5") (pin "B2,8") (pinfunction "MOUNT_B2,8") (pintype "passive"))
      (node (ref "R26") (pin "1") (pinfunction "1_1") (pintype "passive"))
      (node (ref "R42") (pin "1") (pinfunction "1_1") (pintype "passive"))
      (node (ref "R43") (pin "1") (pinfunction "1_1") (pintype "passive"))
    )
    (net (code "53") (name "N_OUT6") (class "Default")
      (node (ref "N_OUT6") (pin "B2,8") (pinfunction "MOUNT_B2,8") (pintype "passive"))
      (node (ref "R27") (pin "1") (pinfunction "1_1") (pintype "passive"))
      (node (ref "R74") (pin "1") (pinfunction "1_1") (pintype "passive"))
      (node (ref "R75") (pin "1") (pinfunction "1_1") (pintype "passive"))
    )
    (net (code "54") (name "N_OUT7") (class "Default")
      (node (ref "N_OUT7") (pin "B2,8") (pinfunction "MOUNT_B2,8") (pintype "passive"))
      (node (ref "R28") (pin "1") (pinfunction "1_1") (pintype "passive"))
      (node (ref "R98") (pin "1") (pinfunction "1_1") (pintype "passive"))
      (node (ref "R99") (pin "1") (pinfunction "1_1") (pintype "passive"))
    )
    (net (code "55") (name "N_OUT8") (class "Default")
      (node (ref "N_OUT8") (pin "B2,8") (pinfunction "MOUNT_B2,8") (pintype "passive"))
      (node (ref "R114") (pin "1") (pinfunction "1_1") (pintype "passive"))
      (node (ref "R115") (pin "1") (pinfunction "1_1") (pintype "passive"))
      (node (ref "R29") (pin "1") (pinfunction "1_1") (pintype "passive"))
    )
    (net (code "56") (name "Net-(3VFB-P$1)") (class "Default")
      (node (ref "3VFB") (pin "TP") (pinfunction "P$1_TP") (pintype "bidirectional"))
      (node (ref "C12") (pin "2") (pinfunction "2_2") (pintype "passive"))
      (node (ref "R10") (pin "2") (pinfunction "2_2") (pintype "passive"))
      (node (ref "R13") (pin "2") (pinfunction "2_2") (pintype "passive"))
      (node (ref "R14") (pin "1") (pinfunction "1_1") (pintype "passive"))
    )
    (net (code "57") (name "Net-(5VFB-P$1)") (class "Default")
      (node (ref "5VFB") (pin "TP") (pinfunction "P$1_TP") (pintype "bidirectional"))
      (node (ref "C11") (pin "2") (pinfunction "2_2") (pintype "passive"))
      (node (ref "R11") (pin "2") (pinfunction "2_2") (pintype "passive"))
      (node (ref "R12") (pin "1") (pinfunction "1_1") (pintype "passive"))
      (node (ref "R8") (pin "2") (pinfunction "2_2") (pintype "passive"))
    )
    (net (code "58") (name "Net-(12VDC-P$1)") (class "Default")
      (node (ref "12VDC") (pin "TP") (pinfunction "P$1_TP") (pintype "bidirectional"))
      (node (ref "AC/DC1") (pin "+V") (pinfunction "+V_+V") (pintype "output"))
      (node (ref "AC/DC2") (pin "+V") (pinfunction "+V_+V") (pintype "output"))
      (node (ref "C10") (pin "1") (pinfunction "+_1") (pintype "passive"))
      (node (ref "C13") (pin "1") (pinfunction "+_1") (pintype "passive"))
      (node (ref "C16") (pin "1") (pinfunction "+_1") (pintype "passive"))
      (node (ref "D16") (pin "C") (pinfunction "C_C") (pintype "passive"))
      (node (ref "J10") (pin "2") (pinfunction "2_2") (pintype "passive"))
      (node (ref "J8") (pin "2") (pinfunction "2_2") (pintype "passive"))
      (node (ref "J9") (pin "2") (pinfunction "2_2") (pintype "passive"))
    )
    (net (code "59") (name "Net-(C8-Pad1)") (class "Default")
      (node (ref "C8") (pin "1") (pinfunction "1_1") (pintype "passive"))
      (node (ref "R7") (pin "1") (pinfunction "1_1") (pintype "passive"))
    )
    (net (code "60") (name "Net-(C9-Pad1)") (class "Default")
      (node (ref "C9") (pin "1") (pinfunction "1_1") (pintype "passive"))
      (node (ref "R9") (pin "1") (pinfunction "1_1") (pintype "passive"))
    )
    (net (code "61") (name "Net-(C106-Pad1)") (class "Default")
      (node (ref "C106") (pin "1") (pinfunction "1_1") (pintype "passive"))
      (node (ref "OPT1") (pin "2") (pinfunction "2_2") (pintype "passive"))
      (node (ref "R59") (pin "2") (pinfunction "2_2") (pintype "passive"))
    )
    (net (code "62") (name "Net-(C107-Pad1)") (class "Default")
      (node (ref "C107") (pin "1") (pinfunction "1_1") (pintype "passive"))
      (node (ref "OPT1") (pin "4") (pinfunction "4_4") (pintype "passive"))
      (node (ref "R153") (pin "2") (pinfunction "2_2") (pintype "passive"))
    )
    (net (code "63") (name "Net-(C108-Pad1)") (class "Default")
      (node (ref "C108") (pin "1") (pinfunction "1_1") (pintype "passive"))
      (node (ref "OPT1") (pin "6") (pinfunction "6_6") (pintype "passive"))
      (node (ref "R154") (pin "2") (pinfunction "2_2") (pintype "passive"))
    )
    (net (code "64") (name "Net-(C109-Pad1)") (class "Default")
      (node (ref "C109") (pin "1") (pinfunction "1_1") (pintype "passive"))
      (node (ref "OPT1") (pin "8") (pinfunction "8_8") (pintype "passive"))
      (node (ref "R155") (pin "2") (pinfunction "2_2") (pintype "passive"))
    )
    (net (code "65") (name "Net-(C110-Pad1)") (class "Default")
      (node (ref "C110") (pin "1") (pinfunction "1_1") (pintype "passive"))
      (node (ref "OPT2") (pin "2") (pinfunction "2_2") (pintype "passive"))
      (node (ref "R156") (pin "2") (pinfunction "2_2") (pintype "passive"))
    )
    (net (code "66") (name "Net-(C111-Pad1)") (class "Default")
      (node (ref "C111") (pin "1") (pinfunction "1_1") (pintype "passive"))
      (node (ref "OPT2") (pin "4") (pinfunction "4_4") (pintype "passive"))
      (node (ref "R157") (pin "2") (pinfunction "2_2") (pintype "passive"))
    )
    (net (code "67") (name "Net-(C112-Pad1)") (class "Default")
      (node (ref "C112") (pin "1") (pinfunction "1_1") (pintype "passive"))
      (node (ref "OPT2") (pin "6") (pinfunction "6_6") (pintype "passive"))
      (node (ref "R158") (pin "2") (pinfunction "2_2") (pintype "passive"))
    )
    (net (code "68") (name "Net-(C113-Pad1)") (class "Default")
      (node (ref "C113") (pin "1") (pinfunction "1_1") (pintype "passive"))
      (node (ref "OPT2") (pin "8") (pinfunction "8_8") (pintype "passive"))
      (node (ref "R159") (pin "2") (pinfunction "2_2") (pintype "passive"))
    )
    (net (code "69") (name "Net-(D10-PadA)") (class "Default")
      (node (ref "D10") (pin "A") (pinfunction "A_A") (pintype "passive"))
      (node (ref "R62") (pin "2") (pinfunction "2_2") (pintype "passive"))
    )
    (net (code "70") (name "Net-(D12-PadA)") (class "Default")
      (node (ref "D12") (pin "A") (pinfunction "A_A") (pintype "passive"))
      (node (ref "R106") (pin "2") (pinfunction "2_2") (pintype "passive"))
    )
    (net (code "71") (name "Net-(DAT-PadA)") (class "Default")
      (node (ref "DAT") (pin "A") (pinfunction "A_A") (pintype "passive"))
      (node (ref "R122") (pin "2") (pinfunction "2_2") (pintype "passive"))
    )
    (net (code "72") (name "Net-(ETH1-GREEN-)") (class "Default")
      (node (ref "ETH1") (pin "9") (pinfunction "GREEN-_9") (pintype "passive"))
      (node (ref "R142") (pin "2") (pinfunction "2_2") (pintype "passive"))
    )
    (net (code "73") (name "Net-(ETH1-YELLOW-)") (class "Default")
      (node (ref "ETH1") (pin "11") (pinfunction "YELLOW-_11") (pintype "passive"))
      (node (ref "R141") (pin "2") (pinfunction "2_2") (pintype "passive"))
    )
    (net (code "74") (name "Net-(IC1-AAM)") (class "Default")
      (node (ref "IC1") (pin "1") (pinfunction "AAM_1") (pintype "bidirectional"))
      (node (ref "R3") (pin "2") (pinfunction "2_2") (pintype "passive"))
      (node (ref "R4") (pin "1") (pinfunction "1_1") (pintype "passive"))
    )
    (net (code "75") (name "Net-(IC1-BST)") (class "Default")
      (node (ref "IC1") (pin "5") (pinfunction "BST_5") (pintype "bidirectional"))
      (node (ref "R7") (pin "2") (pinfunction "2_2") (pintype "passive"))
    )
    (net (code "76") (name "Net-(IC1-FB)") (class "Default")
      (node (ref "IC1") (pin "8") (pinfunction "FB_8") (pintype "bidirectional"))
      (node (ref "R8") (pin "1") (pinfunction "1_1") (pintype "passive"))
    )
    (net (code "77") (name "Net-(IC1-SW)") (class "Default")
      (node (ref "C8") (pin "2") (pinfunction "2_2") (pintype "passive"))
      (node (ref "IC1") (pin "3") (pinfunction "SW_3") (pintype "bidirectional"))
      (node (ref "L1") (pin "1") (pinfunction "1_1") (pintype "passive"))
      (node (ref "SW") (pin "TP") (pinfunction "P$1_TP") (pintype "bidirectional"))
    )
    (net (code "78") (name "Net-(IC1-VCC)") (class "Default")
      (node (ref "C6") (pin "1") (pinfunction "1_1") (pintype "passive"))
      (node (ref "IC1") (pin "7") (pinfunction "VCC_7") (pintype "bidirectional"))
      (node (ref "R3") (pin "1") (pinfunction "1_1") (pintype "passive"))
    )
    (net (code "79") (name "Net-(IC2-AAM)") (class "Default")
      (node (ref "IC2") (pin "1") (pinfunction "AAM_1") (pintype "bidirectional"))
      (node (ref "R5") (pin "2") (pinfunction "2_2") (pintype "passive"))
      (node (ref "R6") (pin "1") (pinfunction "1_1") (pintype "passive"))
    )
    (net (code "80") (name "Net-(IC2-BST)") (class "Default")
      (node (ref "IC2") (pin "5") (pinfunction "BST_5") (pintype "bidirectional"))
      (node (ref "R9") (pin "2") (pinfunction "2_2") (pintype "passive"))
    )
    (net (code "81") (name "Net-(IC2-FB)") (class "Default")
      (node (ref "IC2") (pin "8") (pinfunction "FB_8") (pintype "bidirectional"))
      (node (ref "R10") (pin "1") (pinfunction "1_1") (pintype "passive"))
    )
    (net (code "82") (name "Net-(IC2-SW)") (class "Default")
      (node (ref "C9") (pin "2") (pinfunction "2_2") (pintype "passive"))
      (node (ref "IC2") (pin "3") (pinfunction "SW_3") (pintype "bidirectional"))
      (node (ref "L2") (pin "1") (pinfunction "1_1") (pintype "passive"))
      (node (ref "SW3") (pin "TP") (pinfunction "P$1_TP") (pintype "bidirectional"))
    )
    (net (code "83") (name "Net-(IC2-VCC)") (class "Default")
      (node (ref "C7") (pin "1") (pinfunction "1_1") (pintype "passive"))
      (node (ref "IC2") (pin "7") (pinfunction "VCC_7") (pintype "bidirectional"))
      (node (ref "R5") (pin "1") (pinfunction "1_1") (pintype "passive"))
    )
    (net (code "84") (name "Net-(IC3-1C)") (class "Default")
      (node (ref "IC3") (pin "18") (pinfunction "1C_18") (pintype "bidirectional"))
      (node (ref "R17") (pin "1") (pinfunction "1_1") (pintype "passive"))
    )
    (net (code "85") (name "Net-(IC3-2C)") (class "Default")
      (node (ref "IC3") (pin "17") (pinfunction "2C_17") (pintype "bidirectional"))
      (node (ref "R18") (pin "1") (pinfunction "1_1") (pintype "passive"))
    )
    (net (code "86") (name "Net-(IC3-3C)") (class "Default")
      (node (ref "IC3") (pin "16") (pinfunction "3C_16") (pintype "bidirectional"))
      (node (ref "R19") (pin "1") (pinfunction "1_1") (pintype "passive"))
    )
    (net (code "87") (name "Net-(IC3-4C)") (class "Default")
      (node (ref "IC3") (pin "15") (pinfunction "4C_15") (pintype "bidirectional"))
      (node (ref "R20") (pin "1") (pinfunction "1_1") (pintype "passive"))
    )
    (net (code "88") (name "Net-(IC3-5C)") (class "Default")
      (node (ref "IC3") (pin "14") (pinfunction "5C_14") (pintype "bidirectional"))
      (node (ref "R21") (pin "1") (pinfunction "1_1") (pintype "passive"))
    )
    (net (code "89") (name "Net-(IC3-6C)") (class "Default")
      (node (ref "IC3") (pin "13") (pinfunction "6C_13") (pintype "bidirectional"))
      (node (ref "R22") (pin "1") (pinfunction "1_1") (pintype "passive"))
    )
    (net (code "90") (name "Net-(IC3-7C)") (class "Default")
      (node (ref "IC3") (pin "12") (pinfunction "7C_12") (pintype "bidirectional"))
      (node (ref "R23") (pin "1") (pinfunction "1_1") (pintype "passive"))
    )
    (net (code "91") (name "Net-(IC3-8C)") (class "Default")
      (node (ref "IC3") (pin "11") (pinfunction "8C_11") (pintype "bidirectional"))
      (node (ref "R24") (pin "1") (pinfunction "1_1") (pintype "passive"))
    )
    (net (code "92") (name "Net-(IC6-INN)") (class "Default")
      (node (ref "C25") (pin "1") (pinfunction "1_1") (pintype "passive"))
      (node (ref "IC6") (pin "3") (pinfunction "INN_3") (pintype "input"))
      (node (ref "R34") (pin "2") (pinfunction "2_2") (pintype "passive"))
    )
    (net (code "93") (name "Net-(IC6-INP)") (class "Default")
      (node (ref "C24") (pin "1") (pinfunction "1_1") (pintype "passive"))
      (node (ref "IC6") (pin "2") (pinfunction "INP_2") (pintype "input"))
      (node (ref "R33") (pin "2") (pinfunction "2_2") (pintype "passive"))
    )
    (net (code "94") (name "Net-(IC6-VP)") (class "Default")
      (node (ref "C26") (pin "1") (pinfunction "1_1") (pintype "passive"))
      (node (ref "IC6") (pin "4") (pinfunction "VP_4") (pintype "input"))
      (node (ref "R39") (pin "2") (pinfunction "2_2") (pintype "passive"))
      (node (ref "R40") (pin "1") (pinfunction "1_1") (pintype "passive"))
    )
    (net (code "95") (name "Net-(IC7-INN)") (class "Default")
      (node (ref "C28") (pin "1") (pinfunction "1_1") (pintype "passive"))
      (node (ref "IC7") (pin "3") (pinfunction "INN_3") (pintype "input"))
      (node (ref "R42") (pin "2") (pinfunction "2_2") (pintype "passive"))
    )
    (net (code "96") (name "Net-(IC7-INP)") (class "Default")
      (node (ref "C27") (pin "1") (pinfunction "1_1") (pintype "passive"))
      (node (ref "IC7") (pin "2") (pinfunction "INP_2") (pintype "input"))
      (node (ref "R41") (pin "2") (pinfunction "2_2") (pintype "passive"))
    )
    (net (code "97") (name "Net-(IC7-VP)") (class "Default")
      (node (ref "C29") (pin "1") (pinfunction "1_1") (pintype "passive"))
      (node (ref "IC7") (pin "4") (pinfunction "VP_4") (pintype "input"))
      (node (ref "R47") (pin "2") (pinfunction "2_2") (pintype "passive"))
      (node (ref "R48") (pin "1") (pinfunction "1_1") (pintype "passive"))
    )
    (net (code "98") (name "Net-(IC8-INN)") (class "Default")
      (node (ref "C31") (pin "1") (pinfunction "1_1") (pintype "passive"))
      (node (ref "IC8") (pin "3") (pinfunction "INN_3") (pintype "input"))
      (node (ref "R50") (pin "2") (pinfunction "2_2") (pintype "passive"))
    )
    (net (code "99") (name "Net-(IC8-INP)") (class "Default")
      (node (ref "C30") (pin "1") (pinfunction "1_1") (pintype "passive"))
      (node (ref "IC8") (pin "2") (pinfunction "INP_2") (pintype "input"))
      (node (ref "R49") (pin "2") (pinfunction "2_2") (pintype "passive"))
    )
    (net (code "100") (name "Net-(IC8-VP)") (class "Default")
      (node (ref "C32") (pin "1") (pinfunction "1_1") (pintype "passive"))
      (node (ref "IC8") (pin "4") (pinfunction "VP_4") (pintype "input"))
      (node (ref "R55") (pin "2") (pinfunction "2_2") (pintype "passive"))
      (node (ref "R56") (pin "1") (pinfunction "1_1") (pintype "passive"))
    )
    (net (code "101") (name "Net-(IC10-INN)") (class "Default")
      (node (ref "C37") (pin "1") (pinfunction "1_1") (pintype "passive"))
      (node (ref "IC10") (pin "3") (pinfunction "INN_3") (pintype "input"))
      (node (ref "R66") (pin "2") (pinfunction "2_2") (pintype "passive"))
    )
    (net (code "102") (name "Net-(IC10-INP)") (class "Default")
      (node (ref "C36") (pin "1") (pinfunction "1_1") (pintype "passive"))
      (node (ref "IC10") (pin "2") (pinfunction "INP_2") (pintype "input"))
      (node (ref "R65") (pin "2") (pinfunction "2_2") (pintype "passive"))
    )
    (net (code "103") (name "Net-(IC10-VP)") (class "Default")
      (node (ref "C38") (pin "1") (pinfunction "1_1") (pintype "passive"))
      (node (ref "IC10") (pin "4") (pinfunction "VP_4") (pintype "input"))
      (node (ref "R71") (pin "2") (pinfunction "2_2") (pintype "passive"))
      (node (ref "R72") (pin "1") (pinfunction "1_1") (pintype "passive"))
    )
    (net (code "104") (name "Net-(IC11-INN)") (class "Default")
      (node (ref "C40") (pin "1") (pinfunction "1_1") (pintype "passive"))
      (node (ref "IC11") (pin "3") (pinfunction "INN_3") (pintype "input"))
      (node (ref "R74") (pin "2") (pinfunction "2_2") (pintype "passive"))
    )
    (net (code "105") (name "Net-(IC11-INP)") (class "Default")
      (node (ref "C39") (pin "1") (pinfunction "1_1") (pintype "passive"))
      (node (ref "IC11") (pin "2") (pinfunction "INP_2") (pintype "input"))
      (node (ref "R73") (pin "2") (pinfunction "2_2") (pintype "passive"))
    )
    (net (code "106") (name "Net-(IC11-VP)") (class "Default")
      (node (ref "C41") (pin "1") (pinfunction "1_1") (pintype "passive"))
      (node (ref "IC11") (pin "4") (pinfunction "VP_4") (pintype "input"))
      (node (ref "R79") (pin "2") (pinfunction "2_2") (pintype "passive"))
      (node (ref "R80") (pin "1") (pinfunction "1_1") (pintype "passive"))
    )
    (net (code "107") (name "Net-(IC12-INN)") (class "Default")
      (node (ref "C43") (pin "1") (pinfunction "1_1") (pintype "passive"))
      (node (ref "IC12") (pin "3") (pinfunction "INN_3") (pintype "input"))
      (node (ref "R82") (pin "2") (pinfunction "2_2") (pintype "passive"))
    )
    (net (code "108") (name "Net-(IC12-INP)") (class "Default")
      (node (ref "C42") (pin "1") (pinfunction "1_1") (pintype "passive"))
      (node (ref "IC12") (pin "2") (pinfunction "INP_2") (pintype "input"))
      (node (ref "R81") (pin "2") (pinfunction "2_2") (pintype "passive"))
    )
    (net (code "109") (name "Net-(IC12-VP)") (class "Default")
      (node (ref "C44") (pin "1") (pinfunction "1_1") (pintype "passive"))
      (node (ref "IC12") (pin "4") (pinfunction "VP_4") (pintype "input"))
      (node (ref "R87") (pin "2") (pinfunction "2_2") (pintype "passive"))
      (node (ref "R88") (pin "1") (pinfunction "1_1") (pintype "passive"))
    )
    (net (code "110") (name "Net-(IC14-INN)") (class "Default")
      (node (ref "C49") (pin "1") (pinfunction "1_1") (pintype "passive"))
      (node (ref "IC14") (pin "3") (pinfunction "INN_3") (pintype "input"))
      (node (ref "R98") (pin "2") (pinfunction "2_2") (pintype "passive"))
    )
    (net (code "111") (name "Net-(IC14-INP)") (class "Default")
      (node (ref "C48") (pin "1") (pinfunction "1_1") (pintype "passive"))
      (node (ref "IC14") (pin "2") (pinfunction "INP_2") (pintype "input"))
      (node (ref "R97") (pin "2") (pinfunction "2_2") (pintype "passive"))
    )
    (net (code "112") (name "Net-(IC14-VP)") (class "Default")
      (node (ref "C50") (pin "1") (pinfunction "1_1") (pintype "passive"))
      (node (ref "IC14") (pin "4") (pinfunction "VP_4") (pintype "input"))
      (node (ref "R103") (pin "2") (pinfunction "2_2") (pintype "passive"))
      (node (ref "R104") (pin "1") (pinfunction "1_1") (pintype "passive"))
    )
    (net (code "113") (name "Net-(IC15-GPIO28{slash}ADC2)") (class "Default")
      (node (ref "IC15") (pin "40") (pinfunction "GPIO28/ADC2_40") (pintype "bidirectional"))
      (node (ref "R163") (pin "2") (pinfunction "2_2") (pintype "passive"))
    )
    (net (code "114") (name "Net-(IC15-USB_DM)") (class "Default")
      (node (ref "IC15") (pin "46") (pinfunction "USB_DM_46") (pintype "bidirectional"))
      (node (ref "R15") (pin "2") (pinfunction "2_2") (pintype "passive"))
    )
    (net (code "115") (name "Net-(IC15-USB_DP)") (class "Default")
      (node (ref "IC15") (pin "47") (pinfunction "USB_DP_47") (pintype "bidirectional"))
      (node (ref "R160") (pin "2") (pinfunction "2_2") (pintype "passive"))
    )
    (net (code "116") (name "Net-(IC16-INN)") (class "Default")
      (node (ref "C55") (pin "1") (pinfunction "1_1") (pintype "passive"))
      (node (ref "IC16") (pin "3") (pinfunction "INN_3") (pintype "input"))
      (node (ref "R114") (pin "2") (pinfunction "2_2") (pintype "passive"))
    )
    (net (code "117") (name "Net-(IC16-INP)") (class "Default")
      (node (ref "C54") (pin "1") (pinfunction "1_1") (pintype "passive"))
      (node (ref "IC16") (pin "2") (pinfunction "INP_2") (pintype "input"))
      (node (ref "R113") (pin "2") (pinfunction "2_2") (pintype "passive"))
    )
    (net (code "118") (name "Net-(IC16-VP)") (class "Default")
      (node (ref "C56") (pin "1") (pinfunction "1_1") (pintype "passive"))
      (node (ref "IC16") (pin "4") (pinfunction "VP_4") (pintype "input"))
      (node (ref "R119") (pin "2") (pinfunction "2_2") (pintype "passive"))
      (node (ref "R120") (pin "1") (pinfunction "1_1") (pintype "passive"))
    )
    (net (code "119") (name "Net-(IC17-+IN)") (class "Default")
      (node (ref "C60") (pin "1") (pinfunction "1_1") (pintype "passive"))
      (node (ref "C61") (pin "1") (pinfunction "1_1") (pintype "passive"))
      (node (ref "IC17") (pin "3") (pinfunction "+IN_3") (pintype "input"))
      (node (ref "R109") (pin "1") (pinfunction "1_1") (pintype "passive"))
      (node (ref "REF1") (pin "1") (pinfunction "C_1") (pintype "passive"))
      (node (ref "VREF") (pin "TP") (pinfunction "P$1_TP") (pintype "bidirectional"))
    )
    (net (code "120") (name "Net-(IC19-A0)") (class "Default")
      (node (ref "IC19") (pin "1") (pinfunction "A0_1") (pintype "bidirectional"))
      (node (ref "R128") (pin "1") (pinfunction "1_1") (pintype "passive"))
      (node (ref "R129") (pin "2") (pinfunction "2_2") (pintype "passive"))
    )
    (net (code "121") (name "Net-(IC20-1V2O)") (class "Default")
      (node (ref "C84") (pin "1") (pinfunction "1_1") (pintype "passive"))
      (node (ref "IC20") (pin "22") (pinfunction "1V2O_22") (pintype "output"))
    )
    (net (code "122") (name "Net-(IC20-EXRES1)") (class "Default")
      (node (ref "IC20") (pin "10") (pinfunction "EXRES1_10") (pintype "bidirectional"))
      (node (ref "R143") (pin "2") (pinfunction "2_2") (pintype "passive"))
    )
    (net (code "123") (name "Net-(IC20-TOCAP)") (class "Default")
      (node (ref "C85") (pin "1") (pinfunction "1_1") (pintype "passive"))
      (node (ref "IC20") (pin "20") (pinfunction "TOCAP_20") (pintype "output"))
    )
    (net (code "124") (name "Net-(IC20-XI)") (class "Default")
      (node (ref "C87") (pin "1") (pinfunction "1_1") (pintype "passive"))
      (node (ref "IC20") (pin "30") (pinfunction "XI_30") (pintype "input"))
      (node (ref "R144") (pin "1") (pinfunction "1_1") (pintype "passive"))
      (node (ref "X2") (pin "3") (pinfunction "2_3") (pintype "passive"))
    )
    (net (code "125") (name "Net-(IC20-XO)") (class "Default")
      (node (ref "C86") (pin "1") (pinfunction "1_1") (pintype "passive"))
      (node (ref "IC20") (pin "31") (pinfunction "XO_31") (pintype "output"))
      (node (ref "R144") (pin "2") (pinfunction "2_2") (pintype "passive"))
      (node (ref "X2") (pin "1") (pinfunction "1_1") (pintype "passive"))
    )
    (net (code "126") (name "Net-(IC22--IN)") (class "Default")
      (node (ref "IC22") (pin "1") (pinfunction "OUT_1") (pintype "output"))
      (node (ref "IC22") (pin "4") (pinfunction "-IN_4") (pintype "input"))
      (node (ref "R122") (pin "1") (pinfunction "1_1") (pintype "passive"))
    )
    (net (code "127") (name "Net-(P3ON-PadA)") (class "Default")
      (node (ref "P3ON") (pin "A") (pinfunction "A_A") (pintype "passive"))
      (node (ref "R123") (pin "2") (pinfunction "2_2") (pintype "passive"))
    )
    (net (code "128") (name "Net-(P5ON-PadA)") (class "Default")
      (node (ref "P5ON") (pin "A") (pinfunction "A_A") (pintype "passive"))
      (node (ref "R148") (pin "2") (pinfunction "2_2") (pintype "passive"))
    )
    (net (code "129") (name "Net-(P12ON-PadA)") (class "Default")
      (node (ref "P12ON") (pin "A") (pinfunction "A_A") (pintype "passive"))
      (node (ref "R150") (pin "2") (pinfunction "2_2") (pintype "passive"))
    )
    (net (code "130") (name "Net-(PROC-PadA)") (class "Default")
      (node (ref "PROC") (pin "A") (pinfunction "A_A") (pintype "passive"))
      (node (ref "R163") (pin "1") (pinfunction "1_1") (pintype "passive"))
    )
    (net (code "131") (name "Net-(PWR-PadC)") (class "Default")
      (node (ref "PWR") (pin "C") (pinfunction "C_C") (pintype "passive"))
      (node (ref "R151") (pin "2") (pinfunction "2_2") (pintype "passive"))
    )
    (net (code "132") (name "Net-(R36-Pad1)") (class "Default")
      (node (ref "R36") (pin "1") (pinfunction "1_1") (pintype "passive"))
      (node (ref "R37") (pin "2") (pinfunction "2_2") (pintype "passive"))
    )
    (net (code "133") (name "Net-(R37-Pad1)") (class "Default")
      (node (ref "R37") (pin "1") (pinfunction "1_1") (pintype "passive"))
      (node (ref "R38") (pin "1") (pinfunction "1_1") (pintype "passive"))
    )
    (net (code "134") (name "Net-(R38-Pad2)") (class "Default")
      (node (ref "R38") (pin "2") (pinfunction "2_2") (pintype "passive"))
      (node (ref "R39") (pin "1") (pinfunction "1_1") (pintype "passive"))
    )
    (net (code "135") (name "Net-(R44-Pad2)") (class "Default")
      (node (ref "R44") (pin "2") (pinfunction "2_2") (pintype "passive"))
      (node (ref "R45") (pin "2") (pinfunction "2_2") (pintype "passive"))
    )
    (net (code "136") (name "Net-(R45-Pad1)") (class "Default")
      (node (ref "R45") (pin "1") (pinfunction "1_1") (pintype "passive"))
      (node (ref "R46") (pin "1") (pinfunction "1_1") (pintype "passive"))
    )
    (net (code "137") (name "Net-(R46-Pad2)") (class "Default")
      (node (ref "R46") (pin "2") (pinfunction "2_2") (pintype "passive"))
      (node (ref "R47") (pin "1") (pinfunction "1_1") (pintype "passive"))
    )
    (net (code "138") (name "Net-(R52-Pad2)") (class "Default")
      (node (ref "R52") (pin "2") (pinfunction "2_2") (pintype "passive"))
      (node (ref "R53") (pin "2") (pinfunction "2_2") (pintype "passive"))
    )
    (net (code "139") (name "Net-(R53-Pad1)") (class "Default")
      (node (ref "R53") (pin "1") (pinfunction "1_1") (pintype "passive"))
      (node (ref "R54") (pin "1") (pinfunction "1_1") (pintype "passive"))
    )
    (net (code "140") (name "Net-(R54-Pad2)") (class "Default")
      (node (ref "R54") (pin "2") (pinfunction "2_2") (pintype "passive"))
      (node (ref "R55") (pin "1") (pinfunction "1_1") (pintype "passive"))
    )
    (net (code "141") (name "Net-(R57-Pad1)") (class "Default")
      (node (ref "R57") (pin "1") (pinfunction "1_1") (pintype "passive"))
      (node (ref "R58") (pin "1") (pinfunction "1_1") (pintype "passive"))
      (node (ref "R91") (pin "2") (pinfunction "2_2") (pintype "passive"))
      (node (ref "R92") (pin "2") (pinfunction "2_2") (pintype "passive"))
    )
    (net (code "142") (name "Net-(R63-5)") (class "Default")
      (node (ref "OPT1") (pin "7") (pinfunction "7_7") (pintype "passive"))
      (node (ref "R63") (pin "D2") (pinfunction "5_D2") (pintype "passive"))
    )
    (net (code "143") (name "Net-(R63-6)") (class "Default")
      (node (ref "OPT1") (pin "5") (pinfunction "5_5") (pintype "passive"))
      (node (ref "R63") (pin "C2") (pinfunction "6_C2") (pintype "passive"))
    )
    (net (code "144") (name "Net-(R63-7)") (class "Default")
      (node (ref "OPT1") (pin "3") (pinfunction "3_3") (pintype "passive"))
      (node (ref "R63") (pin "B2") (pinfunction "7_B2") (pintype "passive"))
    )
    (net (code "145") (name "Net-(R63-8)") (class "Default")
      (node (ref "OPT1") (pin "1") (pinfunction "1_1") (pintype "passive"))
      (node (ref "R63") (pin "A2") (pinfunction "8_A2") (pintype "passive"))
    )
    (net (code "146") (name "Net-(R64-5)") (class "Default")
      (node (ref "OPT2") (pin "7") (pinfunction "7_7") (pintype "passive"))
      (node (ref "R64") (pin "D2") (pinfunction "5_D2") (pintype "passive"))
    )
    (net (code "147") (name "Net-(R64-6)") (class "Default")
      (node (ref "OPT2") (pin "5") (pinfunction "5_5") (pintype "passive"))
      (node (ref "R64") (pin "C2") (pinfunction "6_C2") (pintype "passive"))
    )
    (net (code "148") (name "Net-(R64-7)") (class "Default")
      (node (ref "OPT2") (pin "3") (pinfunction "3_3") (pintype "passive"))
      (node (ref "R64") (pin "B2") (pinfunction "7_B2") (pintype "passive"))
    )
    (net (code "149") (name "Net-(R64-8)") (class "Default")
      (node (ref "OPT2") (pin "1") (pinfunction "1_1") (pintype "passive"))
      (node (ref "R64") (pin "A2") (pinfunction "8_A2") (pintype "passive"))
    )
    (net (code "150") (name "Net-(R68-Pad2)") (class "Default")
      (node (ref "R68") (pin "2") (pinfunction "2_2") (pintype "passive"))
      (node (ref "R69") (pin "2") (pinfunction "2_2") (pintype "passive"))
    )
    (net (code "151") (name "Net-(R69-Pad1)") (class "Default")
      (node (ref "R69") (pin "1") (pinfunction "1_1") (pintype "passive"))
      (node (ref "R70") (pin "1") (pinfunction "1_1") (pintype "passive"))
    )
    (net (code "152") (name "Net-(R70-Pad2)") (class "Default")
      (node (ref "R70") (pin "2") (pinfunction "2_2") (pintype "passive"))
      (node (ref "R71") (pin "1") (pinfunction "1_1") (pintype "passive"))
    )
    (net (code "153") (name "Net-(R76-Pad2)") (class "Default")
      (node (ref "R76") (pin "2") (pinfunction "2_2") (pintype "passive"))
      (node (ref "R77") (pin "2") (pinfunction "2_2") (pintype "passive"))
    )
    (net (code "154") (name "Net-(R77-Pad1)") (class "Default")
      (node (ref "R77") (pin "1") (pinfunction "1_1") (pintype "passive"))
      (node (ref "R78") (pin "1") (pinfunction "1_1") (pintype "passive"))
    )
    (net (code "155") (name "Net-(R78-Pad2)") (class "Default")
      (node (ref "R78") (pin "2") (pinfunction "2_2") (pintype "passive"))
      (node (ref "R79") (pin "1") (pinfunction "1_1") (pintype "passive"))
    )
    (net (code "156") (name "Net-(R84-Pad2)") (class "Default")
      (node (ref "R84") (pin "2") (pinfunction "2_2") (pintype "passive"))
      (node (ref "R85") (pin "2") (pinfunction "2_2") (pintype "passive"))
    )
    (net (code "157") (name "Net-(R85-Pad1)") (class "Default")
      (node (ref "R85") (pin "1") (pinfunction "1_1") (pintype "passive"))
      (node (ref "R86") (pin "1") (pinfunction "1_1") (pintype "passive"))
    )
    (net (code "158") (name "Net-(R86-Pad2)") (class "Default")
      (node (ref "R86") (pin "2") (pinfunction "2_2") (pintype "passive"))
      (node (ref "R87") (pin "1") (pinfunction "1_1") (pintype "passive"))
    )
    (net (code "159") (name "Net-(R100-Pad2)") (class "Default")
      (node (ref "R100") (pin "2") (pinfunction "2_2") (pintype "passive"))
      (node (ref "R101") (pin "2") (pinfunction "2_2") (pintype "passive"))
    )
    (net (code "160") (name "Net-(R101-Pad1)") (class "Default")
      (node (ref "R101") (pin "1") (pinfunction "1_1") (pintype "passive"))
      (node (ref "R102") (pin "1") (pinfunction "1_1") (pintype "passive"))
    )
    (net (code "161") (name "Net-(R102-Pad2)") (class "Default")
      (node (ref "R102") (pin "2") (pinfunction "2_2") (pintype "passive"))
      (node (ref "R103") (pin "1") (pinfunction "1_1") (pintype "passive"))
    )
    (net (code "162") (name "Net-(R116-Pad2)") (class "Default")
      (node (ref "R116") (pin "2") (pinfunction "2_2") (pintype "passive"))
      (node (ref "R117") (pin "2") (pinfunction "2_2") (pintype "passive"))
    )
    (net (code "163") (name "Net-(R117-Pad1)") (class "Default")
      (node (ref "R117") (pin "1") (pinfunction "1_1") (pintype "passive"))
      (node (ref "R118") (pin "1") (pinfunction "1_1") (pintype "passive"))
    )
    (net (code "164") (name "Net-(R118-Pad2)") (class "Default")
      (node (ref "R118") (pin "2") (pinfunction "2_2") (pintype "passive"))
      (node (ref "R119") (pin "1") (pinfunction "1_1") (pintype "passive"))
    )
    (net (code "165") (name "Net-(X1-2)") (class "Default")
      (node (ref "C59") (pin "1") (pinfunction "1_1") (pintype "passive"))
      (node (ref "R16") (pin "1") (pinfunction "1_1") (pintype "passive"))
      (node (ref "X1") (pin "3") (pinfunction "2_3") (pintype "passive"))
    )
    (net (code "166") (name "OUT_1") (class "Default")
      (node (ref "K1") (pin "4") (pinfunction "4_4") (pintype "passive"))
      (node (ref "K1") (pin "5") (pinfunction "5_5") (pintype "passive"))
      (node (ref "L_OUT1") (pin "B2,8") (pinfunction "MOUNT_B2,8") (pintype "passive"))
      (node (ref "R36") (pin "2") (pinfunction "2_2") (pintype "passive"))
    )
    (net (code "167") (name "OUT_2") (class "Default")
      (node (ref "K2") (pin "4") (pinfunction "4_4") (pintype "passive"))
      (node (ref "K2") (pin "5") (pinfunction "5_5") (pintype "passive"))
      (node (ref "L_OUT2") (pin "B2,8") (pinfunction "MOUNT_B2,8") (pintype "passive"))
      (node (ref "R52") (pin "1") (pinfunction "1_1") (pintype "passive"))
    )
    (net (code "168") (name "OUT_3") (class "Default")
      (node (ref "K3") (pin "4") (pinfunction "4_4") (pintype "passive"))
      (node (ref "K3") (pin "5") (pinfunction "5_5") (pintype "passive"))
      (node (ref "L_OUT3") (pin "B2,8") (pinfunction "MOUNT_B2,8") (pintype "passive"))
      (node (ref "R68") (pin "1") (pinfunction "1_1") (pintype "passive"))
    )
    (net (code "169") (name "OUT_4") (class "Default")
      (node (ref "K4") (pin "4") (pinfunction "4_4") (pintype "passive"))
      (node (ref "K4") (pin "5") (pinfunction "5_5") (pintype "passive"))
      (node (ref "L_OUT4") (pin "B2,8") (pinfunction "MOUNT_B2,8") (pintype "passive"))
      (node (ref "R84") (pin "1") (pinfunction "1_1") (pintype "passive"))
    )
    (net (code "170") (name "OUT_5") (class "Default")
      (node (ref "K5") (pin "4") (pinfunction "4_4") (pintype "passive"))
      (node (ref "K5") (pin "5") (pinfunction "5_5") (pintype "passive"))
      (node (ref "L_OUT5") (pin "B2,8") (pinfunction "MOUNT_B2,8") (pintype "passive"))
      (node (ref "R44") (pin "1") (pinfunction "1_1") (pintype "passive"))
    )
    (net (code "171") (name "OUT_6") (class "Default")
      (node (ref "K6") (pin "4") (pinfunction "4_4") (pintype "passive"))
      (node (ref "K6") (pin "5") (pinfunction "5_5") (pintype "passive"))
      (node (ref "L_OUT6") (pin "B2,8") (pinfunction "MOUNT_B2,8") (pintype "passive"))
      (node (ref "R76") (pin "1") (pinfunction "1_1") (pintype "passive"))
    )
    (net (code "172") (name "OUT_7") (class "Default")
      (node (ref "K7") (pin "4") (pinfunction "4_4") (pintype "passive"))
      (node (ref "K7") (pin "5") (pinfunction "5_5") (pintype "passive"))
      (node (ref "L_OUT7") (pin "B2,8") (pinfunction "MOUNT_B2,8") (pintype "passive"))
      (node (ref "R100") (pin "1") (pinfunction "1_1") (pintype "passive"))
    )
    (net (code "173") (name "OUT_8") (class "Default")
      (node (ref "K8") (pin "4") (pinfunction "4_4") (pintype "passive"))
      (node (ref "K8") (pin "5") (pinfunction "5_5") (pintype "passive"))
      (node (ref "L_OUT8") (pin "B2,8") (pinfunction "MOUNT_B2,8") (pintype "passive"))
      (node (ref "R116") (pin "1") (pinfunction "1_1") (pintype "passive"))
    )
    (net (code "174") (name "QSPI_SCLK") (class "Default")
      (node (ref "IC15") (pin "52") (pinfunction "QSPI_SCLK_52") (pintype "bidirectional"))
      (node (ref "IC18") (pin "6") (pinfunction "CLK_6") (pintype "bidirectional"))
    )
    (net (code "175") (name "QSPI_SD0") (class "Default")
      (node (ref "IC15") (pin "53") (pinfunction "QSPI_SD0_53") (pintype "bidirectional"))
      (node (ref "IC18") (pin "5") (pinfunction "DI/IO0_5") (pintype "bidirectional"))
    )
    (net (code "176") (name "QSPI_SD1") (class "Default")
      (node (ref "IC15") (pin "55") (pinfunction "QSPI_SD1_55") (pintype "bidirectional"))
      (node (ref "IC18") (pin "2") (pinfunction "DO/IO1_2") (pintype "bidirectional"))
    )
    (net (code "177") (name "QSPI_SD2") (class "Default")
      (node (ref "IC15") (pin "54") (pinfunction "QSPI_SD2_54") (pintype "bidirectional"))
      (node (ref "IC18") (pin "3") (pinfunction "~{WP}/IO2_3") (pintype "bidirectional"))
    )
    (net (code "178") (name "QSPI_SD3") (class "Default")
      (node (ref "IC15") (pin "51") (pinfunction "QSPI_SD3_51") (pintype "bidirectional"))
      (node (ref "IC18") (pin "7") (pinfunction "~{HOLD}/IO3_7") (pintype "bidirectional"))
    )
    (net (code "179") (name "RCT") (class "Default")
      (node (ref "C79") (pin "1") (pinfunction "1_1") (pintype "passive"))
      (node (ref "ETH1") (pin "5") (pinfunction "P5/RCT_5") (pintype "passive"))
      (node (ref "R137") (pin "1") (pinfunction "1_1") (pintype "passive"))
      (node (ref "R138") (pin "1") (pinfunction "1_1") (pintype "passive"))
    )
    (net (code "180") (name "RDC_RD_N") (class "Default")
      (node (ref "C81") (pin "1") (pinfunction "1_1") (pintype "passive"))
      (node (ref "R136") (pin "2") (pinfunction "2_2") (pintype "passive"))
      (node (ref "R137") (pin "2") (pinfunction "2_2") (pintype "passive"))
    )
    (net (code "181") (name "RDC_RD_P") (class "Default")
      (node (ref "C82") (pin "1") (pinfunction "1_1") (pintype "passive"))
      (node (ref "R135") (pin "2") (pinfunction "2_2") (pintype "passive"))
      (node (ref "R138") (pin "2") (pinfunction "2_2") (pintype "passive"))
    )
    (net (code "182") (name "RD_N") (class "Default")
      (node (ref "C81") (pin "2") (pinfunction "2_2") (pintype "passive"))
      (node (ref "ETH1") (pin "6") (pinfunction "RD-_6") (pintype "passive"))
    )
    (net (code "183") (name "RD_P") (class "Default")
      (node (ref "C82") (pin "2") (pinfunction "2_2") (pintype "passive"))
      (node (ref "ETH1") (pin "4") (pinfunction "RD+_4") (pintype "passive"))
    )
    (net (code "184") (name "RELAY_1") (class "Default")
      (node (ref "D1") (pin "A") (pinfunction "A_A") (pintype "passive"))
      (node (ref "K1") (pin "1") (pinfunction "1_1") (pintype "passive"))
      (node (ref "R24") (pin "2") (pinfunction "2_2") (pintype "passive"))
    )
    (net (code "185") (name "RELAY_2") (class "Default")
      (node (ref "D2") (pin "A") (pinfunction "A_A") (pintype "passive"))
      (node (ref "K2") (pin "1") (pinfunction "1_1") (pintype "passive"))
      (node (ref "R23") (pin "2") (pinfunction "2_2") (pintype "passive"))
    )
    (net (code "186") (name "RELAY_3") (class "Default")
      (node (ref "D3") (pin "A") (pinfunction "A_A") (pintype "passive"))
      (node (ref "K3") (pin "1") (pinfunction "1_1") (pintype "passive"))
      (node (ref "R22") (pin "2") (pinfunction "2_2") (pintype "passive"))
    )
    (net (code "187") (name "RELAY_4") (class "Default")
      (node (ref "D4") (pin "A") (pinfunction "A_A") (pintype "passive"))
      (node (ref "K4") (pin "1") (pinfunction "1_1") (pintype "passive"))
      (node (ref "R21") (pin "2") (pinfunction "2_2") (pintype "passive"))
    )
    (net (code "188") (name "RELAY_5") (class "Default")
      (node (ref "D5") (pin "A") (pinfunction "A_A") (pintype "passive"))
      (node (ref "K5") (pin "1") (pinfunction "1_1") (pintype "passive"))
      (node (ref "R20") (pin "2") (pinfunction "2_2") (pintype "passive"))
    )
    (net (code "189") (name "RELAY_6") (class "Default")
      (node (ref "D6") (pin "A") (pinfunction "A_A") (pintype "passive"))
      (node (ref "K6") (pin "1") (pinfunction "1_1") (pintype "passive"))
      (node (ref "R19") (pin "2") (pinfunction "2_2") (pintype "passive"))
    )
    (net (code "190") (name "RELAY_7") (class "Default")
      (node (ref "D7") (pin "A") (pinfunction "A_A") (pintype "passive"))
      (node (ref "K7") (pin "1") (pinfunction "1_1") (pintype "passive"))
      (node (ref "R18") (pin "2") (pinfunction "2_2") (pintype "passive"))
    )
    (net (code "191") (name "RELAY_8") (class "Default")
      (node (ref "D8") (pin "A") (pinfunction "A_A") (pintype "passive"))
      (node (ref "K8") (pin "1") (pinfunction "1_1") (pintype "passive"))
      (node (ref "R17") (pin "2") (pinfunction "2_2") (pintype "passive"))
    )
    (net (code "192") (name "REL_0") (class "Default")
      (node (ref "IC3") (pin "8") (pinfunction "8B_8") (pintype "bidirectional"))
      (node (ref "IC4") (pin "17") (pinfunction "IO1.0_17") (pintype "bidirectional"))
    )
    (net (code "193") (name "REL_1") (class "Default")
      (node (ref "IC3") (pin "7") (pinfunction "7B_7") (pintype "bidirectional"))
      (node (ref "IC4") (pin "18") (pinfunction "IO1.1_18") (pintype "bidirectional"))
    )
    (net (code "194") (name "REL_2") (class "Default")
      (node (ref "IC3") (pin "6") (pinfunction "6B_6") (pintype "bidirectional"))
      (node (ref "IC4") (pin "19") (pinfunction "IO1.2_19") (pintype "bidirectional"))
    )
    (net (code "195") (name "REL_3") (class "Default")
      (node (ref "IC3") (pin "5") (pinfunction "5B_5") (pintype "bidirectional"))
      (node (ref "IC4") (pin "20") (pinfunction "IO1.3_20") (pintype "bidirectional"))
    )
    (net (code "196") (name "REL_4") (class "Default")
      (node (ref "IC3") (pin "4") (pinfunction "4B_4") (pintype "bidirectional"))
      (node (ref "IC4") (pin "21") (pinfunction "IO1.4_21") (pintype "bidirectional"))
    )
    (net (code "197") (name "REL_5") (class "Default")
      (node (ref "IC3") (pin "3") (pinfunction "3B_3") (pintype "bidirectional"))
      (node (ref "IC4") (pin "22") (pinfunction "IO1.5_22") (pintype "bidirectional"))
    )
    (net (code "198") (name "REL_6") (class "Default")
      (node (ref "IC3") (pin "2") (pinfunction "2B_2") (pintype "bidirectional"))
      (node (ref "IC4") (pin "23") (pinfunction "IO1.6_23") (pintype "bidirectional"))
    )
    (net (code "199") (name "REL_7") (class "Default")
      (node (ref "IC3") (pin "1") (pinfunction "1B_1") (pintype "bidirectional"))
      (node (ref "IC4") (pin "24") (pinfunction "IO1.7_24") (pintype "bidirectional"))
    )
    (net (code "200") (name "RP_XI") (class "Default")
      (node (ref "C58") (pin "1") (pinfunction "1_1") (pintype "passive"))
      (node (ref "IC15") (pin "20") (pinfunction "XIN_20") (pintype "bidirectional"))
      (node (ref "X1") (pin "1") (pinfunction "1_1") (pintype "passive"))
    )
    (net (code "201") (name "RP_XO") (class "Default")
      (node (ref "IC15") (pin "21") (pinfunction "XOUT_21") (pintype "bidirectional"))
      (node (ref "R16") (pin "2") (pinfunction "2_2") (pintype "passive"))
    )
    (net (code "202") (name "RUN") (class "Default")
      (node (ref "GDGC") (pin "2") (pinfunction "P$2_2") (pintype "bidirectional"))
      (node (ref "IC15") (pin "26") (pinfunction "RUN_26") (pintype "bidirectional"))
      (node (ref "R132") (pin "2") (pinfunction "2_2") (pintype "passive"))
      (node (ref "RESET") (pin "2") (pinfunction "P$2_2") (pintype "bidirectional"))
    )
    (net (code "203") (name "RX_RD_N") (class "Default")
      (node (ref "IC20") (pin "5") (pinfunction "RXN_5") (pintype "input"))
      (node (ref "R136") (pin "1") (pinfunction "1_1") (pintype "passive"))
    )
    (net (code "204") (name "RX_RD_P") (class "Default")
      (node (ref "IC20") (pin "6") (pinfunction "RXP_6") (pintype "input"))
      (node (ref "R135") (pin "1") (pinfunction "1_1") (pintype "passive"))
    )
    (net (code "205") (name "SH") (class "Default")
      (node (ref "C78") (pin "1") (pinfunction "1_1") (pintype "passive"))
      (node (ref "C83") (pin "2") (pinfunction "2_2") (pintype "passive"))
      (node (ref "ETH1") (pin "13") (pinfunction "SHIELD_13") (pintype "passive"))
      (node (ref "ETH1") (pin "14") (pinfunction "SHIELD_14") (pintype "passive"))
      (node (ref "R110") (pin "2") (pinfunction "2_2") (pintype "passive"))
      (node (ref "R131") (pin "1") (pinfunction "1_1") (pintype "passive"))
      (node (ref "USB1") (pin "SHLD1") (pinfunction "SHILED_SHLD1") (pintype "power_in"))
      (node (ref "USB1") (pin "SHLD2") (pinfunction "SHILED_SHLD2") (pintype "power_in"))
      (node (ref "USB1") (pin "SHLD3") (pinfunction "SHILED_SHLD3") (pintype "power_in"))
      (node (ref "USB1") (pin "SHLD4") (pinfunction "SHILED_SHLD4") (pintype "power_in"))
    )
    (net (code "206") (name "SRC1") (class "Default")
      (node (ref "C21") (pin "1") (pinfunction "1_1") (pintype "passive"))
      (node (ref "C22") (pin "1") (pinfunction "1_1") (pintype "passive"))
      (node (ref "C5") (pin "1") (pinfunction "1_1") (pintype "passive"))
      (node (ref "D11") (pin "C") (pinfunction "C_C") (pintype "passive"))
      (node (ref "IC13") (pin "3") (pinfunction "SRC2_3") (pintype "output"))
      (node (ref "IC13") (pin "4") (pinfunction "SRC_4") (pintype "output"))
      (node (ref "L3") (pin "1") (pinfunction "1_1") (pintype "passive"))
      (node (ref "R60") (pin "2") (pinfunction "2_2") (pintype "passive"))
    )
    (net (code "207") (name "SRC2") (class "Default")
      (node (ref "C46") (pin "1") (pinfunction "1_1") (pintype "passive"))
      (node (ref "C51") (pin "1") (pinfunction "1_1") (pintype "passive"))
      (node (ref "C52") (pin "1") (pinfunction "1_1") (pintype "passive"))
      (node (ref "D14") (pin "C") (pinfunction "C_C") (pintype "passive"))
      (node (ref "IC5") (pin "3") (pinfunction "SRC2_3") (pintype "output"))
      (node (ref "IC5") (pin "4") (pinfunction "SRC_4") (pintype "output"))
      (node (ref "L5") (pin "1") (pinfunction "1_1") (pintype "passive"))
      (node (ref "R107") (pin "2") (pinfunction "2_2") (pintype "passive"))
    )
    (net (code "208") (name "SWCLK") (class "Default")
      (node (ref "GDGC") (pin "1") (pinfunction "P$1_1") (pintype "bidirectional"))
      (node (ref "IC15") (pin "24") (pinfunction "SWCLK_24") (pintype "bidirectional"))
    )
    (net (code "209") (name "SWDIO") (class "Default")
      (node (ref "GDGC") (pin "3") (pinfunction "P$3_3") (pintype "bidirectional"))
      (node (ref "IC15") (pin "25") (pinfunction "SWDIO_25") (pintype "bidirectional"))
    )
    (net (code "210") (name "TCT") (class "Default")
      (node (ref "C80") (pin "1") (pinfunction "1_1") (pintype "passive"))
      (node (ref "ETH1") (pin "2") (pinfunction "P4/TCT_2") (pintype "passive"))
      (node (ref "R146") (pin "1") (pinfunction "1_1") (pintype "passive"))
    )
    (net (code "211") (name "TD_N") (class "Default")
      (node (ref "ETH1") (pin "3") (pinfunction "TD-_3") (pintype "passive"))
      (node (ref "R134") (pin "2") (pinfunction "2_2") (pintype "passive"))
      (node (ref "R140") (pin "1") (pinfunction "1_1") (pintype "passive"))
    )
    (net (code "212") (name "TD_P") (class "Default")
      (node (ref "ETH1") (pin "1") (pinfunction "TD+_1") (pintype "passive"))
      (node (ref "R133") (pin "2") (pinfunction "2_2") (pintype "passive"))
      (node (ref "R139") (pin "1") (pinfunction "1_1") (pintype "passive"))
    )
    (net (code "213") (name "TX_CH1") (class "Default")
      (node (ref "IC6") (pin "6") (pinfunction "TX_6") (pintype "bidirectional"))
      (node (ref "R155") (pin "1") (pinfunction "1_1") (pintype "passive"))
    )
    (net (code "214") (name "TX_CH2") (class "Default")
      (node (ref "IC8") (pin "6") (pinfunction "TX_6") (pintype "bidirectional"))
      (node (ref "R154") (pin "1") (pinfunction "1_1") (pintype "passive"))
    )
    (net (code "215") (name "TX_CH3") (class "Default")
      (node (ref "IC10") (pin "6") (pinfunction "TX_6") (pintype "bidirectional"))
      (node (ref "R153") (pin "1") (pinfunction "1_1") (pintype "passive"))
    )
    (net (code "216") (name "TX_CH4") (class "Default")
      (node (ref "IC12") (pin "6") (pinfunction "TX_6") (pintype "bidirectional"))
      (node (ref "R59") (pin "1") (pinfunction "1_1") (pintype "passive"))
    )
    (net (code "217") (name "TX_CH5") (class "Default")
      (node (ref "IC7") (pin "6") (pinfunction "TX_6") (pintype "bidirectional"))
      (node (ref "R159") (pin "1") (pinfunction "1_1") (pintype "passive"))
    )
    (net (code "218") (name "TX_CH6") (class "Default")
      (node (ref "IC11") (pin "6") (pinfunction "TX_6") (pintype "bidirectional"))
      (node (ref "R158") (pin "1") (pinfunction "1_1") (pintype "passive"))
    )
    (net (code "219") (name "TX_CH7") (class "Default")
      (node (ref "IC14") (pin "6") (pinfunction "TX_6") (pintype "bidirectional"))
      (node (ref "R157") (pin "1") (pinfunction "1_1") (pintype "passive"))
    )
    (net (code "220") (name "TX_CH8") (class "Default")
      (node (ref "IC16") (pin "6") (pinfunction "TX_6") (pintype "bidirectional"))
      (node (ref "R156") (pin "1") (pinfunction "1_1") (pintype "passive"))
    )
    (net (code "221") (name "TX_MUX1") (class "Default")
      (node (ref "IC9") (pin "4") (pinfunction "D0_4") (pintype "bidirectional"))
      (node (ref "OPT1") (pin "10") (pinfunction "10_10") (pintype "passive"))
      (node (ref "R89") (pin "D1") (pinfunction "4_D1") (pintype "passive"))
    )
    (net (code "222") (name "TX_MUX2") (class "Default")
      (node (ref "IC9") (pin "3") (pinfunction "D1_3") (pintype "bidirectional"))
      (node (ref "OPT1") (pin "12") (pinfunction "12_12") (pintype "passive"))
      (node (ref "R89") (pin "C1") (pinfunction "3_C1") (pintype "passive"))
    )
    (net (code "223") (name "TX_MUX3") (class "Default")
      (node (ref "IC9") (pin "2") (pinfunction "D2_2") (pintype "bidirectional"))
      (node (ref "OPT1") (pin "14") (pinfunction "14_14") (pintype "passive"))
      (node (ref "R89") (pin "B1") (pinfunction "2_B1") (pintype "passive"))
    )
    (net (code "224") (name "TX_MUX4") (class "Default")
      (node (ref "IC9") (pin "1") (pinfunction "D3_1") (pintype "bidirectional"))
      (node (ref "OPT1") (pin "16") (pinfunction "16_16") (pintype "passive"))
      (node (ref "R89") (pin "A1") (pinfunction "1_A1") (pintype "passive"))
    )
    (net (code "225") (name "TX_MUX5") (class "Default")
      (node (ref "IC9") (pin "15") (pinfunction "D4_15") (pintype "bidirectional"))
      (node (ref "OPT2") (pin "16") (pinfunction "16_16") (pintype "passive"))
      (node (ref "R90") (pin "A1") (pinfunction "1_A1") (pintype "passive"))
    )
    (net (code "226") (name "TX_MUX6") (class "Default")
      (node (ref "IC9") (pin "14") (pinfunction "D5_14") (pintype "bidirectional"))
      (node (ref "OPT2") (pin "14") (pinfunction "14_14") (pintype "passive"))
      (node (ref "R90") (pin "B1") (pinfunction "2_B1") (pintype "passive"))
    )
    (net (code "227") (name "TX_MUX7") (class "Default")
      (node (ref "IC9") (pin "13") (pinfunction "D6_13") (pintype "bidirectional"))
      (node (ref "OPT2") (pin "12") (pinfunction "12_12") (pintype "passive"))
      (node (ref "R90") (pin "C1") (pinfunction "3_C1") (pintype "passive"))
    )
    (net (code "228") (name "TX_MUX8") (class "Default")
      (node (ref "IC9") (pin "12") (pinfunction "D7_12") (pintype "bidirectional"))
      (node (ref "OPT2") (pin "10") (pinfunction "10_10") (pintype "passive"))
      (node (ref "R90") (pin "D1") (pinfunction "4_D1") (pintype "passive"))
    )
    (net (code "229") (name "TX_OUT") (class "Default")
      (node (ref "IC9") (pin "5") (pinfunction "Y_5") (pintype "bidirectional"))
      (node (ref "R91") (pin "1") (pinfunction "1_1") (pintype "passive"))
    )
    (net (code "230") (name "TX_TD_N") (class "Default")
      (node (ref "IC20") (pin "1") (pinfunction "TXN_1") (pintype "output"))
      (node (ref "R134") (pin "1") (pinfunction "1_1") (pintype "passive"))
    )
    (net (code "231") (name "TX_TD_P") (class "Default")
      (node (ref "IC20") (pin "2") (pinfunction "TXP_2") (pintype "output"))
      (node (ref "R133") (pin "1") (pinfunction "1_1") (pintype "passive"))
    )
    (net (code "232") (name "UART0_RX") (class "Default")
      (node (ref "IC15") (pin "2") (pinfunction "GPIO0_2") (pintype "bidirectional"))
      (node (ref "R58") (pin "2") (pinfunction "2_2") (pintype "passive"))
      (node (ref "RGTG") (pin "1") (pinfunction "P$1_1") (pintype "bidirectional"))
    )
    (net (code "233") (name "UART0_TX") (class "Default")
      (node (ref "IC15") (pin "3") (pinfunction "GPIO1_3") (pintype "bidirectional"))
      (node (ref "R57") (pin "2") (pinfunction "2_2") (pintype "passive"))
      (node (ref "RGTG") (pin "3") (pinfunction "P$3_3") (pintype "bidirectional"))
    )
    (net (code "234") (name "USB2_DP_N") (class "Default")
      (node (ref "ESD1") (pin "3") (pinfunction "C2_3") (pintype "bidirectional"))
      (node (ref "R15") (pin "1") (pinfunction "1_1") (pintype "passive"))
      (node (ref "USB1") (pin "A7") (pinfunction "D-_A7") (pintype "bidirectional"))
      (node (ref "USB1") (pin "B7") (pinfunction "D-_B7") (pintype "bidirectional"))
    )
    (net (code "235") (name "USB2_DP_P") (class "Default")
      (node (ref "ESD1") (pin "2") (pinfunction "C1_2") (pintype "bidirectional"))
      (node (ref "R160") (pin "1") (pinfunction "1_1") (pintype "passive"))
      (node (ref "USB1") (pin "A6") (pinfunction "D+_A6") (pintype "bidirectional"))
      (node (ref "USB1") (pin "B6") (pinfunction "D+_B6") (pintype "bidirectional"))
    )
    (net (code "236") (name "USB_BOOT") (class "Default")
      (node (ref "BOOT") (pin "1") (pinfunction "P$1_1") (pintype "bidirectional"))
      (node (ref "R112") (pin "1") (pinfunction "1_1") (pintype "passive"))
    )
    (net (code "237") (name "VBUS") (class "Default")
      (node (ref "C65") (pin "1") (pinfunction "1_1") (pintype "passive"))
      (node (ref "C66") (pin "1") (pinfunction "1_1") (pintype "passive"))
      (node (ref "C97") (pin "1") (pinfunction "1_1") (pintype "passive"))
      (node (ref "C98") (pin "1") (pinfunction "1_1") (pintype "passive"))
      (node (ref "D15") (pin "C") (pinfunction "C_C") (pintype "passive"))
      (node (ref "ESD1") (pin "4") (pinfunction "C3_4") (pintype "bidirectional"))
      (node (ref "IC21") (pin "1") (pinfunction "VIN_1") (pintype "bidirectional"))
      (node (ref "IC21") (pin "3") (pinfunction "EN_3") (pintype "bidirectional"))
      (node (ref "R121") (pin "1") (pinfunction "1_1") (pintype "passive"))
      (node (ref "R126") (pin "1") (pinfunction "1_1") (pintype "passive"))
      (node (ref "USB1") (pin "VBUS1") (pinfunction "VBUS_VBUS1") (pintype "power_in"))
      (node (ref "USB1") (pin "VBUS2") (pinfunction "VBUS_VBUS2") (pintype "power_in"))
      (node (ref "VBUS") (pin "TP") (pinfunction "P$1_TP") (pintype "bidirectional"))
    )
    (net (code "238") (name "VNI1") (class "Default")
      (node (ref "C21") (pin "2") (pinfunction "2_2") (pintype "passive"))
      (node (ref "IC13") (pin "1") (pinfunction "VCC_1") (pintype "output"))
      (node (ref "VNI1") (pin "TP") (pinfunction "P$1_TP") (pintype "bidirectional"))
    )
    (net (code "239") (name "VNI2") (class "Default")
      (node (ref "C46") (pin "2") (pinfunction "2_2") (pintype "passive"))
      (node (ref "IC5") (pin "1") (pinfunction "VCC_1") (pintype "output"))
      (node (ref "VNI2") (pin "TP") (pinfunction "P$1_TP") (pintype "bidirectional"))
    )
    (net (code "240") (name "W5500_MISO") (class "Default")
      (node (ref "IC15") (pin "27") (pinfunction "GPIO16_27") (pintype "bidirectional"))
      (node (ref "IC20") (pin "34") (pinfunction "MISO_34") (pintype "output"))
    )
    (net (code "241") (name "W5500_MOSI") (class "Default")
      (node (ref "IC15") (pin "30") (pinfunction "GPIO19_30") (pintype "bidirectional"))
      (node (ref "IC20") (pin "35") (pinfunction "MOSI_35") (pintype "input"))
    )
    (net (code "242") (name "W5500_SCK") (class "Default")
      (node (ref "IC15") (pin "29") (pinfunction "GPIO18_29") (pintype "bidirectional"))
      (node (ref "IC20") (pin "33") (pinfunction "SCLK_33") (pintype "input"))
    )
    (net (code "243") (name "unconnected-(IC4-INTA-Pad16)") (class "Default")
      (node (ref "IC4") (pin "16") (pinfunction "INTA_16") (pintype "bidirectional"))
    )
    (net (code "244") (name "unconnected-(IC4-INTB-Pad15)") (class "Default")
      (node (ref "IC4") (pin "15") (pinfunction "INTB_15") (pintype "bidirectional"))
    )
    (net (code "245") (name "unconnected-(IC4-IO2.4-Pad1)") (class "Default")
      (node (ref "IC4") (pin "1") (pinfunction "IO2.4_1") (pintype "bidirectional"))
    )
    (net (code "246") (name "unconnected-(IC4-IO2.5-Pad2)") (class "Default")
      (node (ref "IC4") (pin "2") (pinfunction "IO2.5_2") (pintype "bidirectional"))
    )
    (net (code "247") (name "unconnected-(IC4-IO2.6-Pad3)") (class "Default")
      (node (ref "IC4") (pin "3") (pinfunction "IO2.6_3") (pintype "bidirectional"))
    )
    (net (code "248") (name "unconnected-(IC4-IO2.7-Pad4)") (class "Default")
      (node (ref "IC4") (pin "4") (pinfunction "IO2.7_4") (pintype "bidirectional"))
    )
    (net (code "249") (name "unconnected-(IC6-PF-Pad7)") (class "Default")
      (node (ref "IC6") (pin "7") (pinfunction "PF_7") (pintype "bidirectional"))
    )
    (net (code "250") (name "unconnected-(IC6-RX-Pad8)") (class "Default")
      (node (ref "IC6") (pin "8") (pinfunction "RX_8") (pintype "bidirectional"))
    )
    (net (code "251") (name "unconnected-(IC7-PF-Pad7)") (class "Default")
      (node (ref "IC7") (pin "7") (pinfunction "PF_7") (pintype "bidirectional"))
    )
    (net (code "252") (name "unconnected-(IC7-RX-Pad8)") (class "Default")
      (node (ref "IC7") (pin "8") (pinfunction "RX_8") (pintype "bidirectional"))
    )
    (net (code "253") (name "unconnected-(IC8-PF-Pad7)") (class "Default")
      (node (ref "IC8") (pin "7") (pinfunction "PF_7") (pintype "bidirectional"))
    )
    (net (code "254") (name "unconnected-(IC8-RX-Pad8)") (class "Default")
      (node (ref "IC8") (pin "8") (pinfunction "RX_8") (pintype "bidirectional"))
    )
    (net (code "255") (name "unconnected-(IC10-PF-Pad7)") (class "Default")
      (node (ref "IC10") (pin "7") (pinfunction "PF_7") (pintype "bidirectional"))
    )
    (net (code "256") (name "unconnected-(IC10-RX-Pad8)") (class "Default")
      (node (ref "IC10") (pin "8") (pinfunction "RX_8") (pintype "bidirectional"))
    )
    (net (code "257") (name "unconnected-(IC11-PF-Pad7)") (class "Default")
      (node (ref "IC11") (pin "7") (pinfunction "PF_7") (pintype "bidirectional"))
    )
    (net (code "258") (name "unconnected-(IC11-RX-Pad8)") (class "Default")
      (node (ref "IC11") (pin "8") (pinfunction "RX_8") (pintype "bidirectional"))
    )
    (net (code "259") (name "unconnected-(IC12-PF-Pad7)") (class "Default")
      (node (ref "IC12") (pin "7") (pinfunction "PF_7") (pintype "bidirectional"))
    )
    (net (code "260") (name "unconnected-(IC12-RX-Pad8)") (class "Default")
      (node (ref "IC12") (pin "8") (pinfunction "RX_8") (pintype "bidirectional"))
    )
    (net (code "261") (name "unconnected-(IC14-PF-Pad7)") (class "Default")
      (node (ref "IC14") (pin "7") (pinfunction "PF_7") (pintype "bidirectional"))
    )
    (net (code "262") (name "unconnected-(IC14-RX-Pad8)") (class "Default")
      (node (ref "IC14") (pin "8") (pinfunction "RX_8") (pintype "bidirectional"))
    )
    (net (code "263") (name "unconnected-(IC15-GPIO27{slash}ADC1-Pad39)") (class "Default")
      (node (ref "IC15") (pin "39") (pinfunction "GPIO27/ADC1_39") (pintype "bidirectional"))
    )
    (net (code "264") (name "unconnected-(IC16-PF-Pad7)") (class "Default")
      (node (ref "IC16") (pin "7") (pinfunction "PF_7") (pintype "bidirectional"))
    )
    (net (code "265") (name "unconnected-(IC16-RX-Pad8)") (class "Default")
      (node (ref "IC16") (pin "8") (pinfunction "RX_8") (pintype "bidirectional"))
    )
    (net (code "266") (name "unconnected-(IC20-DNC-Pad7)") (class "Default")
      (node (ref "IC20") (pin "7") (pinfunction "DNC_7") (pintype "bidirectional"))
    )
    (net (code "267") (name "unconnected-(IC20-DUPLED-Pad26)") (class "Default")
      (node (ref "IC20") (pin "26") (pinfunction "DUPLED_26") (pintype "output"))
    )
    (net (code "268") (name "unconnected-(IC20-RSVD1-Pad23)") (class "Default")
      (node (ref "IC20") (pin "23") (pinfunction "RSVD1_23") (pintype "input"))
    )
    (net (code "269") (name "unconnected-(IC20-RSVD2-Pad38)") (class "Default")
      (node (ref "IC20") (pin "38") (pinfunction "RSVD2_38") (pintype "input"))
    )
    (net (code "270") (name "unconnected-(IC20-RSVD3-Pad39)") (class "Default")
      (node (ref "IC20") (pin "39") (pinfunction "RSVD3_39") (pintype "input"))
    )
    (net (code "271") (name "unconnected-(IC20-RSVD4-Pad40)") (class "Default")
      (node (ref "IC20") (pin "40") (pinfunction "RSVD4_40") (pintype "input"))
    )
    (net (code "272") (name "unconnected-(IC20-RSVD5-Pad41)") (class "Default")
      (node (ref "IC20") (pin "41") (pinfunction "RSVD5_41") (pintype "input"))
    )
    (net (code "273") (name "unconnected-(IC20-RSVD6-Pad42)") (class "Default")
      (node (ref "IC20") (pin "42") (pinfunction "RSVD6_42") (pintype "input"))
    )
    (net (code "274") (name "unconnected-(IC20-SPDLED-Pad24)") (class "Default")
      (node (ref "IC20") (pin "24") (pinfunction "SPDLED_24") (pintype "output"))
    )
    (net (code "275") (name "unconnected-(IC20-VBG-Pad18)") (class "Default")
      (node (ref "IC20") (pin "18") (pinfunction "VBG_18") (pintype "output"))
    )
    (net (code "276") (name "unconnected-(IC21-NC-Pad4)") (class "Default")
      (node (ref "IC21") (pin "4") (pinfunction "NC_4") (pintype "bidirectional"))
    )
    (net (code "277") (name "unconnected-(R149-5-PadD2)") (class "Default")
      (node (ref "R149") (pin "D2") (pinfunction "5_D2") (pintype "passive"))
    )
    (net (code "278") (name "unconnected-(USB1-SBU1-PadA8)") (class "Default")
      (node (ref "USB1") (pin "A8") (pinfunction "SBU1_A8") (pintype "bidirectional"))
    )
    (net (code "279") (name "unconnected-(USB1-SBU2-PadB8)") (class "Default")
      (node (ref "USB1") (pin "B8") (pinfunction "SBU2_B8") (pintype "bidirectional"))
    )
    (net (code "280") (name "~{ACT}") (class "Default")
      (node (ref "IC20") (pin "27") (pinfunction "ACTLED_27") (pintype "output"))
      (node (ref "R142") (pin "1") (pinfunction "1_1") (pintype "passive"))
    )
    (net (code "281") (name "~{LINK}") (class "Default")
      (node (ref "IC20") (pin "25") (pinfunction "LINKLED_25") (pintype "output"))
      (node (ref "R141") (pin "1") (pinfunction "1_1") (pintype "passive"))
    )
    (net (code "282") (name "~{QSPI_SS}") (class "Default")
      (node (ref "IC15") (pin "56") (pinfunction "QSPI_SS_N_56") (pintype "bidirectional"))
      (node (ref "IC18") (pin "1") (pinfunction "~{CS}_1") (pintype "bidirectional"))
      (node (ref "R111") (pin "1") (pinfunction "1_1") (pintype "passive"))
      (node (ref "R112") (pin "2") (pinfunction "2_2") (pintype "passive"))
    )
    (net (code "283") (name "~{TX_OUT}") (class "Default")
      (node (ref "IC22") (pin "3") (pinfunction "+IN_3") (pintype "input"))
      (node (ref "IC9") (pin "6") (pinfunction "~{Y}_6") (pintype "bidirectional"))
      (node (ref "R92") (pin "1") (pinfunction "1_1") (pintype "passive"))
    )
    (net (code "284") (name "~{W5500_CS}") (class "Default")
      (node (ref "IC15") (pin "28") (pinfunction "GPIO17_28") (pintype "bidirectional"))
      (node (ref "IC20") (pin "32") (pinfunction "~{SCSN}_32") (pintype "input"))
    )
    (net (code "285") (name "~{W5500_INT}") (class "Default")
      (node (ref "IC15") (pin "32") (pinfunction "GPIO21_32") (pintype "bidirectional"))
      (node (ref "IC20") (pin "36") (pinfunction "~{INTN}_36") (pintype "input"))
    )
    (net (code "286") (name "~{W5500_RST}") (class "Default")
      (node (ref "IC15") (pin "31") (pinfunction "GPIO20_31") (pintype "bidirectional"))
      (node (ref "IC20") (pin "37") (pinfunction "~{RSTN}_37") (pintype "input"))
      (node (ref "R145") (pin "1") (pinfunction "1_1") (pintype "passive"))
    )
  )
)
